# Main_DIY_board_-_STM32.net
KiCad netlist of a schematic drawn in EAGLE
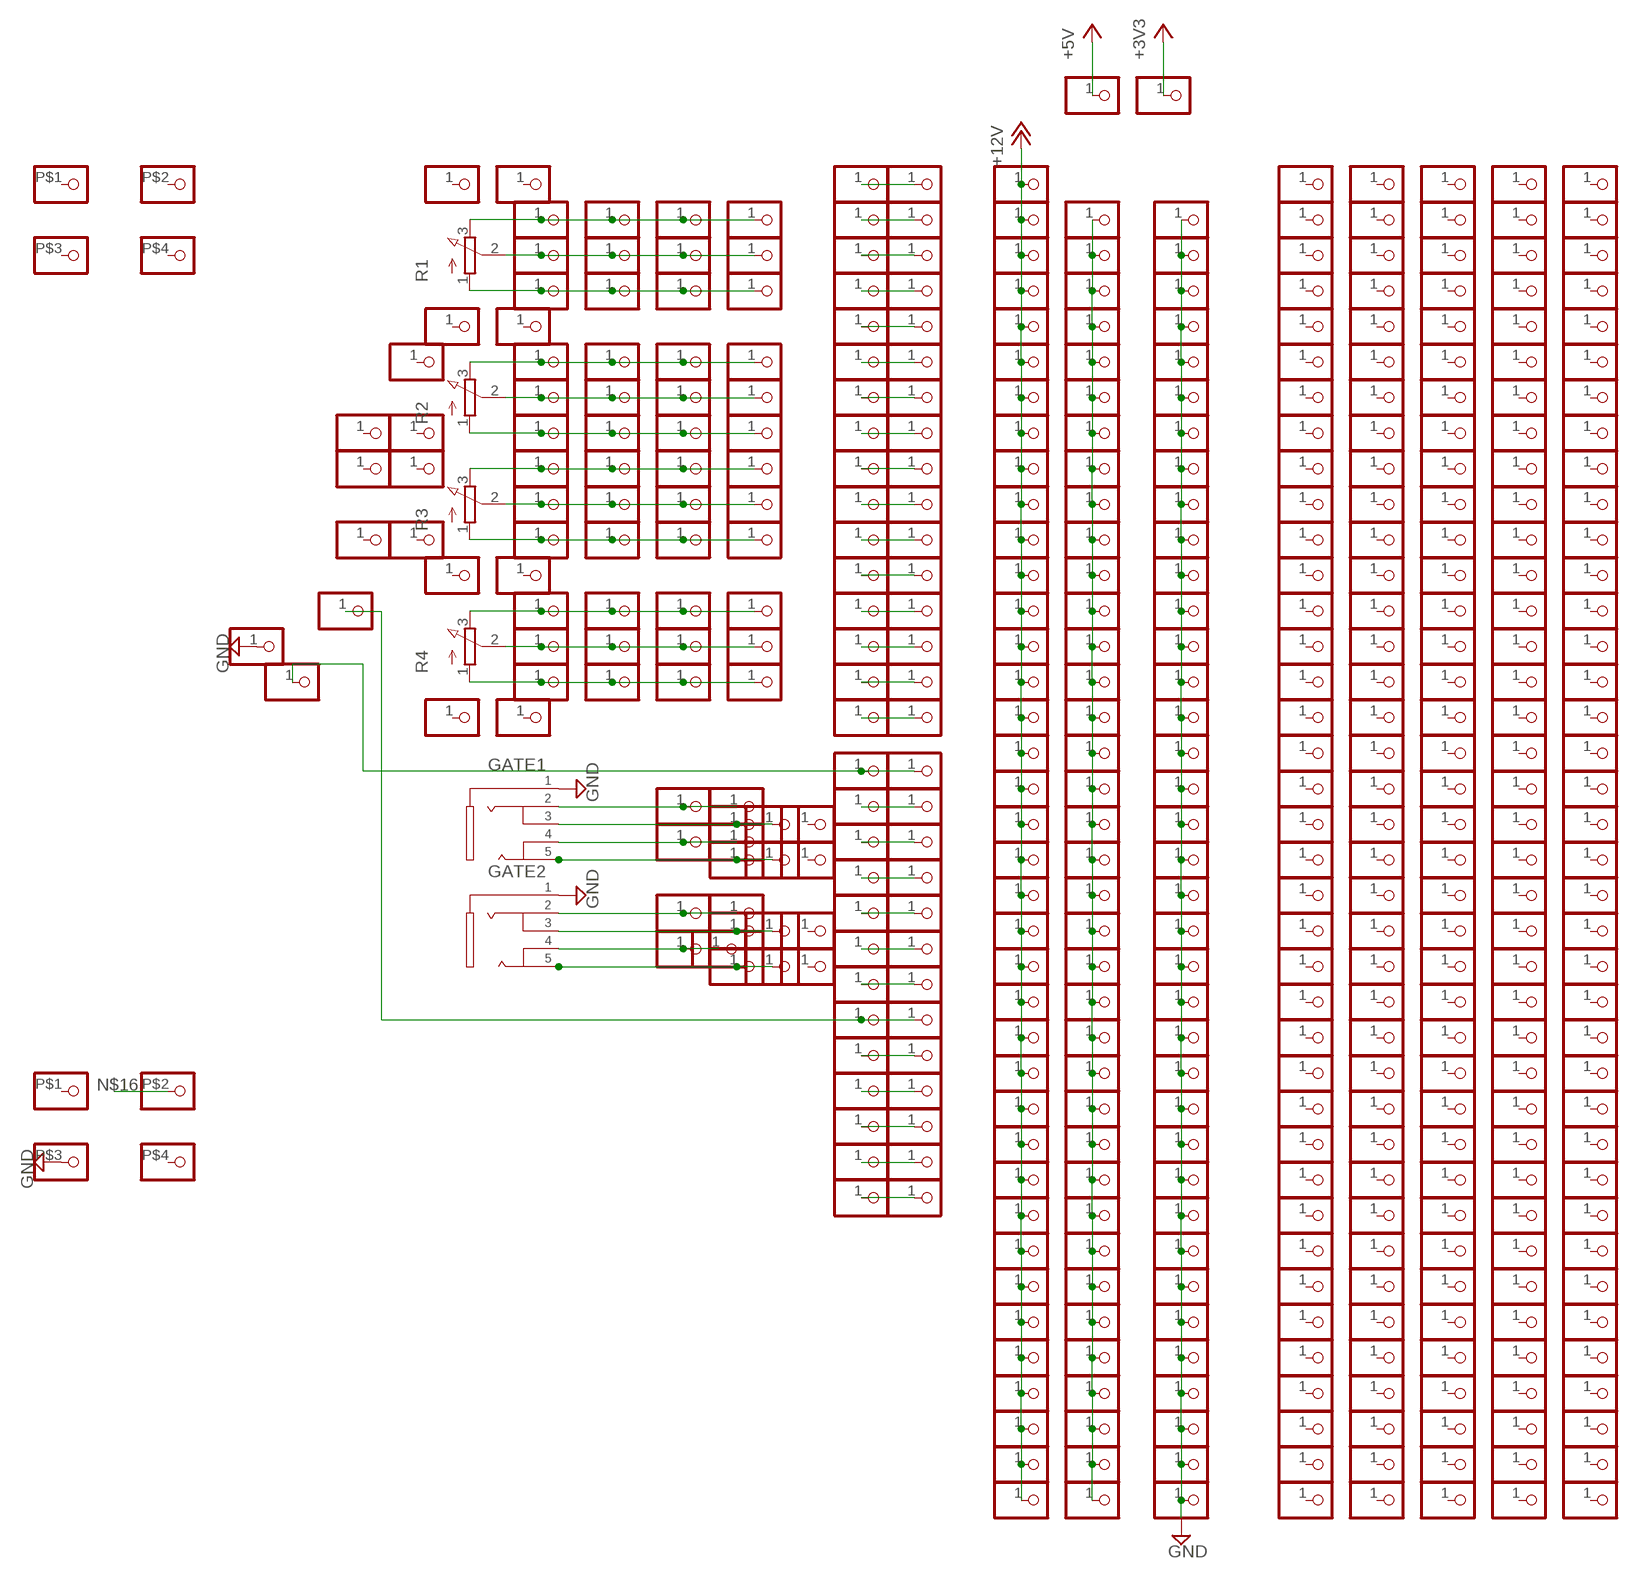
[diagram p0: schematic, sheet 1, part 1 of 2]
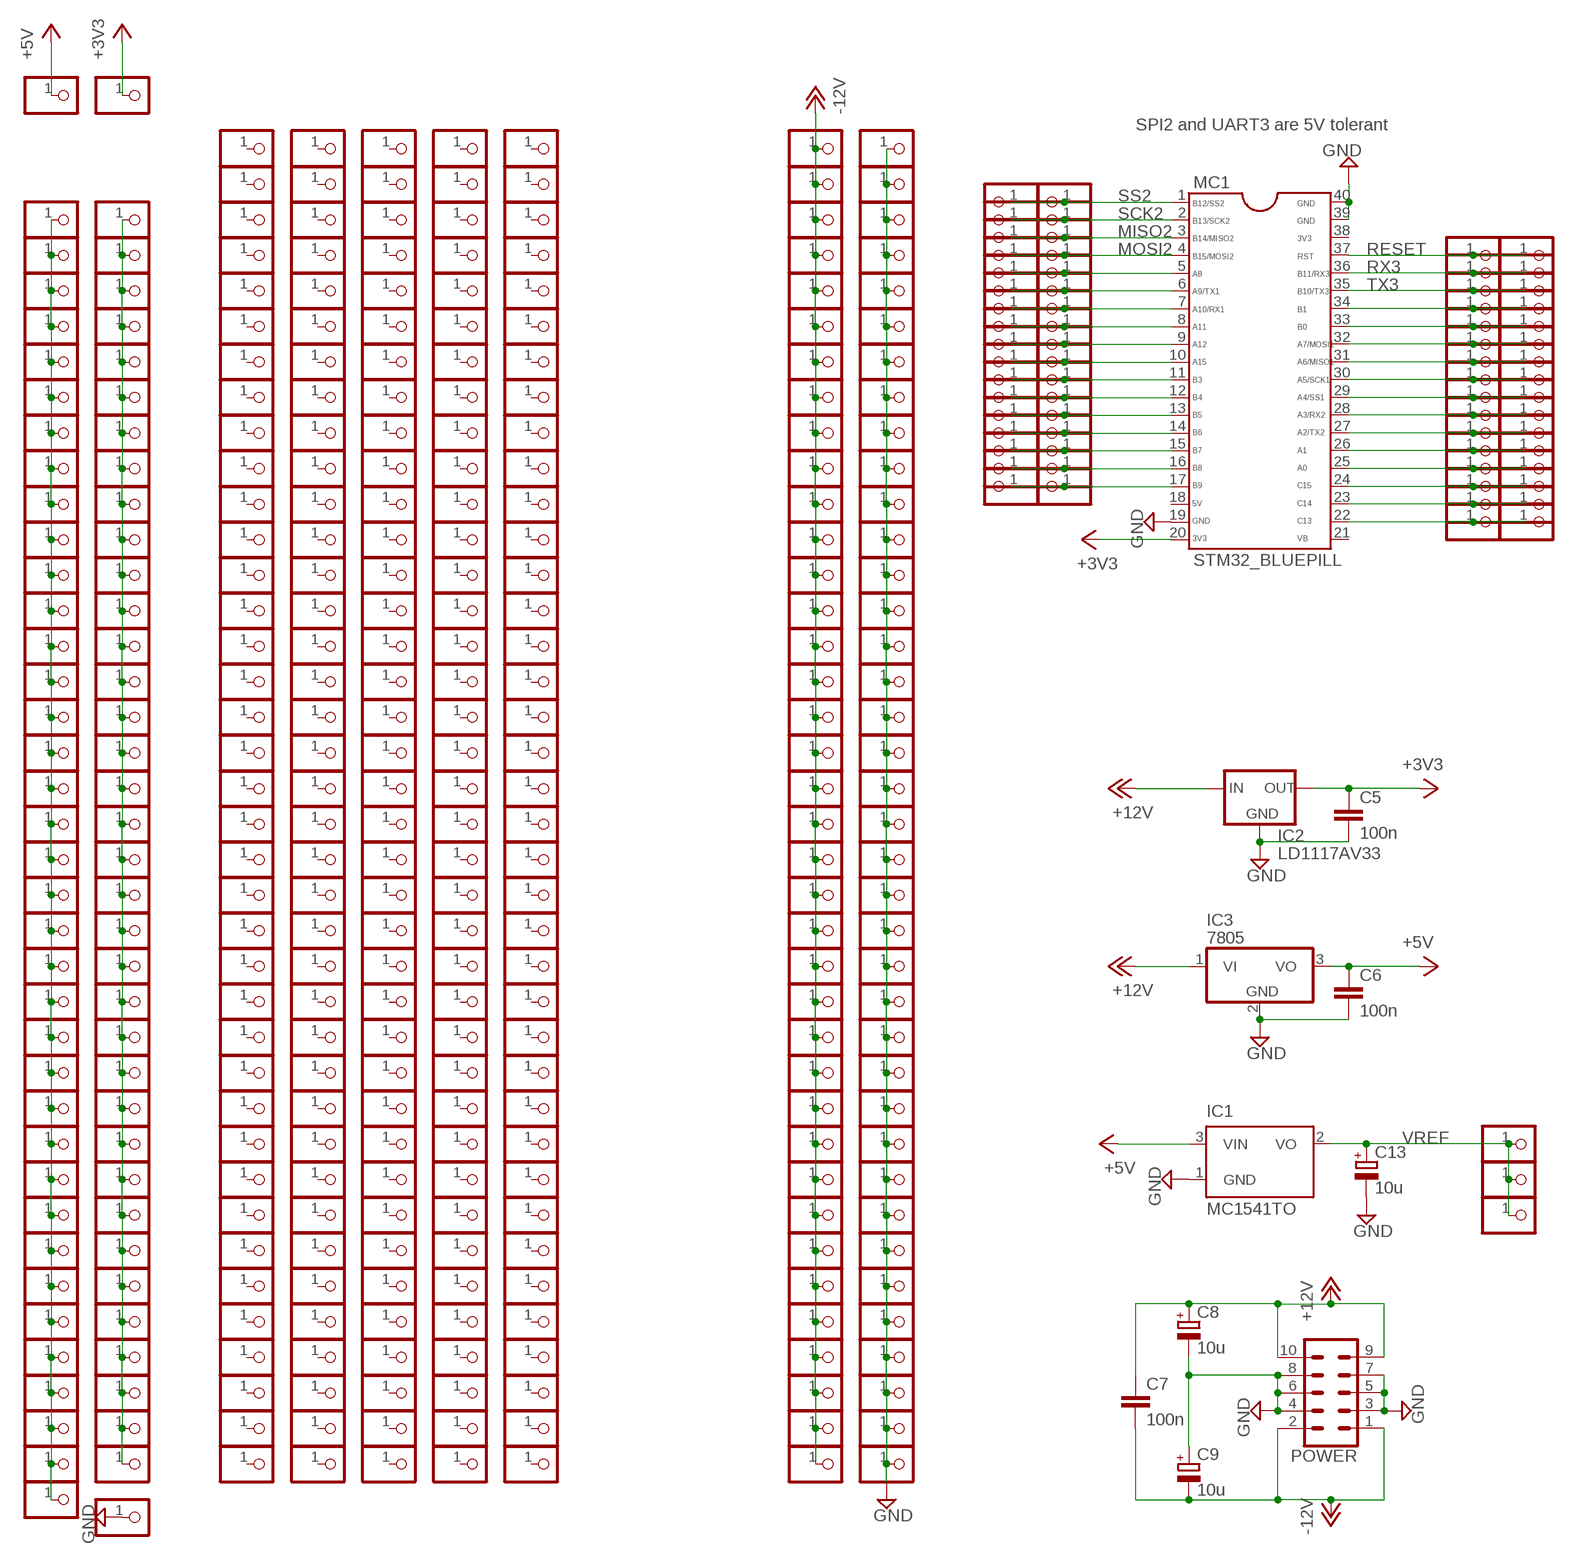
[diagram p1: schematic, sheet 1, part 2 of 2]

(export (version "E")
  (design (tool "Eeschema 10.0.6"))
  (components
    (comp (ref "C5")
      (value "100n")
      (footprint "eagle-import:C050-025X075")
      (libsource (lib "eagle-import") (part "C-EU050-025X075"))
    )
    (comp (ref "C6")
      (value "100n")
      (footprint "eagle-import:C050-025X075")
      (libsource (lib "eagle-import") (part "C-EU050-025X075"))
    )
    (comp (ref "C7")
      (value "100n")
      (footprint "eagle-import:C050-025X075")
      (libsource (lib "eagle-import") (part "C-EU050-025X075"))
    )
    (comp (ref "C8")
      (value "10u")
      (footprint "eagle-import:E2,5-5")
      (libsource (lib "eagle-import") (part "CPOL"))
    )
    (comp (ref "C9")
      (value "10u")
      (footprint "eagle-import:E2,5-5")
      (libsource (lib "eagle-import") (part "CPOL"))
    )
    (comp (ref "C13")
      (value "10u")
      (footprint "eagle-import:E2,5-5")
      (libsource (lib "eagle-import") (part "CPOL"))
    )
    (comp (ref "GATE1")
      (value "PJ-324MH")
      (footprint "eagle-import:PJ-324MH")
      (libsource (lib "eagle-import") (part "PJ-324MH"))
    )
    (comp (ref "GATE2")
      (value "PJ-324MH")
      (footprint "eagle-import:PJ-324MH")
      (libsource (lib "eagle-import") (part "PJ-324MH"))
    )
    (comp (ref "IC1")
      (value "MC1541TO")
      (footprint "eagle-import:TO92")
      (libsource (lib "eagle-import") (part "MC15TO41"))
    )
    (comp (ref "IC2")
      (value "LD1117AV33")
      (footprint "eagle-import:78XXL")
      (libsource (lib "eagle-import") (part "V_REG_LD1117VXX"))
    )
    (comp (ref "IC3")
      (value "7805")
      (footprint "eagle-import:TO220H")
      (libsource (lib "eagle-import") (part "78T05"))
    )
    (comp (ref "JP1")
      (value "1X01")
      (footprint "eagle-import:1X01")
      (libsource (lib "eagle-import") (part "1X01"))
    )
    (comp (ref "JP2")
      (value "1X01")
      (footprint "eagle-import:1X01")
      (libsource (lib "eagle-import") (part "1X01"))
    )
    (comp (ref "JP3")
      (value "1X01")
      (footprint "eagle-import:1X01")
      (libsource (lib "eagle-import") (part "1X01"))
    )
    (comp (ref "JP4")
      (value "1X01")
      (footprint "eagle-import:1X01")
      (libsource (lib "eagle-import") (part "1X01"))
    )
    (comp (ref "JP5")
      (value "1X01")
      (footprint "eagle-import:1X01")
      (libsource (lib "eagle-import") (part "1X01"))
    )
    (comp (ref "JP6")
      (value "1X01")
      (footprint "eagle-import:1X01")
      (libsource (lib "eagle-import") (part "1X01"))
    )
    (comp (ref "JP7")
      (value "1X01")
      (footprint "eagle-import:1X01")
      (libsource (lib "eagle-import") (part "1X01"))
    )
    (comp (ref "JP8")
      (value "1X01")
      (footprint "eagle-import:1X01")
      (libsource (lib "eagle-import") (part "1X01"))
    )
    (comp (ref "JP9")
      (value "1X01")
      (footprint "eagle-import:1X01")
      (libsource (lib "eagle-import") (part "1X01"))
    )
    (comp (ref "JP10")
      (value "1X01")
      (footprint "eagle-import:1X01")
      (libsource (lib "eagle-import") (part "1X01"))
    )
    (comp (ref "JP11")
      (value "1X01")
      (footprint "eagle-import:1X01")
      (libsource (lib "eagle-import") (part "1X01"))
    )
    (comp (ref "JP12")
      (value "1X01")
      (footprint "eagle-import:1X01")
      (libsource (lib "eagle-import") (part "1X01"))
    )
    (comp (ref "JP13")
      (value "1X01")
      (footprint "eagle-import:1X01")
      (libsource (lib "eagle-import") (part "1X01"))
    )
    (comp (ref "JP14")
      (value "1X01")
      (footprint "eagle-import:1X01")
      (libsource (lib "eagle-import") (part "1X01"))
    )
    (comp (ref "JP15")
      (value "1X01")
      (footprint "eagle-import:1X01")
      (libsource (lib "eagle-import") (part "1X01"))
    )
    (comp (ref "JP16")
      (value "1X01")
      (footprint "eagle-import:1X01")
      (libsource (lib "eagle-import") (part "1X01"))
    )
    (comp (ref "JP17")
      (value "1X01")
      (footprint "eagle-import:1X01")
      (libsource (lib "eagle-import") (part "1X01"))
    )
    (comp (ref "JP18")
      (value "1X01")
      (footprint "eagle-import:1X01")
      (libsource (lib "eagle-import") (part "1X01"))
    )
    (comp (ref "JP19")
      (value "1X01")
      (footprint "eagle-import:1X01")
      (libsource (lib "eagle-import") (part "1X01"))
    )
    (comp (ref "JP20")
      (value "1X01")
      (footprint "eagle-import:1X01")
      (libsource (lib "eagle-import") (part "1X01"))
    )
    (comp (ref "JP21")
      (value "1X01")
      (footprint "eagle-import:1X01")
      (libsource (lib "eagle-import") (part "1X01"))
    )
    (comp (ref "JP22")
      (value "1X01")
      (footprint "eagle-import:1X01")
      (libsource (lib "eagle-import") (part "1X01"))
    )
    (comp (ref "JP23")
      (value "1X01")
      (footprint "eagle-import:1X01")
      (libsource (lib "eagle-import") (part "1X01"))
    )
    (comp (ref "JP24")
      (value "1X01")
      (footprint "eagle-import:1X01")
      (libsource (lib "eagle-import") (part "1X01"))
    )
    (comp (ref "JP25")
      (value "1X01")
      (footprint "eagle-import:1X01")
      (libsource (lib "eagle-import") (part "1X01"))
    )
    (comp (ref "JP26")
      (value "1X01")
      (footprint "eagle-import:1X01")
      (libsource (lib "eagle-import") (part "1X01"))
    )
    (comp (ref "JP27")
      (value "1X01")
      (footprint "eagle-import:1X01")
      (libsource (lib "eagle-import") (part "1X01"))
    )
    (comp (ref "JP28")
      (value "1X01")
      (footprint "eagle-import:1X01")
      (libsource (lib "eagle-import") (part "1X01"))
    )
    (comp (ref "JP29")
      (value "1X01")
      (footprint "eagle-import:1X01")
      (libsource (lib "eagle-import") (part "1X01"))
    )
    (comp (ref "JP30")
      (value "1X01")
      (footprint "eagle-import:1X01")
      (libsource (lib "eagle-import") (part "1X01"))
    )
    (comp (ref "JP31")
      (value "1X01")
      (footprint "eagle-import:1X01")
      (libsource (lib "eagle-import") (part "1X01"))
    )
    (comp (ref "JP32")
      (value "1X01")
      (footprint "eagle-import:1X01")
      (libsource (lib "eagle-import") (part "1X01"))
    )
    (comp (ref "JP33")
      (value "1X01")
      (footprint "eagle-import:1X01")
      (libsource (lib "eagle-import") (part "1X01"))
    )
    (comp (ref "JP34")
      (value "1X01")
      (footprint "eagle-import:1X01")
      (libsource (lib "eagle-import") (part "1X01"))
    )
    (comp (ref "JP35")
      (value "1X01")
      (footprint "eagle-import:1X01")
      (libsource (lib "eagle-import") (part "1X01"))
    )
    (comp (ref "JP36")
      (value "1X01")
      (footprint "eagle-import:1X01")
      (libsource (lib "eagle-import") (part "1X01"))
    )
    (comp (ref "JP37")
      (value "1X01")
      (footprint "eagle-import:1X01")
      (libsource (lib "eagle-import") (part "1X01"))
    )
    (comp (ref "JP38")
      (value "1X01")
      (footprint "eagle-import:1X01")
      (libsource (lib "eagle-import") (part "1X01"))
    )
    (comp (ref "JP39")
      (value "1X01")
      (footprint "eagle-import:1X01")
      (libsource (lib "eagle-import") (part "1X01"))
    )
    (comp (ref "JP40")
      (value "1X01")
      (footprint "eagle-import:1X01")
      (libsource (lib "eagle-import") (part "1X01"))
    )
    (comp (ref "JP41")
      (value "1X01")
      (footprint "eagle-import:1X01")
      (libsource (lib "eagle-import") (part "1X01"))
    )
    (comp (ref "JP42")
      (value "1X01")
      (footprint "eagle-import:1X01")
      (libsource (lib "eagle-import") (part "1X01"))
    )
    (comp (ref "JP43")
      (value "1X01")
      (footprint "eagle-import:1X01")
      (libsource (lib "eagle-import") (part "1X01"))
    )
    (comp (ref "JP44")
      (value "1X01")
      (footprint "eagle-import:1X01")
      (libsource (lib "eagle-import") (part "1X01"))
    )
    (comp (ref "JP45")
      (value "1X01")
      (footprint "eagle-import:1X01")
      (libsource (lib "eagle-import") (part "1X01"))
    )
    (comp (ref "JP46")
      (value "1X01")
      (footprint "eagle-import:1X01")
      (libsource (lib "eagle-import") (part "1X01"))
    )
    (comp (ref "JP47")
      (value "1X01")
      (footprint "eagle-import:1X01")
      (libsource (lib "eagle-import") (part "1X01"))
    )
    (comp (ref "JP48")
      (value "1X01")
      (footprint "eagle-import:1X01")
      (libsource (lib "eagle-import") (part "1X01"))
    )
    (comp (ref "JP49")
      (value "1X01")
      (footprint "eagle-import:1X01")
      (libsource (lib "eagle-import") (part "1X01"))
    )
    (comp (ref "JP50")
      (value "1X01")
      (footprint "eagle-import:1X01")
      (libsource (lib "eagle-import") (part "1X01"))
    )
    (comp (ref "JP51")
      (value "1X01")
      (footprint "eagle-import:1X01")
      (libsource (lib "eagle-import") (part "1X01"))
    )
    (comp (ref "JP52")
      (value "1X01")
      (footprint "eagle-import:1X01")
      (libsource (lib "eagle-import") (part "1X01"))
    )
    (comp (ref "JP53")
      (value "1X01")
      (footprint "eagle-import:1X01")
      (libsource (lib "eagle-import") (part "1X01"))
    )
    (comp (ref "JP54")
      (value "1X01")
      (footprint "eagle-import:1X01")
      (libsource (lib "eagle-import") (part "1X01"))
    )
    (comp (ref "JP55")
      (value "1X01")
      (footprint "eagle-import:1X01")
      (libsource (lib "eagle-import") (part "1X01"))
    )
    (comp (ref "JP56")
      (value "1X01")
      (footprint "eagle-import:1X01")
      (libsource (lib "eagle-import") (part "1X01"))
    )
    (comp (ref "JP57")
      (value "1X01")
      (footprint "eagle-import:1X01")
      (libsource (lib "eagle-import") (part "1X01"))
    )
    (comp (ref "JP58")
      (value "1X01")
      (footprint "eagle-import:1X01")
      (libsource (lib "eagle-import") (part "1X01"))
    )
    (comp (ref "JP59")
      (value "1X01")
      (footprint "eagle-import:1X01")
      (libsource (lib "eagle-import") (part "1X01"))
    )
    (comp (ref "JP60")
      (value "1X01")
      (footprint "eagle-import:1X01")
      (libsource (lib "eagle-import") (part "1X01"))
    )
    (comp (ref "JP61")
      (value "1X01")
      (footprint "eagle-import:1X01")
      (libsource (lib "eagle-import") (part "1X01"))
    )
    (comp (ref "JP62")
      (value "1X01")
      (footprint "eagle-import:1X01")
      (libsource (lib "eagle-import") (part "1X01"))
    )
    (comp (ref "JP63")
      (value "1X01")
      (footprint "eagle-import:1X01")
      (libsource (lib "eagle-import") (part "1X01"))
    )
    (comp (ref "JP64")
      (value "1X01")
      (footprint "eagle-import:1X01")
      (libsource (lib "eagle-import") (part "1X01"))
    )
    (comp (ref "JP65")
      (value "1X01")
      (footprint "eagle-import:1X01")
      (libsource (lib "eagle-import") (part "1X01"))
    )
    (comp (ref "JP66")
      (value "1X01")
      (footprint "eagle-import:1X01")
      (libsource (lib "eagle-import") (part "1X01"))
    )
    (comp (ref "JP67")
      (value "1X01")
      (footprint "eagle-import:1X01")
      (libsource (lib "eagle-import") (part "1X01"))
    )
    (comp (ref "JP68")
      (value "1X01")
      (footprint "eagle-import:1X01")
      (libsource (lib "eagle-import") (part "1X01"))
    )
    (comp (ref "JP69")
      (value "1X01")
      (footprint "eagle-import:1X01")
      (libsource (lib "eagle-import") (part "1X01"))
    )
    (comp (ref "JP70")
      (value "1X01")
      (footprint "eagle-import:1X01")
      (libsource (lib "eagle-import") (part "1X01"))
    )
    (comp (ref "JP71")
      (value "1X01")
      (footprint "eagle-import:1X01")
      (libsource (lib "eagle-import") (part "1X01"))
    )
    (comp (ref "JP72")
      (value "1X01")
      (footprint "eagle-import:1X01")
      (libsource (lib "eagle-import") (part "1X01"))
    )
    (comp (ref "JP73")
      (value "1X01")
      (footprint "eagle-import:1X01")
      (libsource (lib "eagle-import") (part "1X01"))
    )
    (comp (ref "JP74")
      (value "1X01")
      (footprint "eagle-import:1X01")
      (libsource (lib "eagle-import") (part "1X01"))
    )
    (comp (ref "JP75")
      (value "1X01")
      (footprint "eagle-import:1X01")
      (libsource (lib "eagle-import") (part "1X01"))
    )
    (comp (ref "JP76")
      (value "1X01")
      (footprint "eagle-import:1X01")
      (libsource (lib "eagle-import") (part "1X01"))
    )
    (comp (ref "JP77")
      (value "1X01")
      (footprint "eagle-import:1X01")
      (libsource (lib "eagle-import") (part "1X01"))
    )
    (comp (ref "JP78")
      (value "1X01")
      (footprint "eagle-import:1X01")
      (libsource (lib "eagle-import") (part "1X01"))
    )
    (comp (ref "JP79")
      (value "1X01")
      (footprint "eagle-import:1X01")
      (libsource (lib "eagle-import") (part "1X01"))
    )
    (comp (ref "JP80")
      (value "1X01")
      (footprint "eagle-import:1X01")
      (libsource (lib "eagle-import") (part "1X01"))
    )
    (comp (ref "JP81")
      (value "1X01")
      (footprint "eagle-import:1X01")
      (libsource (lib "eagle-import") (part "1X01"))
    )
    (comp (ref "JP82")
      (value "1X01")
      (footprint "eagle-import:1X01")
      (libsource (lib "eagle-import") (part "1X01"))
    )
    (comp (ref "JP83")
      (value "1X01")
      (footprint "eagle-import:1X01")
      (libsource (lib "eagle-import") (part "1X01"))
    )
    (comp (ref "JP84")
      (value "1X01")
      (footprint "eagle-import:1X01")
      (libsource (lib "eagle-import") (part "1X01"))
    )
    (comp (ref "JP85")
      (value "1X01")
      (footprint "eagle-import:1X01")
      (libsource (lib "eagle-import") (part "1X01"))
    )
    (comp (ref "JP86")
      (value "1X01")
      (footprint "eagle-import:1X01")
      (libsource (lib "eagle-import") (part "1X01"))
    )
    (comp (ref "JP87")
      (value "1X01")
      (footprint "eagle-import:1X01")
      (libsource (lib "eagle-import") (part "1X01"))
    )
    (comp (ref "JP88")
      (value "1X01")
      (footprint "eagle-import:1X01")
      (libsource (lib "eagle-import") (part "1X01"))
    )
    (comp (ref "JP89")
      (value "1X01")
      (footprint "eagle-import:1X01")
      (libsource (lib "eagle-import") (part "1X01"))
    )
    (comp (ref "JP90")
      (value "1X01")
      (footprint "eagle-import:1X01")
      (libsource (lib "eagle-import") (part "1X01"))
    )
    (comp (ref "JP91")
      (value "1X01")
      (footprint "eagle-import:1X01")
      (libsource (lib "eagle-import") (part "1X01"))
    )
    (comp (ref "JP92")
      (value "1X01")
      (footprint "eagle-import:1X01")
      (libsource (lib "eagle-import") (part "1X01"))
    )
    (comp (ref "JP93")
      (value "1X01")
      (footprint "eagle-import:1X01")
      (libsource (lib "eagle-import") (part "1X01"))
    )
    (comp (ref "JP94")
      (value "1X01")
      (footprint "eagle-import:1X01")
      (libsource (lib "eagle-import") (part "1X01"))
    )
    (comp (ref "JP95")
      (value "1X01")
      (footprint "eagle-import:1X01")
      (libsource (lib "eagle-import") (part "1X01"))
    )
    (comp (ref "JP96")
      (value "1X01")
      (footprint "eagle-import:1X01")
      (libsource (lib "eagle-import") (part "1X01"))
    )
    (comp (ref "JP97")
      (value "1X01")
      (footprint "eagle-import:1X01")
      (libsource (lib "eagle-import") (part "1X01"))
    )
    (comp (ref "JP98")
      (value "1X01")
      (footprint "eagle-import:1X01")
      (libsource (lib "eagle-import") (part "1X01"))
    )
    (comp (ref "JP99")
      (value "1X01")
      (footprint "eagle-import:1X01")
      (libsource (lib "eagle-import") (part "1X01"))
    )
    (comp (ref "JP100")
      (value "1X01")
      (footprint "eagle-import:1X01")
      (libsource (lib "eagle-import") (part "1X01"))
    )
    (comp (ref "JP101")
      (value "1X01")
      (footprint "eagle-import:1X01")
      (libsource (lib "eagle-import") (part "1X01"))
    )
    (comp (ref "JP102")
      (value "1X01")
      (footprint "eagle-import:1X01")
      (libsource (lib "eagle-import") (part "1X01"))
    )
    (comp (ref "JP103")
      (value "1X01")
      (footprint "eagle-import:1X01")
      (libsource (lib "eagle-import") (part "1X01"))
    )
    (comp (ref "JP104")
      (value "1X01")
      (footprint "eagle-import:1X01")
      (libsource (lib "eagle-import") (part "1X01"))
    )
    (comp (ref "JP105")
      (value "1X01")
      (footprint "eagle-import:1X01")
      (libsource (lib "eagle-import") (part "1X01"))
    )
    (comp (ref "JP106")
      (value "1X01")
      (footprint "eagle-import:1X01")
      (libsource (lib "eagle-import") (part "1X01"))
    )
    (comp (ref "JP107")
      (value "1X01")
      (footprint "eagle-import:1X01")
      (libsource (lib "eagle-import") (part "1X01"))
    )
    (comp (ref "JP108")
      (value "1X01")
      (footprint "eagle-import:1X01")
      (libsource (lib "eagle-import") (part "1X01"))
    )
    (comp (ref "JP109")
      (value "1X01")
      (footprint "eagle-import:1X01")
      (libsource (lib "eagle-import") (part "1X01"))
    )
    (comp (ref "JP110")
      (value "1X01")
      (footprint "eagle-import:1X01")
      (libsource (lib "eagle-import") (part "1X01"))
    )
    (comp (ref "JP111")
      (value "1X01")
      (footprint "eagle-import:1X01")
      (libsource (lib "eagle-import") (part "1X01"))
    )
    (comp (ref "JP112")
      (value "1X01")
      (footprint "eagle-import:1X01")
      (libsource (lib "eagle-import") (part "1X01"))
    )
    (comp (ref "JP113")
      (value "1X01")
      (footprint "eagle-import:1X01")
      (libsource (lib "eagle-import") (part "1X01"))
    )
    (comp (ref "JP114")
      (value "1X01")
      (footprint "eagle-import:1X01")
      (libsource (lib "eagle-import") (part "1X01"))
    )
    (comp (ref "JP115")
      (value "1X01")
      (footprint "eagle-import:1X01")
      (libsource (lib "eagle-import") (part "1X01"))
    )
    (comp (ref "JP116")
      (value "1X01")
      (footprint "eagle-import:1X01")
      (libsource (lib "eagle-import") (part "1X01"))
    )
    (comp (ref "JP117")
      (value "1X01")
      (footprint "eagle-import:1X01")
      (libsource (lib "eagle-import") (part "1X01"))
    )
    (comp (ref "JP118")
      (value "1X01")
      (footprint "eagle-import:1X01")
      (libsource (lib "eagle-import") (part "1X01"))
    )
    (comp (ref "JP119")
      (value "1X01")
      (footprint "eagle-import:1X01")
      (libsource (lib "eagle-import") (part "1X01"))
    )
    (comp (ref "JP120")
      (value "1X01")
      (footprint "eagle-import:1X01")
      (libsource (lib "eagle-import") (part "1X01"))
    )
    (comp (ref "JP121")
      (value "1X01")
      (footprint "eagle-import:1X01")
      (libsource (lib "eagle-import") (part "1X01"))
    )
    (comp (ref "JP122")
      (value "1X01")
      (footprint "eagle-import:1X01")
      (libsource (lib "eagle-import") (part "1X01"))
    )
    (comp (ref "JP123")
      (value "1X01")
      (footprint "eagle-import:1X01")
      (libsource (lib "eagle-import") (part "1X01"))
    )
    (comp (ref "JP124")
      (value "1X01")
      (footprint "eagle-import:1X01")
      (libsource (lib "eagle-import") (part "1X01"))
    )
    (comp (ref "JP125")
      (value "1X01")
      (footprint "eagle-import:1X01")
      (libsource (lib "eagle-import") (part "1X01"))
    )
    (comp (ref "JP126")
      (value "1X01")
      (footprint "eagle-import:1X01")
      (libsource (lib "eagle-import") (part "1X01"))
    )
    (comp (ref "JP127")
      (value "1X01")
      (footprint "eagle-import:1X01")
      (libsource (lib "eagle-import") (part "1X01"))
    )
    (comp (ref "JP128")
      (value "1X01")
      (footprint "eagle-import:1X01")
      (libsource (lib "eagle-import") (part "1X01"))
    )
    (comp (ref "JP129")
      (value "1X01")
      (footprint "eagle-import:1X01")
      (libsource (lib "eagle-import") (part "1X01"))
    )
    (comp (ref "JP130")
      (value "1X01")
      (footprint "eagle-import:1X01")
      (libsource (lib "eagle-import") (part "1X01"))
    )
    (comp (ref "JP131")
      (value "1X01")
      (footprint "eagle-import:1X01")
      (libsource (lib "eagle-import") (part "1X01"))
    )
    (comp (ref "JP132")
      (value "1X01")
      (footprint "eagle-import:1X01")
      (libsource (lib "eagle-import") (part "1X01"))
    )
    (comp (ref "JP133")
      (value "1X01")
      (footprint "eagle-import:1X01")
      (libsource (lib "eagle-import") (part "1X01"))
    )
    (comp (ref "JP134")
      (value "1X01")
      (footprint "eagle-import:1X01")
      (libsource (lib "eagle-import") (part "1X01"))
    )
    (comp (ref "JP135")
      (value "1X01")
      (footprint "eagle-import:1X01")
      (libsource (lib "eagle-import") (part "1X01"))
    )
    (comp (ref "JP136")
      (value "1X01")
      (footprint "eagle-import:1X01")
      (libsource (lib "eagle-import") (part "1X01"))
    )
    (comp (ref "JP137")
      (value "1X01")
      (footprint "eagle-import:1X01")
      (libsource (lib "eagle-import") (part "1X01"))
    )
    (comp (ref "JP138")
      (value "1X01")
      (footprint "eagle-import:1X01")
      (libsource (lib "eagle-import") (part "1X01"))
    )
    (comp (ref "JP139")
      (value "1X01")
      (footprint "eagle-import:1X01")
      (libsource (lib "eagle-import") (part "1X01"))
    )
    (comp (ref "JP140")
      (value "1X01")
      (footprint "eagle-import:1X01")
      (libsource (lib "eagle-import") (part "1X01"))
    )
    (comp (ref "JP141")
      (value "1X01")
      (footprint "eagle-import:1X01")
      (libsource (lib "eagle-import") (part "1X01"))
    )
    (comp (ref "JP142")
      (value "1X01")
      (footprint "eagle-import:1X01")
      (libsource (lib "eagle-import") (part "1X01"))
    )
    (comp (ref "JP143")
      (value "1X01")
      (footprint "eagle-import:1X01")
      (libsource (lib "eagle-import") (part "1X01"))
    )
    (comp (ref "JP144")
      (value "1X01")
      (footprint "eagle-import:1X01")
      (libsource (lib "eagle-import") (part "1X01"))
    )
    (comp (ref "JP145")
      (value "1X01")
      (footprint "eagle-import:1X01")
      (libsource (lib "eagle-import") (part "1X01"))
    )
    (comp (ref "JP146")
      (value "1X01")
      (footprint "eagle-import:1X01")
      (libsource (lib "eagle-import") (part "1X01"))
    )
    (comp (ref "JP147")
      (value "1X01")
      (footprint "eagle-import:1X01")
      (libsource (lib "eagle-import") (part "1X01"))
    )
    (comp (ref "JP148")
      (value "1X01")
      (footprint "eagle-import:1X01")
      (libsource (lib "eagle-import") (part "1X01"))
    )
    (comp (ref "JP149")
      (value "1X01")
      (footprint "eagle-import:1X01")
      (libsource (lib "eagle-import") (part "1X01"))
    )
    (comp (ref "JP150")
      (value "1X01")
      (footprint "eagle-import:1X01")
      (libsource (lib "eagle-import") (part "1X01"))
    )
    (comp (ref "JP151")
      (value "1X01")
      (footprint "eagle-import:1X01")
      (libsource (lib "eagle-import") (part "1X01"))
    )
    (comp (ref "JP152")
      (value "1X01")
      (footprint "eagle-import:1X01")
      (libsource (lib "eagle-import") (part "1X01"))
    )
    (comp (ref "JP153")
      (value "1X01")
      (footprint "eagle-import:1X01")
      (libsource (lib "eagle-import") (part "1X01"))
    )
    (comp (ref "JP154")
      (value "1X01")
      (footprint "eagle-import:1X01")
      (libsource (lib "eagle-import") (part "1X01"))
    )
    (comp (ref "JP155")
      (value "1X01")
      (footprint "eagle-import:1X01")
      (libsource (lib "eagle-import") (part "1X01"))
    )
    (comp (ref "JP156")
      (value "1X01")
      (footprint "eagle-import:1X01")
      (libsource (lib "eagle-import") (part "1X01"))
    )
    (comp (ref "JP157")
      (value "1X01")
      (footprint "eagle-import:1X01")
      (libsource (lib "eagle-import") (part "1X01"))
    )
    (comp (ref "JP158")
      (value "1X01")
      (footprint "eagle-import:1X01")
      (libsource (lib "eagle-import") (part "1X01"))
    )
    (comp (ref "JP159")
      (value "1X01")
      (footprint "eagle-import:1X01")
      (libsource (lib "eagle-import") (part "1X01"))
    )
    (comp (ref "JP160")
      (value "1X01")
      (footprint "eagle-import:1X01")
      (libsource (lib "eagle-import") (part "1X01"))
    )
    (comp (ref "JP161")
      (value "1X01")
      (footprint "eagle-import:1X01")
      (libsource (lib "eagle-import") (part "1X01"))
    )
    (comp (ref "JP162")
      (value "1X01")
      (footprint "eagle-import:1X01")
      (libsource (lib "eagle-import") (part "1X01"))
    )
    (comp (ref "JP163")
      (value "1X01")
      (footprint "eagle-import:1X01")
      (libsource (lib "eagle-import") (part "1X01"))
    )
    (comp (ref "JP164")
      (value "1X01")
      (footprint "eagle-import:1X01")
      (libsource (lib "eagle-import") (part "1X01"))
    )
    (comp (ref "JP165")
      (value "1X01")
      (footprint "eagle-import:1X01")
      (libsource (lib "eagle-import") (part "1X01"))
    )
    (comp (ref "JP166")
      (value "1X01")
      (footprint "eagle-import:1X01")
      (libsource (lib "eagle-import") (part "1X01"))
    )
    (comp (ref "JP167")
      (value "1X01")
      (footprint "eagle-import:1X01")
      (libsource (lib "eagle-import") (part "1X01"))
    )
    (comp (ref "JP168")
      (value "1X01")
      (footprint "eagle-import:1X01")
      (libsource (lib "eagle-import") (part "1X01"))
    )
    (comp (ref "JP169")
      (value "1X01")
      (footprint "eagle-import:1X01")
      (libsource (lib "eagle-import") (part "1X01"))
    )
    (comp (ref "JP170")
      (value "1X01")
      (footprint "eagle-import:1X01")
      (libsource (lib "eagle-import") (part "1X01"))
    )
    (comp (ref "JP171")
      (value "1X01")
      (footprint "eagle-import:1X01")
      (libsource (lib "eagle-import") (part "1X01"))
    )
    (comp (ref "JP172")
      (value "1X01")
      (footprint "eagle-import:1X01")
      (libsource (lib "eagle-import") (part "1X01"))
    )
    (comp (ref "JP173")
      (value "1X01")
      (footprint "eagle-import:1X01")
      (libsource (lib "eagle-import") (part "1X01"))
    )
    (comp (ref "JP174")
      (value "1X01")
      (footprint "eagle-import:1X01")
      (libsource (lib "eagle-import") (part "1X01"))
    )
    (comp (ref "JP175")
      (value "1X01")
      (footprint "eagle-import:1X01")
      (libsource (lib "eagle-import") (part "1X01"))
    )
    (comp (ref "JP176")
      (value "1X01")
      (footprint "eagle-import:1X01")
      (libsource (lib "eagle-import") (part "1X01"))
    )
    (comp (ref "JP177")
      (value "1X01")
      (footprint "eagle-import:1X01")
      (libsource (lib "eagle-import") (part "1X01"))
    )
    (comp (ref "JP178")
      (value "1X01")
      (footprint "eagle-import:1X01")
      (libsource (lib "eagle-import") (part "1X01"))
    )
    (comp (ref "JP179")
      (value "1X01")
      (footprint "eagle-import:1X01")
      (libsource (lib "eagle-import") (part "1X01"))
    )
    (comp (ref "JP180")
      (value "1X01")
      (footprint "eagle-import:1X01")
      (libsource (lib "eagle-import") (part "1X01"))
    )
    (comp (ref "JP181")
      (value "1X01")
      (footprint "eagle-import:1X01")
      (libsource (lib "eagle-import") (part "1X01"))
    )
    (comp (ref "JP182")
      (value "1X01")
      (footprint "eagle-import:1X01")
      (libsource (lib "eagle-import") (part "1X01"))
    )
    (comp (ref "JP183")
      (value "1X01")
      (footprint "eagle-import:1X01")
      (libsource (lib "eagle-import") (part "1X01"))
    )
    (comp (ref "JP184")
      (value "1X01")
      (footprint "eagle-import:1X01")
      (libsource (lib "eagle-import") (part "1X01"))
    )
    (comp (ref "JP185")
      (value "1X01")
      (footprint "eagle-import:1X01")
      (libsource (lib "eagle-import") (part "1X01"))
    )
    (comp (ref "JP186")
      (value "1X01")
      (footprint "eagle-import:1X01")
      (libsource (lib "eagle-import") (part "1X01"))
    )
    (comp (ref "JP187")
      (value "1X01")
      (footprint "eagle-import:1X01")
      (libsource (lib "eagle-import") (part "1X01"))
    )
    (comp (ref "JP188")
      (value "1X01")
      (footprint "eagle-import:1X01")
      (libsource (lib "eagle-import") (part "1X01"))
    )
    (comp (ref "JP189")
      (value "1X01")
      (footprint "eagle-import:1X01")
      (libsource (lib "eagle-import") (part "1X01"))
    )
    (comp (ref "JP190")
      (value "1X01")
      (footprint "eagle-import:1X01")
      (libsource (lib "eagle-import") (part "1X01"))
    )
    (comp (ref "JP191")
      (value "1X01")
      (footprint "eagle-import:1X01")
      (libsource (lib "eagle-import") (part "1X01"))
    )
    (comp (ref "JP192")
      (value "1X01")
      (footprint "eagle-import:1X01")
      (libsource (lib "eagle-import") (part "1X01"))
    )
    (comp (ref "JP193")
      (value "1X01")
      (footprint "eagle-import:1X01")
      (libsource (lib "eagle-import") (part "1X01"))
    )
    (comp (ref "JP194")
      (value "1X01")
      (footprint "eagle-import:1X01")
      (libsource (lib "eagle-import") (part "1X01"))
    )
    (comp (ref "JP195")
      (value "1X01")
      (footprint "eagle-import:1X01")
      (libsource (lib "eagle-import") (part "1X01"))
    )
    (comp (ref "JP196")
      (value "1X01")
      (footprint "eagle-import:1X01")
      (libsource (lib "eagle-import") (part "1X01"))
    )
    (comp (ref "JP197")
      (value "1X01")
      (footprint "eagle-import:1X01")
      (libsource (lib "eagle-import") (part "1X01"))
    )
    (comp (ref "JP198")
      (value "1X01")
      (footprint "eagle-import:1X01")
      (libsource (lib "eagle-import") (part "1X01"))
    )
    (comp (ref "JP199")
      (value "1X01")
      (footprint "eagle-import:1X01")
      (libsource (lib "eagle-import") (part "1X01"))
    )
    (comp (ref "JP200")
      (value "1X01")
      (footprint "eagle-import:1X01")
      (libsource (lib "eagle-import") (part "1X01"))
    )
    (comp (ref "JP201")
      (value "1X01")
      (footprint "eagle-import:1X01")
      (libsource (lib "eagle-import") (part "1X01"))
    )
    (comp (ref "JP202")
      (value "1X01")
      (footprint "eagle-import:1X01")
      (libsource (lib "eagle-import") (part "1X01"))
    )
    (comp (ref "JP203")
      (value "1X01")
      (footprint "eagle-import:1X01")
      (libsource (lib "eagle-import") (part "1X01"))
    )
    (comp (ref "JP204")
      (value "1X01")
      (footprint "eagle-import:1X01")
      (libsource (lib "eagle-import") (part "1X01"))
    )
    (comp (ref "JP205")
      (value "1X01")
      (footprint "eagle-import:1X01")
      (libsource (lib "eagle-import") (part "1X01"))
    )
    (comp (ref "JP206")
      (value "1X01")
      (footprint "eagle-import:1X01")
      (libsource (lib "eagle-import") (part "1X01"))
    )
    (comp (ref "JP207")
      (value "1X01")
      (footprint "eagle-import:1X01")
      (libsource (lib "eagle-import") (part "1X01"))
    )
    (comp (ref "JP208")
      (value "1X01")
      (footprint "eagle-import:1X01")
      (libsource (lib "eagle-import") (part "1X01"))
    )
    (comp (ref "JP209")
      (value "1X01")
      (footprint "eagle-import:1X01")
      (libsource (lib "eagle-import") (part "1X01"))
    )
    (comp (ref "JP210")
      (value "1X01")
      (footprint "eagle-import:1X01")
      (libsource (lib "eagle-import") (part "1X01"))
    )
    (comp (ref "JP211")
      (value "1X01")
      (footprint "eagle-import:1X01")
      (libsource (lib "eagle-import") (part "1X01"))
    )
    (comp (ref "JP212")
      (value "1X01")
      (footprint "eagle-import:1X01")
      (libsource (lib "eagle-import") (part "1X01"))
    )
    (comp (ref "JP213")
      (value "1X01")
      (footprint "eagle-import:1X01")
      (libsource (lib "eagle-import") (part "1X01"))
    )
    (comp (ref "JP214")
      (value "1X01")
      (footprint "eagle-import:1X01")
      (libsource (lib "eagle-import") (part "1X01"))
    )
    (comp (ref "JP215")
      (value "1X01")
      (footprint "eagle-import:1X01")
      (libsource (lib "eagle-import") (part "1X01"))
    )
    (comp (ref "JP216")
      (value "1X01")
      (footprint "eagle-import:1X01")
      (libsource (lib "eagle-import") (part "1X01"))
    )
    (comp (ref "JP217")
      (value "1X01")
      (footprint "eagle-import:1X01")
      (libsource (lib "eagle-import") (part "1X01"))
    )
    (comp (ref "JP218")
      (value "1X01")
      (footprint "eagle-import:1X01")
      (libsource (lib "eagle-import") (part "1X01"))
    )
    (comp (ref "JP219")
      (value "1X01")
      (footprint "eagle-import:1X01")
      (libsource (lib "eagle-import") (part "1X01"))
    )
    (comp (ref "JP220")
      (value "1X01")
      (footprint "eagle-import:1X01")
      (libsource (lib "eagle-import") (part "1X01"))
    )
    (comp (ref "JP221")
      (value "1X01")
      (footprint "eagle-import:1X01")
      (libsource (lib "eagle-import") (part "1X01"))
    )
    (comp (ref "JP222")
      (value "1X01")
      (footprint "eagle-import:1X01")
      (libsource (lib "eagle-import") (part "1X01"))
    )
    (comp (ref "JP223")
      (value "1X01")
      (footprint "eagle-import:1X01")
      (libsource (lib "eagle-import") (part "1X01"))
    )
    (comp (ref "JP224")
      (value "1X01")
      (footprint "eagle-import:1X01")
      (libsource (lib "eagle-import") (part "1X01"))
    )
    (comp (ref "JP225")
      (value "1X01")
      (footprint "eagle-import:1X01")
      (libsource (lib "eagle-import") (part "1X01"))
    )
    (comp (ref "JP226")
      (value "1X01")
      (footprint "eagle-import:1X01")
      (libsource (lib "eagle-import") (part "1X01"))
    )
    (comp (ref "JP227")
      (value "1X01")
      (footprint "eagle-import:1X01")
      (libsource (lib "eagle-import") (part "1X01"))
    )
    (comp (ref "JP228")
      (value "1X01")
      (footprint "eagle-import:1X01")
      (libsource (lib "eagle-import") (part "1X01"))
    )
    (comp (ref "JP229")
      (value "1X01")
      (footprint "eagle-import:1X01")
      (libsource (lib "eagle-import") (part "1X01"))
    )
    (comp (ref "JP230")
      (value "1X01")
      (footprint "eagle-import:1X01")
      (libsource (lib "eagle-import") (part "1X01"))
    )
    (comp (ref "JP231")
      (value "1X01")
      (footprint "eagle-import:1X01")
      (libsource (lib "eagle-import") (part "1X01"))
    )
    (comp (ref "JP232")
      (value "1X01")
      (footprint "eagle-import:1X01")
      (libsource (lib "eagle-import") (part "1X01"))
    )
    (comp (ref "JP233")
      (value "1X01")
      (footprint "eagle-import:1X01")
      (libsource (lib "eagle-import") (part "1X01"))
    )
    (comp (ref "JP234")
      (value "1X01")
      (footprint "eagle-import:1X01")
      (libsource (lib "eagle-import") (part "1X01"))
    )
    (comp (ref "JP235")
      (value "1X01")
      (footprint "eagle-import:1X01")
      (libsource (lib "eagle-import") (part "1X01"))
    )
    (comp (ref "JP236")
      (value "1X01")
      (footprint "eagle-import:1X01")
      (libsource (lib "eagle-import") (part "1X01"))
    )
    (comp (ref "JP237")
      (value "1X01")
      (footprint "eagle-import:1X01")
      (libsource (lib "eagle-import") (part "1X01"))
    )
    (comp (ref "JP238")
      (value "1X01")
      (footprint "eagle-import:1X01")
      (libsource (lib "eagle-import") (part "1X01"))
    )
    (comp (ref "JP239")
      (value "1X01")
      (footprint "eagle-import:1X01")
      (libsource (lib "eagle-import") (part "1X01"))
    )
    (comp (ref "JP240")
      (value "1X01")
      (footprint "eagle-import:1X01")
      (libsource (lib "eagle-import") (part "1X01"))
    )
    (comp (ref "JP241")
      (value "1X01")
      (footprint "eagle-import:1X01")
      (libsource (lib "eagle-import") (part "1X01"))
    )
    (comp (ref "JP242")
      (value "1X01")
      (footprint "eagle-import:1X01")
      (libsource (lib "eagle-import") (part "1X01"))
    )
    (comp (ref "JP243")
      (value "1X01")
      (footprint "eagle-import:1X01")
      (libsource (lib "eagle-import") (part "1X01"))
    )
    (comp (ref "JP244")
      (value "1X01")
      (footprint "eagle-import:1X01")
      (libsource (lib "eagle-import") (part "1X01"))
    )
    (comp (ref "JP245")
      (value "1X01")
      (footprint "eagle-import:1X01")
      (libsource (lib "eagle-import") (part "1X01"))
    )
    (comp (ref "JP246")
      (value "1X01")
      (footprint "eagle-import:1X01")
      (libsource (lib "eagle-import") (part "1X01"))
    )
    (comp (ref "JP247")
      (value "1X01")
      (footprint "eagle-import:1X01")
      (libsource (lib "eagle-import") (part "1X01"))
    )
    (comp (ref "JP248")
      (value "1X01")
      (footprint "eagle-import:1X01")
      (libsource (lib "eagle-import") (part "1X01"))
    )
    (comp (ref "JP249")
      (value "1X01")
      (footprint "eagle-import:1X01")
      (libsource (lib "eagle-import") (part "1X01"))
    )
    (comp (ref "JP250")
      (value "1X01")
      (footprint "eagle-import:1X01")
      (libsource (lib "eagle-import") (part "1X01"))
    )
    (comp (ref "JP251")
      (value "1X01")
      (footprint "eagle-import:1X01")
      (libsource (lib "eagle-import") (part "1X01"))
    )
    (comp (ref "JP252")
      (value "1X01")
      (footprint "eagle-import:1X01")
      (libsource (lib "eagle-import") (part "1X01"))
    )
    (comp (ref "JP253")
      (value "1X01")
      (footprint "eagle-import:1X01")
      (libsource (lib "eagle-import") (part "1X01"))
    )
    (comp (ref "JP254")
      (value "1X01")
      (footprint "eagle-import:1X01")
      (libsource (lib "eagle-import") (part "1X01"))
    )
    (comp (ref "JP255")
      (value "1X01")
      (footprint "eagle-import:1X01")
      (libsource (lib "eagle-import") (part "1X01"))
    )
    (comp (ref "JP256")
      (value "1X01")
      (footprint "eagle-import:1X01")
      (libsource (lib "eagle-import") (part "1X01"))
    )
    (comp (ref "JP257")
      (value "1X01")
      (footprint "eagle-import:1X01")
      (libsource (lib "eagle-import") (part "1X01"))
    )
    (comp (ref "JP258")
      (value "1X01")
      (footprint "eagle-import:1X01")
      (libsource (lib "eagle-import") (part "1X01"))
    )
    (comp (ref "JP259")
      (value "1X01")
      (footprint "eagle-import:1X01")
      (libsource (lib "eagle-import") (part "1X01"))
    )
    (comp (ref "JP260")
      (value "1X01")
      (footprint "eagle-import:1X01")
      (libsource (lib "eagle-import") (part "1X01"))
    )
    (comp (ref "JP261")
      (value "1X01")
      (footprint "eagle-import:1X01")
      (libsource (lib "eagle-import") (part "1X01"))
    )
    (comp (ref "JP262")
      (value "1X01")
      (footprint "eagle-import:1X01")
      (libsource (lib "eagle-import") (part "1X01"))
    )
    (comp (ref "JP263")
      (value "1X01")
      (footprint "eagle-import:1X01")
      (libsource (lib "eagle-import") (part "1X01"))
    )
    (comp (ref "JP264")
      (value "1X01")
      (footprint "eagle-import:1X01")
      (libsource (lib "eagle-import") (part "1X01"))
    )
    (comp (ref "JP265")
      (value "1X01")
      (footprint "eagle-import:1X01")
      (libsource (lib "eagle-import") (part "1X01"))
    )
    (comp (ref "JP266")
      (value "1X01")
      (footprint "eagle-import:1X01")
      (libsource (lib "eagle-import") (part "1X01"))
    )
    (comp (ref "JP267")
      (value "1X01")
      (footprint "eagle-import:1X01")
      (libsource (lib "eagle-import") (part "1X01"))
    )
    (comp (ref "JP268")
      (value "1X01")
      (footprint "eagle-import:1X01")
      (libsource (lib "eagle-import") (part "1X01"))
    )
    (comp (ref "JP269")
      (value "1X01")
      (footprint "eagle-import:1X01")
      (libsource (lib "eagle-import") (part "1X01"))
    )
    (comp (ref "JP270")
      (value "1X01")
      (footprint "eagle-import:1X01")
      (libsource (lib "eagle-import") (part "1X01"))
    )
    (comp (ref "JP271")
      (value "1X01")
      (footprint "eagle-import:1X01")
      (libsource (lib "eagle-import") (part "1X01"))
    )
    (comp (ref "JP272")
      (value "1X01")
      (footprint "eagle-import:1X01")
      (libsource (lib "eagle-import") (part "1X01"))
    )
    (comp (ref "JP273")
      (value "1X01")
      (footprint "eagle-import:1X01")
      (libsource (lib "eagle-import") (part "1X01"))
    )
    (comp (ref "JP274")
      (value "1X01")
      (footprint "eagle-import:1X01")
      (libsource (lib "eagle-import") (part "1X01"))
    )
    (comp (ref "JP275")
      (value "1X01")
      (footprint "eagle-import:1X01")
      (libsource (lib "eagle-import") (part "1X01"))
    )
    (comp (ref "JP276")
      (value "1X01")
      (footprint "eagle-import:1X01")
      (libsource (lib "eagle-import") (part "1X01"))
    )
    (comp (ref "JP277")
      (value "1X01")
      (footprint "eagle-import:1X01")
      (libsource (lib "eagle-import") (part "1X01"))
    )
    (comp (ref "JP278")
      (value "1X01")
      (footprint "eagle-import:1X01")
      (libsource (lib "eagle-import") (part "1X01"))
    )
    (comp (ref "JP279")
      (value "1X01")
      (footprint "eagle-import:1X01")
      (libsource (lib "eagle-import") (part "1X01"))
    )
    (comp (ref "JP280")
      (value "1X01")
      (footprint "eagle-import:1X01")
      (libsource (lib "eagle-import") (part "1X01"))
    )
    (comp (ref "JP281")
      (value "1X01")
      (footprint "eagle-import:1X01")
      (libsource (lib "eagle-import") (part "1X01"))
    )
    (comp (ref "JP282")
      (value "1X01")
      (footprint "eagle-import:1X01")
      (libsource (lib "eagle-import") (part "1X01"))
    )
    (comp (ref "JP283")
      (value "1X01")
      (footprint "eagle-import:1X01")
      (libsource (lib "eagle-import") (part "1X01"))
    )
    (comp (ref "JP284")
      (value "1X01")
      (footprint "eagle-import:1X01")
      (libsource (lib "eagle-import") (part "1X01"))
    )
    (comp (ref "JP285")
      (value "1X01")
      (footprint "eagle-import:1X01")
      (libsource (lib "eagle-import") (part "1X01"))
    )
    (comp (ref "JP286")
      (value "1X01")
      (footprint "eagle-import:1X01")
      (libsource (lib "eagle-import") (part "1X01"))
    )
    (comp (ref "JP287")
      (value "1X01")
      (footprint "eagle-import:1X01")
      (libsource (lib "eagle-import") (part "1X01"))
    )
    (comp (ref "JP288")
      (value "1X01")
      (footprint "eagle-import:1X01")
      (libsource (lib "eagle-import") (part "1X01"))
    )
    (comp (ref "JP289")
      (value "1X01")
      (footprint "eagle-import:1X01")
      (libsource (lib "eagle-import") (part "1X01"))
    )
    (comp (ref "JP290")
      (value "1X01")
      (footprint "eagle-import:1X01")
      (libsource (lib "eagle-import") (part "1X01"))
    )
    (comp (ref "JP291")
      (value "1X01")
      (footprint "eagle-import:1X01")
      (libsource (lib "eagle-import") (part "1X01"))
    )
    (comp (ref "JP292")
      (value "1X01")
      (footprint "eagle-import:1X01")
      (libsource (lib "eagle-import") (part "1X01"))
    )
    (comp (ref "JP293")
      (value "1X01")
      (footprint "eagle-import:1X01")
      (libsource (lib "eagle-import") (part "1X01"))
    )
    (comp (ref "JP294")
      (value "1X01")
      (footprint "eagle-import:1X01")
      (libsource (lib "eagle-import") (part "1X01"))
    )
    (comp (ref "JP295")
      (value "1X01")
      (footprint "eagle-import:1X01")
      (libsource (lib "eagle-import") (part "1X01"))
    )
    (comp (ref "JP296")
      (value "1X01")
      (footprint "eagle-import:1X01")
      (libsource (lib "eagle-import") (part "1X01"))
    )
    (comp (ref "JP297")
      (value "1X01")
      (footprint "eagle-import:1X01")
      (libsource (lib "eagle-import") (part "1X01"))
    )
    (comp (ref "JP298")
      (value "1X01")
      (footprint "eagle-import:1X01")
      (libsource (lib "eagle-import") (part "1X01"))
    )
    (comp (ref "JP299")
      (value "1X01")
      (footprint "eagle-import:1X01")
      (libsource (lib "eagle-import") (part "1X01"))
    )
    (comp (ref "JP300")
      (value "1X01")
      (footprint "eagle-import:1X01")
      (libsource (lib "eagle-import") (part "1X01"))
    )
    (comp (ref "JP301")
      (value "1X01")
      (footprint "eagle-import:1X01")
      (libsource (lib "eagle-import") (part "1X01"))
    )
    (comp (ref "JP302")
      (value "1X01")
      (footprint "eagle-import:1X01")
      (libsource (lib "eagle-import") (part "1X01"))
    )
    (comp (ref "JP303")
      (value "1X01")
      (footprint "eagle-import:1X01")
      (libsource (lib "eagle-import") (part "1X01"))
    )
    (comp (ref "JP304")
      (value "1X01")
      (footprint "eagle-import:1X01")
      (libsource (lib "eagle-import") (part "1X01"))
    )
    (comp (ref "JP305")
      (value "1X01")
      (footprint "eagle-import:1X01")
      (libsource (lib "eagle-import") (part "1X01"))
    )
    (comp (ref "JP306")
      (value "1X01")
      (footprint "eagle-import:1X01")
      (libsource (lib "eagle-import") (part "1X01"))
    )
    (comp (ref "JP307")
      (value "1X01")
      (footprint "eagle-import:1X01")
      (libsource (lib "eagle-import") (part "1X01"))
    )
    (comp (ref "JP308")
      (value "1X01")
      (footprint "eagle-import:1X01")
      (libsource (lib "eagle-import") (part "1X01"))
    )
    (comp (ref "JP309")
      (value "1X01")
      (footprint "eagle-import:1X01")
      (libsource (lib "eagle-import") (part "1X01"))
    )
    (comp (ref "JP310")
      (value "1X01")
      (footprint "eagle-import:1X01")
      (libsource (lib "eagle-import") (part "1X01"))
    )
    (comp (ref "JP311")
      (value "1X01")
      (footprint "eagle-import:1X01")
      (libsource (lib "eagle-import") (part "1X01"))
    )
    (comp (ref "JP312")
      (value "1X01")
      (footprint "eagle-import:1X01")
      (libsource (lib "eagle-import") (part "1X01"))
    )
    (comp (ref "JP313")
      (value "1X01")
      (footprint "eagle-import:1X01")
      (libsource (lib "eagle-import") (part "1X01"))
    )
    (comp (ref "JP314")
      (value "1X01")
      (footprint "eagle-import:1X01")
      (libsource (lib "eagle-import") (part "1X01"))
    )
    (comp (ref "JP315")
      (value "1X01")
      (footprint "eagle-import:1X01")
      (libsource (lib "eagle-import") (part "1X01"))
    )
    (comp (ref "JP316")
      (value "1X01")
      (footprint "eagle-import:1X01")
      (libsource (lib "eagle-import") (part "1X01"))
    )
    (comp (ref "JP317")
      (value "1X01")
      (footprint "eagle-import:1X01")
      (libsource (lib "eagle-import") (part "1X01"))
    )
    (comp (ref "JP318")
      (value "1X01")
      (footprint "eagle-import:1X01")
      (libsource (lib "eagle-import") (part "1X01"))
    )
    (comp (ref "JP319")
      (value "1X01")
      (footprint "eagle-import:1X01")
      (libsource (lib "eagle-import") (part "1X01"))
    )
    (comp (ref "JP320")
      (value "1X01")
      (footprint "eagle-import:1X01")
      (libsource (lib "eagle-import") (part "1X01"))
    )
    (comp (ref "JP321")
      (value "1X01")
      (footprint "eagle-import:1X01")
      (libsource (lib "eagle-import") (part "1X01"))
    )
    (comp (ref "JP322")
      (value "1X01")
      (footprint "eagle-import:1X01")
      (libsource (lib "eagle-import") (part "1X01"))
    )
    (comp (ref "JP323")
      (value "1X01")
      (footprint "eagle-import:1X01")
      (libsource (lib "eagle-import") (part "1X01"))
    )
    (comp (ref "JP324")
      (value "1X01")
      (footprint "eagle-import:1X01")
      (libsource (lib "eagle-import") (part "1X01"))
    )
    (comp (ref "JP325")
      (value "1X01")
      (footprint "eagle-import:1X01")
      (libsource (lib "eagle-import") (part "1X01"))
    )
    (comp (ref "JP326")
      (value "1X01")
      (footprint "eagle-import:1X01")
      (libsource (lib "eagle-import") (part "1X01"))
    )
    (comp (ref "JP327")
      (value "1X01")
      (footprint "eagle-import:1X01")
      (libsource (lib "eagle-import") (part "1X01"))
    )
    (comp (ref "JP328")
      (value "1X01")
      (footprint "eagle-import:1X01")
      (libsource (lib "eagle-import") (part "1X01"))
    )
    (comp (ref "JP329")
      (value "1X01")
      (footprint "eagle-import:1X01")
      (libsource (lib "eagle-import") (part "1X01"))
    )
    (comp (ref "JP330")
      (value "1X01")
      (footprint "eagle-import:1X01")
      (libsource (lib "eagle-import") (part "1X01"))
    )
    (comp (ref "JP331")
      (value "1X01")
      (footprint "eagle-import:1X01")
      (libsource (lib "eagle-import") (part "1X01"))
    )
    (comp (ref "JP332")
      (value "1X01")
      (footprint "eagle-import:1X01")
      (libsource (lib "eagle-import") (part "1X01"))
    )
    (comp (ref "JP333")
      (value "1X01")
      (footprint "eagle-import:1X01")
      (libsource (lib "eagle-import") (part "1X01"))
    )
    (comp (ref "JP334")
      (value "1X01")
      (footprint "eagle-import:1X01")
      (libsource (lib "eagle-import") (part "1X01"))
    )
    (comp (ref "JP335")
      (value "1X01")
      (footprint "eagle-import:1X01")
      (libsource (lib "eagle-import") (part "1X01"))
    )
    (comp (ref "JP336")
      (value "1X01")
      (footprint "eagle-import:1X01")
      (libsource (lib "eagle-import") (part "1X01"))
    )
    (comp (ref "JP337")
      (value "1X01")
      (footprint "eagle-import:1X01")
      (libsource (lib "eagle-import") (part "1X01"))
    )
    (comp (ref "JP338")
      (value "1X01")
      (footprint "eagle-import:1X01")
      (libsource (lib "eagle-import") (part "1X01"))
    )
    (comp (ref "JP339")
      (value "1X01")
      (footprint "eagle-import:1X01")
      (libsource (lib "eagle-import") (part "1X01"))
    )
    (comp (ref "JP340")
      (value "1X01")
      (footprint "eagle-import:1X01")
      (libsource (lib "eagle-import") (part "1X01"))
    )
    (comp (ref "JP341")
      (value "1X01")
      (footprint "eagle-import:1X01")
      (libsource (lib "eagle-import") (part "1X01"))
    )
    (comp (ref "JP342")
      (value "1X01")
      (footprint "eagle-import:1X01")
      (libsource (lib "eagle-import") (part "1X01"))
    )
    (comp (ref "JP343")
      (value "1X01")
      (footprint "eagle-import:1X01")
      (libsource (lib "eagle-import") (part "1X01"))
    )
    (comp (ref "JP344")
      (value "1X01")
      (footprint "eagle-import:1X01")
      (libsource (lib "eagle-import") (part "1X01"))
    )
    (comp (ref "JP345")
      (value "1X01")
      (footprint "eagle-import:1X01")
      (libsource (lib "eagle-import") (part "1X01"))
    )
    (comp (ref "JP346")
      (value "1X01")
      (footprint "eagle-import:1X01")
      (libsource (lib "eagle-import") (part "1X01"))
    )
    (comp (ref "JP347")
      (value "1X01")
      (footprint "eagle-import:1X01")
      (libsource (lib "eagle-import") (part "1X01"))
    )
    (comp (ref "JP348")
      (value "1X01")
      (footprint "eagle-import:1X01")
      (libsource (lib "eagle-import") (part "1X01"))
    )
    (comp (ref "JP349")
      (value "1X01")
      (footprint "eagle-import:1X01")
      (libsource (lib "eagle-import") (part "1X01"))
    )
    (comp (ref "JP350")
      (value "1X01")
      (footprint "eagle-import:1X01")
      (libsource (lib "eagle-import") (part "1X01"))
    )
    (comp (ref "JP351")
      (value "1X01")
      (footprint "eagle-import:1X01")
      (libsource (lib "eagle-import") (part "1X01"))
    )
    (comp (ref "JP352")
      (value "1X01")
      (footprint "eagle-import:1X01")
      (libsource (lib "eagle-import") (part "1X01"))
    )
    (comp (ref "JP353")
      (value "1X01")
      (footprint "eagle-import:1X01")
      (libsource (lib "eagle-import") (part "1X01"))
    )
    (comp (ref "JP354")
      (value "1X01")
      (footprint "eagle-import:1X01")
      (libsource (lib "eagle-import") (part "1X01"))
    )
    (comp (ref "JP355")
      (value "1X01")
      (footprint "eagle-import:1X01")
      (libsource (lib "eagle-import") (part "1X01"))
    )
    (comp (ref "JP356")
      (value "1X01")
      (footprint "eagle-import:1X01")
      (libsource (lib "eagle-import") (part "1X01"))
    )
    (comp (ref "JP357")
      (value "1X01")
      (footprint "eagle-import:1X01")
      (libsource (lib "eagle-import") (part "1X01"))
    )
    (comp (ref "JP358")
      (value "1X01")
      (footprint "eagle-import:1X01")
      (libsource (lib "eagle-import") (part "1X01"))
    )
    (comp (ref "JP359")
      (value "1X01")
      (footprint "eagle-import:1X01")
      (libsource (lib "eagle-import") (part "1X01"))
    )
    (comp (ref "JP360")
      (value "1X01")
      (footprint "eagle-import:1X01")
      (libsource (lib "eagle-import") (part "1X01"))
    )
    (comp (ref "JP361")
      (value "1X01")
      (footprint "eagle-import:1X01")
      (libsource (lib "eagle-import") (part "1X01"))
    )
    (comp (ref "JP362")
      (value "1X01")
      (footprint "eagle-import:1X01")
      (libsource (lib "eagle-import") (part "1X01"))
    )
    (comp (ref "JP363")
      (value "1X01")
      (footprint "eagle-import:1X01")
      (libsource (lib "eagle-import") (part "1X01"))
    )
    (comp (ref "JP364")
      (value "1X01")
      (footprint "eagle-import:1X01")
      (libsource (lib "eagle-import") (part "1X01"))
    )
    (comp (ref "JP365")
      (value "1X01")
      (footprint "eagle-import:1X01")
      (libsource (lib "eagle-import") (part "1X01"))
    )
    (comp (ref "JP366")
      (value "1X01")
      (footprint "eagle-import:1X01")
      (libsource (lib "eagle-import") (part "1X01"))
    )
    (comp (ref "JP367")
      (value "1X01")
      (footprint "eagle-import:1X01")
      (libsource (lib "eagle-import") (part "1X01"))
    )
    (comp (ref "JP368")
      (value "1X01")
      (footprint "eagle-import:1X01")
      (libsource (lib "eagle-import") (part "1X01"))
    )
    (comp (ref "JP369")
      (value "1X01")
      (footprint "eagle-import:1X01")
      (libsource (lib "eagle-import") (part "1X01"))
    )
    (comp (ref "JP370")
      (value "1X01")
      (footprint "eagle-import:1X01")
      (libsource (lib "eagle-import") (part "1X01"))
    )
    (comp (ref "JP371")
      (value "1X01")
      (footprint "eagle-import:1X01")
      (libsource (lib "eagle-import") (part "1X01"))
    )
    (comp (ref "JP372")
      (value "1X01")
      (footprint "eagle-import:1X01")
      (libsource (lib "eagle-import") (part "1X01"))
    )
    (comp (ref "JP373")
      (value "1X01")
      (footprint "eagle-import:1X01")
      (libsource (lib "eagle-import") (part "1X01"))
    )
    (comp (ref "JP374")
      (value "1X01")
      (footprint "eagle-import:1X01")
      (libsource (lib "eagle-import") (part "1X01"))
    )
    (comp (ref "JP375")
      (value "1X01")
      (footprint "eagle-import:1X01")
      (libsource (lib "eagle-import") (part "1X01"))
    )
    (comp (ref "JP376")
      (value "1X01")
      (footprint "eagle-import:1X01")
      (libsource (lib "eagle-import") (part "1X01"))
    )
    (comp (ref "JP377")
      (value "1X01")
      (footprint "eagle-import:1X01")
      (libsource (lib "eagle-import") (part "1X01"))
    )
    (comp (ref "JP378")
      (value "1X01")
      (footprint "eagle-import:1X01")
      (libsource (lib "eagle-import") (part "1X01"))
    )
    (comp (ref "JP379")
      (value "1X01")
      (footprint "eagle-import:1X01")
      (libsource (lib "eagle-import") (part "1X01"))
    )
    (comp (ref "JP380")
      (value "1X01")
      (footprint "eagle-import:1X01")
      (libsource (lib "eagle-import") (part "1X01"))
    )
    (comp (ref "JP381")
      (value "1X01")
      (footprint "eagle-import:1X01")
      (libsource (lib "eagle-import") (part "1X01"))
    )
    (comp (ref "JP382")
      (value "1X01")
      (footprint "eagle-import:1X01")
      (libsource (lib "eagle-import") (part "1X01"))
    )
    (comp (ref "JP383")
      (value "1X01")
      (footprint "eagle-import:1X01")
      (libsource (lib "eagle-import") (part "1X01"))
    )
    (comp (ref "JP384")
      (value "1X01")
      (footprint "eagle-import:1X01")
      (libsource (lib "eagle-import") (part "1X01"))
    )
    (comp (ref "JP385")
      (value "1X01")
      (footprint "eagle-import:1X01")
      (libsource (lib "eagle-import") (part "1X01"))
    )
    (comp (ref "JP386")
      (value "1X01")
      (footprint "eagle-import:1X01")
      (libsource (lib "eagle-import") (part "1X01"))
    )
    (comp (ref "JP387")
      (value "1X01")
      (footprint "eagle-import:1X01")
      (libsource (lib "eagle-import") (part "1X01"))
    )
    (comp (ref "JP388")
      (value "1X01")
      (footprint "eagle-import:1X01")
      (libsource (lib "eagle-import") (part "1X01"))
    )
    (comp (ref "JP389")
      (value "1X01")
      (footprint "eagle-import:1X01")
      (libsource (lib "eagle-import") (part "1X01"))
    )
    (comp (ref "JP390")
      (value "1X01")
      (footprint "eagle-import:1X01")
      (libsource (lib "eagle-import") (part "1X01"))
    )
    (comp (ref "JP391")
      (value "1X01")
      (footprint "eagle-import:1X01")
      (libsource (lib "eagle-import") (part "1X01"))
    )
    (comp (ref "JP392")
      (value "1X01")
      (footprint "eagle-import:1X01")
      (libsource (lib "eagle-import") (part "1X01"))
    )
    (comp (ref "JP393")
      (value "1X01")
      (footprint "eagle-import:1X01")
      (libsource (lib "eagle-import") (part "1X01"))
    )
    (comp (ref "JP394")
      (value "1X01")
      (footprint "eagle-import:1X01")
      (libsource (lib "eagle-import") (part "1X01"))
    )
    (comp (ref "JP395")
      (value "1X01")
      (footprint "eagle-import:1X01")
      (libsource (lib "eagle-import") (part "1X01"))
    )
    (comp (ref "JP396")
      (value "1X01")
      (footprint "eagle-import:1X01")
      (libsource (lib "eagle-import") (part "1X01"))
    )
    (comp (ref "JP397")
      (value "1X01")
      (footprint "eagle-import:1X01")
      (libsource (lib "eagle-import") (part "1X01"))
    )
    (comp (ref "JP398")
      (value "1X01")
      (footprint "eagle-import:1X01")
      (libsource (lib "eagle-import") (part "1X01"))
    )
    (comp (ref "JP399")
      (value "1X01")
      (footprint "eagle-import:1X01")
      (libsource (lib "eagle-import") (part "1X01"))
    )
    (comp (ref "JP400")
      (value "1X01")
      (footprint "eagle-import:1X01")
      (libsource (lib "eagle-import") (part "1X01"))
    )
    (comp (ref "JP401")
      (value "1X01")
      (footprint "eagle-import:1X01")
      (libsource (lib "eagle-import") (part "1X01"))
    )
    (comp (ref "JP402")
      (value "1X01")
      (footprint "eagle-import:1X01")
      (libsource (lib "eagle-import") (part "1X01"))
    )
    (comp (ref "JP403")
      (value "1X01")
      (footprint "eagle-import:1X01")
      (libsource (lib "eagle-import") (part "1X01"))
    )
    (comp (ref "JP404")
      (value "1X01")
      (footprint "eagle-import:1X01")
      (libsource (lib "eagle-import") (part "1X01"))
    )
    (comp (ref "JP405")
      (value "1X01")
      (footprint "eagle-import:1X01")
      (libsource (lib "eagle-import") (part "1X01"))
    )
    (comp (ref "JP406")
      (value "1X01")
      (footprint "eagle-import:1X01")
      (libsource (lib "eagle-import") (part "1X01"))
    )
    (comp (ref "JP407")
      (value "1X01")
      (footprint "eagle-import:1X01")
      (libsource (lib "eagle-import") (part "1X01"))
    )
    (comp (ref "JP408")
      (value "1X01")
      (footprint "eagle-import:1X01")
      (libsource (lib "eagle-import") (part "1X01"))
    )
    (comp (ref "JP409")
      (value "1X01")
      (footprint "eagle-import:1X01")
      (libsource (lib "eagle-import") (part "1X01"))
    )
    (comp (ref "JP410")
      (value "1X01")
      (footprint "eagle-import:1X01")
      (libsource (lib "eagle-import") (part "1X01"))
    )
    (comp (ref "JP411")
      (value "1X01")
      (footprint "eagle-import:1X01")
      (libsource (lib "eagle-import") (part "1X01"))
    )
    (comp (ref "JP412")
      (value "1X01")
      (footprint "eagle-import:1X01")
      (libsource (lib "eagle-import") (part "1X01"))
    )
    (comp (ref "JP413")
      (value "1X01")
      (footprint "eagle-import:1X01")
      (libsource (lib "eagle-import") (part "1X01"))
    )
    (comp (ref "JP414")
      (value "1X01")
      (footprint "eagle-import:1X01")
      (libsource (lib "eagle-import") (part "1X01"))
    )
    (comp (ref "JP415")
      (value "1X01")
      (footprint "eagle-import:1X01")
      (libsource (lib "eagle-import") (part "1X01"))
    )
    (comp (ref "JP416")
      (value "1X01")
      (footprint "eagle-import:1X01")
      (libsource (lib "eagle-import") (part "1X01"))
    )
    (comp (ref "JP417")
      (value "1X01")
      (footprint "eagle-import:1X01")
      (libsource (lib "eagle-import") (part "1X01"))
    )
    (comp (ref "JP418")
      (value "1X01")
      (footprint "eagle-import:1X01")
      (libsource (lib "eagle-import") (part "1X01"))
    )
    (comp (ref "JP419")
      (value "1X01")
      (footprint "eagle-import:1X01")
      (libsource (lib "eagle-import") (part "1X01"))
    )
    (comp (ref "JP420")
      (value "1X01")
      (footprint "eagle-import:1X01")
      (libsource (lib "eagle-import") (part "1X01"))
    )
    (comp (ref "JP421")
      (value "1X01")
      (footprint "eagle-import:1X01")
      (libsource (lib "eagle-import") (part "1X01"))
    )
    (comp (ref "JP422")
      (value "1X01")
      (footprint "eagle-import:1X01")
      (libsource (lib "eagle-import") (part "1X01"))
    )
    (comp (ref "JP423")
      (value "1X01")
      (footprint "eagle-import:1X01")
      (libsource (lib "eagle-import") (part "1X01"))
    )
    (comp (ref "JP424")
      (value "1X01")
      (footprint "eagle-import:1X01")
      (libsource (lib "eagle-import") (part "1X01"))
    )
    (comp (ref "JP425")
      (value "1X01")
      (footprint "eagle-import:1X01")
      (libsource (lib "eagle-import") (part "1X01"))
    )
    (comp (ref "JP426")
      (value "1X01")
      (footprint "eagle-import:1X01")
      (libsource (lib "eagle-import") (part "1X01"))
    )
    (comp (ref "JP427")
      (value "1X01")
      (footprint "eagle-import:1X01")
      (libsource (lib "eagle-import") (part "1X01"))
    )
    (comp (ref "JP428")
      (value "1X01")
      (footprint "eagle-import:1X01")
      (libsource (lib "eagle-import") (part "1X01"))
    )
    (comp (ref "JP429")
      (value "1X01")
      (footprint "eagle-import:1X01")
      (libsource (lib "eagle-import") (part "1X01"))
    )
    (comp (ref "JP430")
      (value "1X01")
      (footprint "eagle-import:1X01")
      (libsource (lib "eagle-import") (part "1X01"))
    )
    (comp (ref "JP431")
      (value "1X01")
      (footprint "eagle-import:1X01")
      (libsource (lib "eagle-import") (part "1X01"))
    )
    (comp (ref "JP432")
      (value "1X01")
      (footprint "eagle-import:1X01")
      (libsource (lib "eagle-import") (part "1X01"))
    )
    (comp (ref "JP433")
      (value "1X01")
      (footprint "eagle-import:1X01")
      (libsource (lib "eagle-import") (part "1X01"))
    )
    (comp (ref "JP434")
      (value "1X01")
      (footprint "eagle-import:1X01")
      (libsource (lib "eagle-import") (part "1X01"))
    )
    (comp (ref "JP435")
      (value "1X01")
      (footprint "eagle-import:1X01")
      (libsource (lib "eagle-import") (part "1X01"))
    )
    (comp (ref "JP436")
      (value "1X01")
      (footprint "eagle-import:1X01")
      (libsource (lib "eagle-import") (part "1X01"))
    )
    (comp (ref "JP437")
      (value "1X01")
      (footprint "eagle-import:1X01")
      (libsource (lib "eagle-import") (part "1X01"))
    )
    (comp (ref "JP438")
      (value "1X01")
      (footprint "eagle-import:1X01")
      (libsource (lib "eagle-import") (part "1X01"))
    )
    (comp (ref "JP439")
      (value "1X01")
      (footprint "eagle-import:1X01")
      (libsource (lib "eagle-import") (part "1X01"))
    )
    (comp (ref "JP440")
      (value "1X01")
      (footprint "eagle-import:1X01")
      (libsource (lib "eagle-import") (part "1X01"))
    )
    (comp (ref "JP441")
      (value "1X01")
      (footprint "eagle-import:1X01")
      (libsource (lib "eagle-import") (part "1X01"))
    )
    (comp (ref "JP442")
      (value "1X01")
      (footprint "eagle-import:1X01")
      (libsource (lib "eagle-import") (part "1X01"))
    )
    (comp (ref "JP443")
      (value "1X01")
      (footprint "eagle-import:1X01")
      (libsource (lib "eagle-import") (part "1X01"))
    )
    (comp (ref "JP444")
      (value "1X01")
      (footprint "eagle-import:1X01")
      (libsource (lib "eagle-import") (part "1X01"))
    )
    (comp (ref "JP445")
      (value "1X01")
      (footprint "eagle-import:1X01")
      (libsource (lib "eagle-import") (part "1X01"))
    )
    (comp (ref "JP446")
      (value "1X01")
      (footprint "eagle-import:1X01")
      (libsource (lib "eagle-import") (part "1X01"))
    )
    (comp (ref "JP447")
      (value "1X01")
      (footprint "eagle-import:1X01")
      (libsource (lib "eagle-import") (part "1X01"))
    )
    (comp (ref "JP448")
      (value "1X01")
      (footprint "eagle-import:1X01")
      (libsource (lib "eagle-import") (part "1X01"))
    )
    (comp (ref "JP449")
      (value "1X01")
      (footprint "eagle-import:1X01")
      (libsource (lib "eagle-import") (part "1X01"))
    )
    (comp (ref "JP450")
      (value "1X01")
      (footprint "eagle-import:1X01")
      (libsource (lib "eagle-import") (part "1X01"))
    )
    (comp (ref "JP451")
      (value "1X01")
      (footprint "eagle-import:1X01")
      (libsource (lib "eagle-import") (part "1X01"))
    )
    (comp (ref "JP452")
      (value "1X01")
      (footprint "eagle-import:1X01")
      (libsource (lib "eagle-import") (part "1X01"))
    )
    (comp (ref "JP453")
      (value "1X01")
      (footprint "eagle-import:1X01")
      (libsource (lib "eagle-import") (part "1X01"))
    )
    (comp (ref "JP454")
      (value "1X01")
      (footprint "eagle-import:1X01")
      (libsource (lib "eagle-import") (part "1X01"))
    )
    (comp (ref "JP455")
      (value "1X01")
      (footprint "eagle-import:1X01")
      (libsource (lib "eagle-import") (part "1X01"))
    )
    (comp (ref "JP456")
      (value "1X01")
      (footprint "eagle-import:1X01")
      (libsource (lib "eagle-import") (part "1X01"))
    )
    (comp (ref "JP457")
      (value "1X01")
      (footprint "eagle-import:1X01")
      (libsource (lib "eagle-import") (part "1X01"))
    )
    (comp (ref "JP458")
      (value "1X01")
      (footprint "eagle-import:1X01")
      (libsource (lib "eagle-import") (part "1X01"))
    )
    (comp (ref "JP459")
      (value "1X01")
      (footprint "eagle-import:1X01")
      (libsource (lib "eagle-import") (part "1X01"))
    )
    (comp (ref "JP460")
      (value "1X01")
      (footprint "eagle-import:1X01")
      (libsource (lib "eagle-import") (part "1X01"))
    )
    (comp (ref "JP461")
      (value "1X01")
      (footprint "eagle-import:1X01")
      (libsource (lib "eagle-import") (part "1X01"))
    )
    (comp (ref "JP462")
      (value "1X01")
      (footprint "eagle-import:1X01")
      (libsource (lib "eagle-import") (part "1X01"))
    )
    (comp (ref "JP463")
      (value "1X01")
      (footprint "eagle-import:1X01")
      (libsource (lib "eagle-import") (part "1X01"))
    )
    (comp (ref "JP464")
      (value "1X01")
      (footprint "eagle-import:1X01")
      (libsource (lib "eagle-import") (part "1X01"))
    )
    (comp (ref "JP465")
      (value "1X01")
      (footprint "eagle-import:1X01")
      (libsource (lib "eagle-import") (part "1X01"))
    )
    (comp (ref "JP466")
      (value "1X01")
      (footprint "eagle-import:1X01")
      (libsource (lib "eagle-import") (part "1X01"))
    )
    (comp (ref "JP467")
      (value "1X01")
      (footprint "eagle-import:1X01")
      (libsource (lib "eagle-import") (part "1X01"))
    )
    (comp (ref "JP468")
      (value "1X01")
      (footprint "eagle-import:1X01")
      (libsource (lib "eagle-import") (part "1X01"))
    )
    (comp (ref "JP469")
      (value "1X01")
      (footprint "eagle-import:1X01")
      (libsource (lib "eagle-import") (part "1X01"))
    )
    (comp (ref "JP470")
      (value "1X01")
      (footprint "eagle-import:1X01")
      (libsource (lib "eagle-import") (part "1X01"))
    )
    (comp (ref "JP471")
      (value "1X01")
      (footprint "eagle-import:1X01")
      (libsource (lib "eagle-import") (part "1X01"))
    )
    (comp (ref "JP472")
      (value "1X01")
      (footprint "eagle-import:1X01")
      (libsource (lib "eagle-import") (part "1X01"))
    )
    (comp (ref "JP473")
      (value "1X01")
      (footprint "eagle-import:1X01")
      (libsource (lib "eagle-import") (part "1X01"))
    )
    (comp (ref "JP474")
      (value "1X01")
      (footprint "eagle-import:1X01")
      (libsource (lib "eagle-import") (part "1X01"))
    )
    (comp (ref "JP475")
      (value "1X01")
      (footprint "eagle-import:1X01")
      (libsource (lib "eagle-import") (part "1X01"))
    )
    (comp (ref "JP476")
      (value "1X01")
      (footprint "eagle-import:1X01")
      (libsource (lib "eagle-import") (part "1X01"))
    )
    (comp (ref "JP477")
      (value "1X01")
      (footprint "eagle-import:1X01")
      (libsource (lib "eagle-import") (part "1X01"))
    )
    (comp (ref "JP478")
      (value "1X01")
      (footprint "eagle-import:1X01")
      (libsource (lib "eagle-import") (part "1X01"))
    )
    (comp (ref "JP479")
      (value "1X01")
      (footprint "eagle-import:1X01")
      (libsource (lib "eagle-import") (part "1X01"))
    )
    (comp (ref "JP480")
      (value "1X01")
      (footprint "eagle-import:1X01")
      (libsource (lib "eagle-import") (part "1X01"))
    )
    (comp (ref "JP481")
      (value "1X01")
      (footprint "eagle-import:1X01")
      (libsource (lib "eagle-import") (part "1X01"))
    )
    (comp (ref "JP482")
      (value "1X01")
      (footprint "eagle-import:1X01")
      (libsource (lib "eagle-import") (part "1X01"))
    )
    (comp (ref "JP483")
      (value "1X01")
      (footprint "eagle-import:1X01")
      (libsource (lib "eagle-import") (part "1X01"))
    )
    (comp (ref "JP484")
      (value "1X01")
      (footprint "eagle-import:1X01")
      (libsource (lib "eagle-import") (part "1X01"))
    )
    (comp (ref "JP485")
      (value "1X01")
      (footprint "eagle-import:1X01")
      (libsource (lib "eagle-import") (part "1X01"))
    )
    (comp (ref "JP486")
      (value "1X01")
      (footprint "eagle-import:1X01")
      (libsource (lib "eagle-import") (part "1X01"))
    )
    (comp (ref "JP487")
      (value "1X01")
      (footprint "eagle-import:1X01")
      (libsource (lib "eagle-import") (part "1X01"))
    )
    (comp (ref "JP488")
      (value "1X01")
      (footprint "eagle-import:1X01")
      (libsource (lib "eagle-import") (part "1X01"))
    )
    (comp (ref "JP489")
      (value "1X01")
      (footprint "eagle-import:1X01")
      (libsource (lib "eagle-import") (part "1X01"))
    )
    (comp (ref "JP490")
      (value "1X01")
      (footprint "eagle-import:1X01")
      (libsource (lib "eagle-import") (part "1X01"))
    )
    (comp (ref "JP491")
      (value "1X01")
      (footprint "eagle-import:1X01")
      (libsource (lib "eagle-import") (part "1X01"))
    )
    (comp (ref "JP492")
      (value "1X01")
      (footprint "eagle-import:1X01")
      (libsource (lib "eagle-import") (part "1X01"))
    )
    (comp (ref "JP493")
      (value "1X01")
      (footprint "eagle-import:1X01")
      (libsource (lib "eagle-import") (part "1X01"))
    )
    (comp (ref "JP494")
      (value "1X01")
      (footprint "eagle-import:1X01")
      (libsource (lib "eagle-import") (part "1X01"))
    )
    (comp (ref "JP495")
      (value "1X01")
      (footprint "eagle-import:1X01")
      (libsource (lib "eagle-import") (part "1X01"))
    )
    (comp (ref "JP496")
      (value "1X01")
      (footprint "eagle-import:1X01")
      (libsource (lib "eagle-import") (part "1X01"))
    )
    (comp (ref "JP497")
      (value "1X01")
      (footprint "eagle-import:1X01")
      (libsource (lib "eagle-import") (part "1X01"))
    )
    (comp (ref "JP498")
      (value "1X01")
      (footprint "eagle-import:1X01")
      (libsource (lib "eagle-import") (part "1X01"))
    )
    (comp (ref "JP499")
      (value "1X01")
      (footprint "eagle-import:1X01")
      (libsource (lib "eagle-import") (part "1X01"))
    )
    (comp (ref "JP500")
      (value "1X01")
      (footprint "eagle-import:1X01")
      (libsource (lib "eagle-import") (part "1X01"))
    )
    (comp (ref "JP501")
      (value "1X01")
      (footprint "eagle-import:1X01")
      (libsource (lib "eagle-import") (part "1X01"))
    )
    (comp (ref "JP502")
      (value "1X01")
      (footprint "eagle-import:1X01")
      (libsource (lib "eagle-import") (part "1X01"))
    )
    (comp (ref "JP503")
      (value "1X01")
      (footprint "eagle-import:1X01")
      (libsource (lib "eagle-import") (part "1X01"))
    )
    (comp (ref "JP504")
      (value "1X01")
      (footprint "eagle-import:1X01")
      (libsource (lib "eagle-import") (part "1X01"))
    )
    (comp (ref "JP505")
      (value "1X01")
      (footprint "eagle-import:1X01")
      (libsource (lib "eagle-import") (part "1X01"))
    )
    (comp (ref "JP506")
      (value "1X01")
      (footprint "eagle-import:1X01")
      (libsource (lib "eagle-import") (part "1X01"))
    )
    (comp (ref "JP507")
      (value "1X01")
      (footprint "eagle-import:1X01")
      (libsource (lib "eagle-import") (part "1X01"))
    )
    (comp (ref "JP508")
      (value "1X01")
      (footprint "eagle-import:1X01")
      (libsource (lib "eagle-import") (part "1X01"))
    )
    (comp (ref "JP509")
      (value "1X01")
      (footprint "eagle-import:1X01")
      (libsource (lib "eagle-import") (part "1X01"))
    )
    (comp (ref "JP510")
      (value "1X01")
      (footprint "eagle-import:1X01")
      (libsource (lib "eagle-import") (part "1X01"))
    )
    (comp (ref "JP511")
      (value "1X01")
      (footprint "eagle-import:1X01")
      (libsource (lib "eagle-import") (part "1X01"))
    )
    (comp (ref "JP512")
      (value "1X01")
      (footprint "eagle-import:1X01")
      (libsource (lib "eagle-import") (part "1X01"))
    )
    (comp (ref "JP513")
      (value "1X01")
      (footprint "eagle-import:1X01")
      (libsource (lib "eagle-import") (part "1X01"))
    )
    (comp (ref "JP514")
      (value "1X01")
      (footprint "eagle-import:1X01")
      (libsource (lib "eagle-import") (part "1X01"))
    )
    (comp (ref "JP515")
      (value "1X01")
      (footprint "eagle-import:1X01")
      (libsource (lib "eagle-import") (part "1X01"))
    )
    (comp (ref "JP516")
      (value "1X01")
      (footprint "eagle-import:1X01")
      (libsource (lib "eagle-import") (part "1X01"))
    )
    (comp (ref "JP517")
      (value "1X01")
      (footprint "eagle-import:1X01")
      (libsource (lib "eagle-import") (part "1X01"))
    )
    (comp (ref "JP518")
      (value "1X01")
      (footprint "eagle-import:1X01")
      (libsource (lib "eagle-import") (part "1X01"))
    )
    (comp (ref "JP519")
      (value "1X01")
      (footprint "eagle-import:1X01")
      (libsource (lib "eagle-import") (part "1X01"))
    )
    (comp (ref "JP520")
      (value "1X01")
      (footprint "eagle-import:1X01")
      (libsource (lib "eagle-import") (part "1X01"))
    )
    (comp (ref "JP521")
      (value "1X01")
      (footprint "eagle-import:1X01")
      (libsource (lib "eagle-import") (part "1X01"))
    )
    (comp (ref "JP522")
      (value "1X01")
      (footprint "eagle-import:1X01")
      (libsource (lib "eagle-import") (part "1X01"))
    )
    (comp (ref "JP523")
      (value "1X01")
      (footprint "eagle-import:1X01")
      (libsource (lib "eagle-import") (part "1X01"))
    )
    (comp (ref "JP524")
      (value "1X01")
      (footprint "eagle-import:1X01")
      (libsource (lib "eagle-import") (part "1X01"))
    )
    (comp (ref "JP525")
      (value "1X01")
      (footprint "eagle-import:1X01")
      (libsource (lib "eagle-import") (part "1X01"))
    )
    (comp (ref "JP526")
      (value "1X01")
      (footprint "eagle-import:1X01")
      (libsource (lib "eagle-import") (part "1X01"))
    )
    (comp (ref "JP527")
      (value "1X01")
      (footprint "eagle-import:1X01")
      (libsource (lib "eagle-import") (part "1X01"))
    )
    (comp (ref "JP528")
      (value "1X01")
      (footprint "eagle-import:1X01")
      (libsource (lib "eagle-import") (part "1X01"))
    )
    (comp (ref "JP529")
      (value "1X01")
      (footprint "eagle-import:1X01")
      (libsource (lib "eagle-import") (part "1X01"))
    )
    (comp (ref "JP530")
      (value "1X01")
      (footprint "eagle-import:1X01")
      (libsource (lib "eagle-import") (part "1X01"))
    )
    (comp (ref "JP531")
      (value "1X01")
      (footprint "eagle-import:1X01")
      (libsource (lib "eagle-import") (part "1X01"))
    )
    (comp (ref "JP532")
      (value "1X01")
      (footprint "eagle-import:1X01")
      (libsource (lib "eagle-import") (part "1X01"))
    )
    (comp (ref "JP533")
      (value "1X01")
      (footprint "eagle-import:1X01")
      (libsource (lib "eagle-import") (part "1X01"))
    )
    (comp (ref "JP534")
      (value "1X01")
      (footprint "eagle-import:1X01")
      (libsource (lib "eagle-import") (part "1X01"))
    )
    (comp (ref "JP535")
      (value "1X01")
      (footprint "eagle-import:1X01")
      (libsource (lib "eagle-import") (part "1X01"))
    )
    (comp (ref "JP536")
      (value "1X01")
      (footprint "eagle-import:1X01")
      (libsource (lib "eagle-import") (part "1X01"))
    )
    (comp (ref "JP537")
      (value "1X01")
      (footprint "eagle-import:1X01")
      (libsource (lib "eagle-import") (part "1X01"))
    )
    (comp (ref "JP538")
      (value "1X01")
      (footprint "eagle-import:1X01")
      (libsource (lib "eagle-import") (part "1X01"))
    )
    (comp (ref "JP539")
      (value "1X01")
      (footprint "eagle-import:1X01")
      (libsource (lib "eagle-import") (part "1X01"))
    )
    (comp (ref "JP540")
      (value "1X01")
      (footprint "eagle-import:1X01")
      (libsource (lib "eagle-import") (part "1X01"))
    )
    (comp (ref "JP541")
      (value "1X01")
      (footprint "eagle-import:1X01")
      (libsource (lib "eagle-import") (part "1X01"))
    )
    (comp (ref "JP542")
      (value "1X01")
      (footprint "eagle-import:1X01")
      (libsource (lib "eagle-import") (part "1X01"))
    )
    (comp (ref "JP543")
      (value "1X01")
      (footprint "eagle-import:1X01")
      (libsource (lib "eagle-import") (part "1X01"))
    )
    (comp (ref "JP544")
      (value "1X01")
      (footprint "eagle-import:1X01")
      (libsource (lib "eagle-import") (part "1X01"))
    )
    (comp (ref "JP545")
      (value "1X01")
      (footprint "eagle-import:1X01")
      (libsource (lib "eagle-import") (part "1X01"))
    )
    (comp (ref "JP546")
      (value "1X01")
      (footprint "eagle-import:1X01")
      (libsource (lib "eagle-import") (part "1X01"))
    )
    (comp (ref "JP547")
      (value "1X01")
      (footprint "eagle-import:1X01")
      (libsource (lib "eagle-import") (part "1X01"))
    )
    (comp (ref "JP548")
      (value "1X01")
      (footprint "eagle-import:1X01")
      (libsource (lib "eagle-import") (part "1X01"))
    )
    (comp (ref "JP549")
      (value "1X01")
      (footprint "eagle-import:1X01")
      (libsource (lib "eagle-import") (part "1X01"))
    )
    (comp (ref "JP550")
      (value "1X01")
      (footprint "eagle-import:1X01")
      (libsource (lib "eagle-import") (part "1X01"))
    )
    (comp (ref "JP551")
      (value "1X01")
      (footprint "eagle-import:1X01")
      (libsource (lib "eagle-import") (part "1X01"))
    )
    (comp (ref "JP552")
      (value "1X01")
      (footprint "eagle-import:1X01")
      (libsource (lib "eagle-import") (part "1X01"))
    )
    (comp (ref "JP553")
      (value "1X01")
      (footprint "eagle-import:1X01")
      (libsource (lib "eagle-import") (part "1X01"))
    )
    (comp (ref "JP554")
      (value "1X01")
      (footprint "eagle-import:1X01")
      (libsource (lib "eagle-import") (part "1X01"))
    )
    (comp (ref "JP555")
      (value "1X01")
      (footprint "eagle-import:1X01")
      (libsource (lib "eagle-import") (part "1X01"))
    )
    (comp (ref "JP556")
      (value "1X01")
      (footprint "eagle-import:1X01")
      (libsource (lib "eagle-import") (part "1X01"))
    )
    (comp (ref "JP557")
      (value "1X01")
      (footprint "eagle-import:1X01")
      (libsource (lib "eagle-import") (part "1X01"))
    )
    (comp (ref "JP558")
      (value "1X01")
      (footprint "eagle-import:1X01")
      (libsource (lib "eagle-import") (part "1X01"))
    )
    (comp (ref "JP559")
      (value "1X01")
      (footprint "eagle-import:1X01")
      (libsource (lib "eagle-import") (part "1X01"))
    )
    (comp (ref "JP560")
      (value "1X01")
      (footprint "eagle-import:1X01")
      (libsource (lib "eagle-import") (part "1X01"))
    )
    (comp (ref "JP561")
      (value "1X01")
      (footprint "eagle-import:1X01")
      (libsource (lib "eagle-import") (part "1X01"))
    )
    (comp (ref "JP562")
      (value "1X01")
      (footprint "eagle-import:1X01")
      (libsource (lib "eagle-import") (part "1X01"))
    )
    (comp (ref "JP563")
      (value "1X01")
      (footprint "eagle-import:1X01")
      (libsource (lib "eagle-import") (part "1X01"))
    )
    (comp (ref "JP564")
      (value "1X01")
      (footprint "eagle-import:1X01")
      (libsource (lib "eagle-import") (part "1X01"))
    )
    (comp (ref "JP565")
      (value "1X01")
      (footprint "eagle-import:1X01")
      (libsource (lib "eagle-import") (part "1X01"))
    )
    (comp (ref "JP566")
      (value "1X01")
      (footprint "eagle-import:1X01")
      (libsource (lib "eagle-import") (part "1X01"))
    )
    (comp (ref "JP567")
      (value "1X01")
      (footprint "eagle-import:1X01")
      (libsource (lib "eagle-import") (part "1X01"))
    )
    (comp (ref "JP568")
      (value "1X01")
      (footprint "eagle-import:1X01")
      (libsource (lib "eagle-import") (part "1X01"))
    )
    (comp (ref "JP569")
      (value "1X01")
      (footprint "eagle-import:1X01")
      (libsource (lib "eagle-import") (part "1X01"))
    )
    (comp (ref "JP570")
      (value "1X01")
      (footprint "eagle-import:1X01")
      (libsource (lib "eagle-import") (part "1X01"))
    )
    (comp (ref "JP571")
      (value "1X01")
      (footprint "eagle-import:1X01")
      (libsource (lib "eagle-import") (part "1X01"))
    )
    (comp (ref "JP572")
      (value "1X01")
      (footprint "eagle-import:1X01")
      (libsource (lib "eagle-import") (part "1X01"))
    )
    (comp (ref "JP573")
      (value "1X01")
      (footprint "eagle-import:1X01")
      (libsource (lib "eagle-import") (part "1X01"))
    )
    (comp (ref "JP574")
      (value "1X01")
      (footprint "eagle-import:1X01")
      (libsource (lib "eagle-import") (part "1X01"))
    )
    (comp (ref "JP575")
      (value "1X01")
      (footprint "eagle-import:1X01")
      (libsource (lib "eagle-import") (part "1X01"))
    )
    (comp (ref "JP576")
      (value "1X01")
      (footprint "eagle-import:1X01")
      (libsource (lib "eagle-import") (part "1X01"))
    )
    (comp (ref "JP577")
      (value "1X01")
      (footprint "eagle-import:1X01")
      (libsource (lib "eagle-import") (part "1X01"))
    )
    (comp (ref "JP578")
      (value "1X01")
      (footprint "eagle-import:1X01")
      (libsource (lib "eagle-import") (part "1X01"))
    )
    (comp (ref "JP579")
      (value "1X01")
      (footprint "eagle-import:1X01")
      (libsource (lib "eagle-import") (part "1X01"))
    )
    (comp (ref "JP580")
      (value "1X01")
      (footprint "eagle-import:1X01")
      (libsource (lib "eagle-import") (part "1X01"))
    )
    (comp (ref "JP581")
      (value "1X01")
      (footprint "eagle-import:1X01")
      (libsource (lib "eagle-import") (part "1X01"))
    )
    (comp (ref "JP582")
      (value "1X01")
      (footprint "eagle-import:1X01")
      (libsource (lib "eagle-import") (part "1X01"))
    )
    (comp (ref "JP583")
      (value "1X01")
      (footprint "eagle-import:1X01")
      (libsource (lib "eagle-import") (part "1X01"))
    )
    (comp (ref "JP584")
      (value "1X01")
      (footprint "eagle-import:1X01")
      (libsource (lib "eagle-import") (part "1X01"))
    )
    (comp (ref "JP585")
      (value "1X01")
      (footprint "eagle-import:1X01")
      (libsource (lib "eagle-import") (part "1X01"))
    )
    (comp (ref "JP586")
      (value "1X01")
      (footprint "eagle-import:1X01")
      (libsource (lib "eagle-import") (part "1X01"))
    )
    (comp (ref "JP587")
      (value "1X01")
      (footprint "eagle-import:1X01")
      (libsource (lib "eagle-import") (part "1X01"))
    )
    (comp (ref "JP588")
      (value "1X01")
      (footprint "eagle-import:1X01")
      (libsource (lib "eagle-import") (part "1X01"))
    )
    (comp (ref "JP589")
      (value "1X01")
      (footprint "eagle-import:1X01")
      (libsource (lib "eagle-import") (part "1X01"))
    )
    (comp (ref "JP590")
      (value "1X01")
      (footprint "eagle-import:1X01")
      (libsource (lib "eagle-import") (part "1X01"))
    )
    (comp (ref "JP591")
      (value "1X01")
      (footprint "eagle-import:1X01")
      (libsource (lib "eagle-import") (part "1X01"))
    )
    (comp (ref "JP592")
      (value "1X01")
      (footprint "eagle-import:1X01")
      (libsource (lib "eagle-import") (part "1X01"))
    )
    (comp (ref "JP593")
      (value "1X01")
      (footprint "eagle-import:1X01")
      (libsource (lib "eagle-import") (part "1X01"))
    )
    (comp (ref "JP594")
      (value "1X01")
      (footprint "eagle-import:1X01")
      (libsource (lib "eagle-import") (part "1X01"))
    )
    (comp (ref "JP595")
      (value "1X01")
      (footprint "eagle-import:1X01")
      (libsource (lib "eagle-import") (part "1X01"))
    )
    (comp (ref "JP596")
      (value "1X01")
      (footprint "eagle-import:1X01")
      (libsource (lib "eagle-import") (part "1X01"))
    )
    (comp (ref "JP597")
      (value "1X01")
      (footprint "eagle-import:1X01")
      (libsource (lib "eagle-import") (part "1X01"))
    )
    (comp (ref "JP598")
      (value "1X01")
      (footprint "eagle-import:1X01")
      (libsource (lib "eagle-import") (part "1X01"))
    )
    (comp (ref "JP599")
      (value "1X01")
      (footprint "eagle-import:1X01")
      (libsource (lib "eagle-import") (part "1X01"))
    )
    (comp (ref "JP600")
      (value "1X01")
      (footprint "eagle-import:1X01")
      (libsource (lib "eagle-import") (part "1X01"))
    )
    (comp (ref "JP601")
      (value "1X01")
      (footprint "eagle-import:1X01")
      (libsource (lib "eagle-import") (part "1X01"))
    )
    (comp (ref "JP602")
      (value "1X01")
      (footprint "eagle-import:1X01")
      (libsource (lib "eagle-import") (part "1X01"))
    )
    (comp (ref "JP603")
      (value "1X01")
      (footprint "eagle-import:1X01")
      (libsource (lib "eagle-import") (part "1X01"))
    )
    (comp (ref "JP604")
      (value "1X01")
      (footprint "eagle-import:1X01")
      (libsource (lib "eagle-import") (part "1X01"))
    )
    (comp (ref "JP605")
      (value "1X01")
      (footprint "eagle-import:1X01")
      (libsource (lib "eagle-import") (part "1X01"))
    )
    (comp (ref "JP606")
      (value "1X01")
      (footprint "eagle-import:1X01")
      (libsource (lib "eagle-import") (part "1X01"))
    )
    (comp (ref "JP607")
      (value "1X01")
      (footprint "eagle-import:1X01")
      (libsource (lib "eagle-import") (part "1X01"))
    )
    (comp (ref "JP608")
      (value "1X01")
      (footprint "eagle-import:1X01")
      (libsource (lib "eagle-import") (part "1X01"))
    )
    (comp (ref "JP609")
      (value "1X01")
      (footprint "eagle-import:1X01")
      (libsource (lib "eagle-import") (part "1X01"))
    )
    (comp (ref "JP610")
      (value "1X01")
      (footprint "eagle-import:1X01")
      (libsource (lib "eagle-import") (part "1X01"))
    )
    (comp (ref "JP611")
      (value "1X01")
      (footprint "eagle-import:1X01")
      (libsource (lib "eagle-import") (part "1X01"))
    )
    (comp (ref "JP612")
      (value "1X01")
      (footprint "eagle-import:1X01")
      (libsource (lib "eagle-import") (part "1X01"))
    )
    (comp (ref "JP613")
      (value "1X01")
      (footprint "eagle-import:1X01")
      (libsource (lib "eagle-import") (part "1X01"))
    )
    (comp (ref "JP614")
      (value "1X01")
      (footprint "eagle-import:1X01")
      (libsource (lib "eagle-import") (part "1X01"))
    )
    (comp (ref "JP615")
      (value "1X01")
      (footprint "eagle-import:1X01")
      (libsource (lib "eagle-import") (part "1X01"))
    )
    (comp (ref "JP616")
      (value "1X01")
      (footprint "eagle-import:1X01")
      (libsource (lib "eagle-import") (part "1X01"))
    )
    (comp (ref "JP617")
      (value "1X01")
      (footprint "eagle-import:1X01")
      (libsource (lib "eagle-import") (part "1X01"))
    )
    (comp (ref "JP618")
      (value "1X01")
      (footprint "eagle-import:1X01")
      (libsource (lib "eagle-import") (part "1X01"))
    )
    (comp (ref "JP619")
      (value "1X01")
      (footprint "eagle-import:1X01")
      (libsource (lib "eagle-import") (part "1X01"))
    )
    (comp (ref "JP620")
      (value "1X01")
      (footprint "eagle-import:1X01")
      (libsource (lib "eagle-import") (part "1X01"))
    )
    (comp (ref "JP621")
      (value "1X01")
      (footprint "eagle-import:1X01")
      (libsource (lib "eagle-import") (part "1X01"))
    )
    (comp (ref "JP622")
      (value "1X01")
      (footprint "eagle-import:1X01")
      (libsource (lib "eagle-import") (part "1X01"))
    )
    (comp (ref "JP623")
      (value "1X01")
      (footprint "eagle-import:1X01")
      (libsource (lib "eagle-import") (part "1X01"))
    )
    (comp (ref "JP624")
      (value "1X01")
      (footprint "eagle-import:1X01")
      (libsource (lib "eagle-import") (part "1X01"))
    )
    (comp (ref "JP625")
      (value "1X01")
      (footprint "eagle-import:1X01")
      (libsource (lib "eagle-import") (part "1X01"))
    )
    (comp (ref "JP626")
      (value "1X01")
      (footprint "eagle-import:1X01")
      (libsource (lib "eagle-import") (part "1X01"))
    )
    (comp (ref "JP627")
      (value "1X01")
      (footprint "eagle-import:1X01")
      (libsource (lib "eagle-import") (part "1X01"))
    )
    (comp (ref "JP628")
      (value "1X01")
      (footprint "eagle-import:1X01")
      (libsource (lib "eagle-import") (part "1X01"))
    )
    (comp (ref "JP629")
      (value "1X01")
      (footprint "eagle-import:1X01")
      (libsource (lib "eagle-import") (part "1X01"))
    )
    (comp (ref "JP630")
      (value "1X01")
      (footprint "eagle-import:1X01")
      (libsource (lib "eagle-import") (part "1X01"))
    )
    (comp (ref "JP631")
      (value "1X01")
      (footprint "eagle-import:1X01")
      (libsource (lib "eagle-import") (part "1X01"))
    )
    (comp (ref "JP632")
      (value "1X01")
      (footprint "eagle-import:1X01")
      (libsource (lib "eagle-import") (part "1X01"))
    )
    (comp (ref "JP633")
      (value "1X01")
      (footprint "eagle-import:1X01")
      (libsource (lib "eagle-import") (part "1X01"))
    )
    (comp (ref "JP634")
      (value "1X01")
      (footprint "eagle-import:1X01")
      (libsource (lib "eagle-import") (part "1X01"))
    )
    (comp (ref "JP635")
      (value "1X01")
      (footprint "eagle-import:1X01")
      (libsource (lib "eagle-import") (part "1X01"))
    )
    (comp (ref "JP636")
      (value "1X01")
      (footprint "eagle-import:1X01")
      (libsource (lib "eagle-import") (part "1X01"))
    )
    (comp (ref "JP637")
      (value "1X01")
      (footprint "eagle-import:1X01")
      (libsource (lib "eagle-import") (part "1X01"))
    )
    (comp (ref "JP638")
      (value "1X01")
      (footprint "eagle-import:1X01")
      (libsource (lib "eagle-import") (part "1X01"))
    )
    (comp (ref "JP639")
      (value "1X01")
      (footprint "eagle-import:1X01")
      (libsource (lib "eagle-import") (part "1X01"))
    )
    (comp (ref "JP640")
      (value "1X01")
      (footprint "eagle-import:1X01")
      (libsource (lib "eagle-import") (part "1X01"))
    )
    (comp (ref "JP641")
      (value "1X01")
      (footprint "eagle-import:1X01")
      (libsource (lib "eagle-import") (part "1X01"))
    )
    (comp (ref "JP642")
      (value "1X01")
      (footprint "eagle-import:1X01")
      (libsource (lib "eagle-import") (part "1X01"))
    )
    (comp (ref "JP643")
      (value "1X01")
      (footprint "eagle-import:1X01")
      (libsource (lib "eagle-import") (part "1X01"))
    )
    (comp (ref "JP644")
      (value "1X01")
      (footprint "eagle-import:1X01")
      (libsource (lib "eagle-import") (part "1X01"))
    )
    (comp (ref "JP645")
      (value "1X01")
      (footprint "eagle-import:1X01")
      (libsource (lib "eagle-import") (part "1X01"))
    )
    (comp (ref "JP646")
      (value "1X01")
      (footprint "eagle-import:1X01")
      (libsource (lib "eagle-import") (part "1X01"))
    )
    (comp (ref "JP647")
      (value "1X01")
      (footprint "eagle-import:1X01")
      (libsource (lib "eagle-import") (part "1X01"))
    )
    (comp (ref "JP648")
      (value "1X01")
      (footprint "eagle-import:1X01")
      (libsource (lib "eagle-import") (part "1X01"))
    )
    (comp (ref "JP649")
      (value "1X01")
      (footprint "eagle-import:1X01")
      (libsource (lib "eagle-import") (part "1X01"))
    )
    (comp (ref "JP650")
      (value "1X01")
      (footprint "eagle-import:1X01")
      (libsource (lib "eagle-import") (part "1X01"))
    )
    (comp (ref "JP651")
      (value "1X01")
      (footprint "eagle-import:1X01")
      (libsource (lib "eagle-import") (part "1X01"))
    )
    (comp (ref "JP652")
      (value "1X01")
      (footprint "eagle-import:1X01")
      (libsource (lib "eagle-import") (part "1X01"))
    )
    (comp (ref "JP653")
      (value "1X01")
      (footprint "eagle-import:1X01")
      (libsource (lib "eagle-import") (part "1X01"))
    )
    (comp (ref "JP654")
      (value "1X01")
      (footprint "eagle-import:1X01")
      (libsource (lib "eagle-import") (part "1X01"))
    )
    (comp (ref "JP655")
      (value "1X01")
      (footprint "eagle-import:1X01")
      (libsource (lib "eagle-import") (part "1X01"))
    )
    (comp (ref "JP656")
      (value "1X01")
      (footprint "eagle-import:1X01")
      (libsource (lib "eagle-import") (part "1X01"))
    )
    (comp (ref "JP657")
      (value "1X01")
      (footprint "eagle-import:1X01")
      (libsource (lib "eagle-import") (part "1X01"))
    )
    (comp (ref "JP658")
      (value "1X01")
      (footprint "eagle-import:1X01")
      (libsource (lib "eagle-import") (part "1X01"))
    )
    (comp (ref "JP659")
      (value "1X01")
      (footprint "eagle-import:1X01")
      (libsource (lib "eagle-import") (part "1X01"))
    )
    (comp (ref "JP660")
      (value "1X01")
      (footprint "eagle-import:1X01")
      (libsource (lib "eagle-import") (part "1X01"))
    )
    (comp (ref "JP661")
      (value "1X01")
      (footprint "eagle-import:1X01")
      (libsource (lib "eagle-import") (part "1X01"))
    )
    (comp (ref "JP662")
      (value "1X01")
      (footprint "eagle-import:1X01")
      (libsource (lib "eagle-import") (part "1X01"))
    )
    (comp (ref "JP663")
      (value "1X01")
      (footprint "eagle-import:1X01")
      (libsource (lib "eagle-import") (part "1X01"))
    )
    (comp (ref "JP664")
      (value "1X01")
      (footprint "eagle-import:1X01")
      (libsource (lib "eagle-import") (part "1X01"))
    )
    (comp (ref "JP665")
      (value "1X01")
      (footprint "eagle-import:1X01")
      (libsource (lib "eagle-import") (part "1X01"))
    )
    (comp (ref "JP666")
      (value "1X01")
      (footprint "eagle-import:1X01")
      (libsource (lib "eagle-import") (part "1X01"))
    )
    (comp (ref "JP667")
      (value "1X01")
      (footprint "eagle-import:1X01")
      (libsource (lib "eagle-import") (part "1X01"))
    )
    (comp (ref "JP668")
      (value "1X01")
      (footprint "eagle-import:1X01")
      (libsource (lib "eagle-import") (part "1X01"))
    )
    (comp (ref "JP669")
      (value "1X01")
      (footprint "eagle-import:1X01")
      (libsource (lib "eagle-import") (part "1X01"))
    )
    (comp (ref "JP670")
      (value "1X01")
      (footprint "eagle-import:1X01")
      (libsource (lib "eagle-import") (part "1X01"))
    )
    (comp (ref "JP671")
      (value "1X01")
      (footprint "eagle-import:1X01")
      (libsource (lib "eagle-import") (part "1X01"))
    )
    (comp (ref "JP672")
      (value "1X01")
      (footprint "eagle-import:1X01")
      (libsource (lib "eagle-import") (part "1X01"))
    )
    (comp (ref "JP673")
      (value "1X01")
      (footprint "eagle-import:1X01")
      (libsource (lib "eagle-import") (part "1X01"))
    )
    (comp (ref "JP674")
      (value "1X01")
      (footprint "eagle-import:1X01")
      (libsource (lib "eagle-import") (part "1X01"))
    )
    (comp (ref "JP675")
      (value "1X01")
      (footprint "eagle-import:1X01")
      (libsource (lib "eagle-import") (part "1X01"))
    )
    (comp (ref "JP676")
      (value "1X01")
      (footprint "eagle-import:1X01")
      (libsource (lib "eagle-import") (part "1X01"))
    )
    (comp (ref "JP677")
      (value "1X01")
      (footprint "eagle-import:1X01")
      (libsource (lib "eagle-import") (part "1X01"))
    )
    (comp (ref "JP678")
      (value "1X01")
      (footprint "eagle-import:1X01")
      (libsource (lib "eagle-import") (part "1X01"))
    )
    (comp (ref "JP679")
      (value "1X01")
      (footprint "eagle-import:1X01")
      (libsource (lib "eagle-import") (part "1X01"))
    )
    (comp (ref "JP680")
      (value "1X01")
      (footprint "eagle-import:1X01")
      (libsource (lib "eagle-import") (part "1X01"))
    )
    (comp (ref "JP681")
      (value "1X01")
      (footprint "eagle-import:1X01")
      (libsource (lib "eagle-import") (part "1X01"))
    )
    (comp (ref "JP682")
      (value "1X01")
      (footprint "eagle-import:1X01")
      (libsource (lib "eagle-import") (part "1X01"))
    )
    (comp (ref "JP683")
      (value "1X01")
      (footprint "eagle-import:1X01")
      (libsource (lib "eagle-import") (part "1X01"))
    )
    (comp (ref "JP684")
      (value "1X01")
      (footprint "eagle-import:1X01")
      (libsource (lib "eagle-import") (part "1X01"))
    )
    (comp (ref "JP685")
      (value "1X01")
      (footprint "eagle-import:1X01")
      (libsource (lib "eagle-import") (part "1X01"))
    )
    (comp (ref "JP686")
      (value "1X01")
      (footprint "eagle-import:1X01")
      (libsource (lib "eagle-import") (part "1X01"))
    )
    (comp (ref "JP687")
      (value "1X01")
      (footprint "eagle-import:1X01")
      (libsource (lib "eagle-import") (part "1X01"))
    )
    (comp (ref "JP688")
      (value "1X01")
      (footprint "eagle-import:1X01")
      (libsource (lib "eagle-import") (part "1X01"))
    )
    (comp (ref "JP689")
      (value "1X01")
      (footprint "eagle-import:1X01")
      (libsource (lib "eagle-import") (part "1X01"))
    )
    (comp (ref "JP690")
      (value "1X01")
      (footprint "eagle-import:1X01")
      (libsource (lib "eagle-import") (part "1X01"))
    )
    (comp (ref "JP691")
      (value "1X01")
      (footprint "eagle-import:1X01")
      (libsource (lib "eagle-import") (part "1X01"))
    )
    (comp (ref "JP692")
      (value "1X01")
      (footprint "eagle-import:1X01")
      (libsource (lib "eagle-import") (part "1X01"))
    )
    (comp (ref "JP693")
      (value "1X01")
      (footprint "eagle-import:1X01")
      (libsource (lib "eagle-import") (part "1X01"))
    )
    (comp (ref "JP694")
      (value "1X01")
      (footprint "eagle-import:1X01")
      (libsource (lib "eagle-import") (part "1X01"))
    )
    (comp (ref "JP695")
      (value "1X01")
      (footprint "eagle-import:1X01")
      (libsource (lib "eagle-import") (part "1X01"))
    )
    (comp (ref "JP696")
      (value "1X01")
      (footprint "eagle-import:1X01")
      (libsource (lib "eagle-import") (part "1X01"))
    )
    (comp (ref "JP697")
      (value "1X01")
      (footprint "eagle-import:1X01")
      (libsource (lib "eagle-import") (part "1X01"))
    )
    (comp (ref "JP698")
      (value "1X01")
      (footprint "eagle-import:1X01")
      (libsource (lib "eagle-import") (part "1X01"))
    )
    (comp (ref "JP699")
      (value "1X01")
      (footprint "eagle-import:1X01")
      (libsource (lib "eagle-import") (part "1X01"))
    )
    (comp (ref "JP700")
      (value "1X01")
      (footprint "eagle-import:1X01")
      (libsource (lib "eagle-import") (part "1X01"))
    )
    (comp (ref "JP701")
      (value "1X01")
      (footprint "eagle-import:1X01")
      (libsource (lib "eagle-import") (part "1X01"))
    )
    (comp (ref "JP702")
      (value "1X01")
      (footprint "eagle-import:1X01")
      (libsource (lib "eagle-import") (part "1X01"))
    )
    (comp (ref "JP703")
      (value "1X01")
      (footprint "eagle-import:1X01")
      (libsource (lib "eagle-import") (part "1X01"))
    )
    (comp (ref "JP704")
      (value "1X01")
      (footprint "eagle-import:1X01")
      (libsource (lib "eagle-import") (part "1X01"))
    )
    (comp (ref "JP705")
      (value "1X01")
      (footprint "eagle-import:1X01")
      (libsource (lib "eagle-import") (part "1X01"))
    )
    (comp (ref "JP706")
      (value "1X01")
      (footprint "eagle-import:1X01")
      (libsource (lib "eagle-import") (part "1X01"))
    )
    (comp (ref "JP707")
      (value "1X01")
      (footprint "eagle-import:1X01")
      (libsource (lib "eagle-import") (part "1X01"))
    )
    (comp (ref "JP708")
      (value "1X01")
      (footprint "eagle-import:1X01")
      (libsource (lib "eagle-import") (part "1X01"))
    )
    (comp (ref "JP709")
      (value "1X01")
      (footprint "eagle-import:1X01")
      (libsource (lib "eagle-import") (part "1X01"))
    )
    (comp (ref "JP710")
      (value "1X01")
      (footprint "eagle-import:1X01")
      (libsource (lib "eagle-import") (part "1X01"))
    )
    (comp (ref "JP711")
      (value "1X01")
      (footprint "eagle-import:1X01")
      (libsource (lib "eagle-import") (part "1X01"))
    )
    (comp (ref "JP712")
      (value "1X01")
      (footprint "eagle-import:1X01")
      (libsource (lib "eagle-import") (part "1X01"))
    )
    (comp (ref "JP713")
      (value "1X01")
      (footprint "eagle-import:1X01")
      (libsource (lib "eagle-import") (part "1X01"))
    )
    (comp (ref "JP714")
      (value "1X01")
      (footprint "eagle-import:1X01")
      (libsource (lib "eagle-import") (part "1X01"))
    )
    (comp (ref "JP715")
      (value "1X01")
      (footprint "eagle-import:1X01")
      (libsource (lib "eagle-import") (part "1X01"))
    )
    (comp (ref "JP716")
      (value "1X01")
      (footprint "eagle-import:1X01")
      (libsource (lib "eagle-import") (part "1X01"))
    )
    (comp (ref "JP717")
      (value "1X01")
      (footprint "eagle-import:1X01")
      (libsource (lib "eagle-import") (part "1X01"))
    )
    (comp (ref "JP718")
      (value "1X01")
      (footprint "eagle-import:1X01")
      (libsource (lib "eagle-import") (part "1X01"))
    )
    (comp (ref "JP719")
      (value "1X01")
      (footprint "eagle-import:1X01")
      (libsource (lib "eagle-import") (part "1X01"))
    )
    (comp (ref "JP720")
      (value "1X01")
      (footprint "eagle-import:1X01")
      (libsource (lib "eagle-import") (part "1X01"))
    )
    (comp (ref "JP721")
      (value "1X01")
      (footprint "eagle-import:1X01")
      (libsource (lib "eagle-import") (part "1X01"))
    )
    (comp (ref "JP722")
      (value "1X01")
      (footprint "eagle-import:1X01")
      (libsource (lib "eagle-import") (part "1X01"))
    )
    (comp (ref "JP723")
      (value "1X01")
      (footprint "eagle-import:1X01")
      (libsource (lib "eagle-import") (part "1X01"))
    )
    (comp (ref "JP724")
      (value "1X01")
      (footprint "eagle-import:1X01")
      (libsource (lib "eagle-import") (part "1X01"))
    )
    (comp (ref "JP725")
      (value "1X01")
      (footprint "eagle-import:1X01")
      (libsource (lib "eagle-import") (part "1X01"))
    )
    (comp (ref "JP726")
      (value "1X01")
      (footprint "eagle-import:1X01")
      (libsource (lib "eagle-import") (part "1X01"))
    )
    (comp (ref "JP727")
      (value "1X01")
      (footprint "eagle-import:1X01")
      (libsource (lib "eagle-import") (part "1X01"))
    )
    (comp (ref "JP728")
      (value "1X01")
      (footprint "eagle-import:1X01")
      (libsource (lib "eagle-import") (part "1X01"))
    )
    (comp (ref "JP729")
      (value "1X01")
      (footprint "eagle-import:1X01")
      (libsource (lib "eagle-import") (part "1X01"))
    )
    (comp (ref "JP730")
      (value "1X01")
      (footprint "eagle-import:1X01")
      (libsource (lib "eagle-import") (part "1X01"))
    )
    (comp (ref "JP731")
      (value "1X01")
      (footprint "eagle-import:1X01")
      (libsource (lib "eagle-import") (part "1X01"))
    )
    (comp (ref "JP732")
      (value "1X01")
      (footprint "eagle-import:1X01")
      (libsource (lib "eagle-import") (part "1X01"))
    )
    (comp (ref "JP733")
      (value "1X01")
      (footprint "eagle-import:1X01")
      (libsource (lib "eagle-import") (part "1X01"))
    )
    (comp (ref "JP734")
      (value "1X01")
      (footprint "eagle-import:1X01")
      (libsource (lib "eagle-import") (part "1X01"))
    )
    (comp (ref "JP735")
      (value "1X01")
      (footprint "eagle-import:1X01")
      (libsource (lib "eagle-import") (part "1X01"))
    )
    (comp (ref "JP736")
      (value "1X01")
      (footprint "eagle-import:1X01")
      (libsource (lib "eagle-import") (part "1X01"))
    )
    (comp (ref "JP737")
      (value "1X01")
      (footprint "eagle-import:1X01")
      (libsource (lib "eagle-import") (part "1X01"))
    )
    (comp (ref "JP738")
      (value "1X01")
      (footprint "eagle-import:1X01")
      (libsource (lib "eagle-import") (part "1X01"))
    )
    (comp (ref "JP739")
      (value "1X01")
      (footprint "eagle-import:1X01")
      (libsource (lib "eagle-import") (part "1X01"))
    )
    (comp (ref "JP740")
      (value "1X01")
      (footprint "eagle-import:1X01")
      (libsource (lib "eagle-import") (part "1X01"))
    )
    (comp (ref "JP741")
      (value "1X01")
      (footprint "eagle-import:1X01")
      (libsource (lib "eagle-import") (part "1X01"))
    )
    (comp (ref "JP742")
      (value "1X01")
      (footprint "eagle-import:1X01")
      (libsource (lib "eagle-import") (part "1X01"))
    )
    (comp (ref "JP743")
      (value "1X01")
      (footprint "eagle-import:1X01")
      (libsource (lib "eagle-import") (part "1X01"))
    )
    (comp (ref "JP744")
      (value "1X01")
      (footprint "eagle-import:1X01")
      (libsource (lib "eagle-import") (part "1X01"))
    )
    (comp (ref "JP745")
      (value "1X01")
      (footprint "eagle-import:1X01")
      (libsource (lib "eagle-import") (part "1X01"))
    )
    (comp (ref "JP746")
      (value "1X01")
      (footprint "eagle-import:1X01")
      (libsource (lib "eagle-import") (part "1X01"))
    )
    (comp (ref "JP747")
      (value "1X01")
      (footprint "eagle-import:1X01")
      (libsource (lib "eagle-import") (part "1X01"))
    )
    (comp (ref "JP748")
      (value "1X01")
      (footprint "eagle-import:1X01")
      (libsource (lib "eagle-import") (part "1X01"))
    )
    (comp (ref "JP749")
      (value "1X01")
      (footprint "eagle-import:1X01")
      (libsource (lib "eagle-import") (part "1X01"))
    )
    (comp (ref "JP750")
      (value "1X01")
      (footprint "eagle-import:1X01")
      (libsource (lib "eagle-import") (part "1X01"))
    )
    (comp (ref "JP751")
      (value "1X01")
      (footprint "eagle-import:1X01")
      (libsource (lib "eagle-import") (part "1X01"))
    )
    (comp (ref "JP752")
      (value "1X01")
      (footprint "eagle-import:1X01")
      (libsource (lib "eagle-import") (part "1X01"))
    )
    (comp (ref "JP753")
      (value "1X01")
      (footprint "eagle-import:1X01")
      (libsource (lib "eagle-import") (part "1X01"))
    )
    (comp (ref "JP754")
      (value "1X01")
      (footprint "eagle-import:1X01")
      (libsource (lib "eagle-import") (part "1X01"))
    )
    (comp (ref "JP755")
      (value "1X01")
      (footprint "eagle-import:1X01")
      (libsource (lib "eagle-import") (part "1X01"))
    )
    (comp (ref "JP756")
      (value "1X01")
      (footprint "eagle-import:1X01")
      (libsource (lib "eagle-import") (part "1X01"))
    )
    (comp (ref "JP757")
      (value "1X01")
      (footprint "eagle-import:1X01")
      (libsource (lib "eagle-import") (part "1X01"))
    )
    (comp (ref "JP758")
      (value "1X01")
      (footprint "eagle-import:1X01")
      (libsource (lib "eagle-import") (part "1X01"))
    )
    (comp (ref "JP759")
      (value "1X01")
      (footprint "eagle-import:1X01")
      (libsource (lib "eagle-import") (part "1X01"))
    )
    (comp (ref "JP760")
      (value "1X01")
      (footprint "eagle-import:1X01")
      (libsource (lib "eagle-import") (part "1X01"))
    )
    (comp (ref "JP761")
      (value "1X01")
      (footprint "eagle-import:1X01")
      (libsource (lib "eagle-import") (part "1X01"))
    )
    (comp (ref "JP762")
      (value "1X01")
      (footprint "eagle-import:1X01")
      (libsource (lib "eagle-import") (part "1X01"))
    )
    (comp (ref "JP763")
      (value "1X01")
      (footprint "eagle-import:1X01")
      (libsource (lib "eagle-import") (part "1X01"))
    )
    (comp (ref "JP764")
      (value "1X01")
      (footprint "eagle-import:1X01")
      (libsource (lib "eagle-import") (part "1X01"))
    )
    (comp (ref "JP765")
      (value "1X01")
      (footprint "eagle-import:1X01")
      (libsource (lib "eagle-import") (part "1X01"))
    )
    (comp (ref "JP766")
      (value "1X01")
      (footprint "eagle-import:1X01")
      (libsource (lib "eagle-import") (part "1X01"))
    )
    (comp (ref "JP767")
      (value "1X01")
      (footprint "eagle-import:1X01")
      (libsource (lib "eagle-import") (part "1X01"))
    )
    (comp (ref "JP768")
      (value "1X01")
      (footprint "eagle-import:1X01")
      (libsource (lib "eagle-import") (part "1X01"))
    )
    (comp (ref "JP769")
      (value "1X01")
      (footprint "eagle-import:1X01")
      (libsource (lib "eagle-import") (part "1X01"))
    )
    (comp (ref "JP770")
      (value "1X01")
      (footprint "eagle-import:1X01")
      (libsource (lib "eagle-import") (part "1X01"))
    )
    (comp (ref "JP771")
      (value "1X01")
      (footprint "eagle-import:1X01")
      (libsource (lib "eagle-import") (part "1X01"))
    )
    (comp (ref "JP772")
      (value "1X01")
      (footprint "eagle-import:1X01")
      (libsource (lib "eagle-import") (part "1X01"))
    )
    (comp (ref "JP773")
      (value "1X01")
      (footprint "eagle-import:1X01")
      (libsource (lib "eagle-import") (part "1X01"))
    )
    (comp (ref "JP774")
      (value "1X01")
      (footprint "eagle-import:1X01")
      (libsource (lib "eagle-import") (part "1X01"))
    )
    (comp (ref "JP775")
      (value "1X01")
      (footprint "eagle-import:1X01")
      (libsource (lib "eagle-import") (part "1X01"))
    )
    (comp (ref "JP776")
      (value "1X01")
      (footprint "eagle-import:1X01")
      (libsource (lib "eagle-import") (part "1X01"))
    )
    (comp (ref "JP777")
      (value "1X01")
      (footprint "eagle-import:1X01")
      (libsource (lib "eagle-import") (part "1X01"))
    )
    (comp (ref "JP778")
      (value "1X01")
      (footprint "eagle-import:1X01")
      (libsource (lib "eagle-import") (part "1X01"))
    )
    (comp (ref "JP779")
      (value "1X01")
      (footprint "eagle-import:1X01")
      (libsource (lib "eagle-import") (part "1X01"))
    )
    (comp (ref "JP780")
      (value "1X01")
      (footprint "eagle-import:1X01")
      (libsource (lib "eagle-import") (part "1X01"))
    )
    (comp (ref "JP781")
      (value "1X01")
      (footprint "eagle-import:1X01")
      (libsource (lib "eagle-import") (part "1X01"))
    )
    (comp (ref "JP782")
      (value "1X01")
      (footprint "eagle-import:1X01")
      (libsource (lib "eagle-import") (part "1X01"))
    )
    (comp (ref "JP783")
      (value "1X01")
      (footprint "eagle-import:1X01")
      (libsource (lib "eagle-import") (part "1X01"))
    )
    (comp (ref "JP784")
      (value "1X01")
      (footprint "eagle-import:1X01")
      (libsource (lib "eagle-import") (part "1X01"))
    )
    (comp (ref "JP785")
      (value "1X01")
      (footprint "eagle-import:1X01")
      (libsource (lib "eagle-import") (part "1X01"))
    )
    (comp (ref "JP786")
      (value "1X01")
      (footprint "eagle-import:1X01")
      (libsource (lib "eagle-import") (part "1X01"))
    )
    (comp (ref "JP787")
      (value "1X01")
      (footprint "eagle-import:1X01")
      (libsource (lib "eagle-import") (part "1X01"))
    )
    (comp (ref "JP788")
      (value "1X01-WIDE")
      (footprint "eagle-import:1X01-WIDE")
      (libsource (lib "eagle-import") (part "1X01-WIDE"))
    )
    (comp (ref "JP789")
      (value "1X01-WIDE")
      (footprint "eagle-import:1X01-WIDE")
      (libsource (lib "eagle-import") (part "1X01-WIDE"))
    )
    (comp (ref "JP790")
      (value "1X01-WIDE")
      (footprint "eagle-import:1X01-WIDE")
      (libsource (lib "eagle-import") (part "1X01-WIDE"))
    )
    (comp (ref "JP791")
      (value "1X01")
      (footprint "eagle-import:1X01")
      (libsource (lib "eagle-import") (part "1X01"))
    )
    (comp (ref "JP792")
      (value "1X01")
      (footprint "eagle-import:1X01")
      (libsource (lib "eagle-import") (part "1X01"))
    )
    (comp (ref "JP793")
      (value "1X01")
      (footprint "eagle-import:1X01")
      (libsource (lib "eagle-import") (part "1X01"))
    )
    (comp (ref "JP794")
      (value "1X01")
      (footprint "eagle-import:1X01")
      (libsource (lib "eagle-import") (part "1X01"))
    )
    (comp (ref "JP795")
      (value "1X01")
      (footprint "eagle-import:1X01")
      (libsource (lib "eagle-import") (part "1X01"))
    )
    (comp (ref "JP796")
      (value "1X01")
      (footprint "eagle-import:1X01")
      (libsource (lib "eagle-import") (part "1X01"))
    )
    (comp (ref "JP797")
      (value "1X01")
      (footprint "eagle-import:1X01")
      (libsource (lib "eagle-import") (part "1X01"))
    )
    (comp (ref "JP798")
      (value "1X01")
      (footprint "eagle-import:1X01")
      (libsource (lib "eagle-import") (part "1X01"))
    )
    (comp (ref "JP799")
      (value "1X01")
      (footprint "eagle-import:1X01")
      (libsource (lib "eagle-import") (part "1X01"))
    )
    (comp (ref "JP800")
      (value "1X01")
      (footprint "eagle-import:1X01")
      (libsource (lib "eagle-import") (part "1X01"))
    )
    (comp (ref "JP801")
      (value "1X01")
      (footprint "eagle-import:1X01")
      (libsource (lib "eagle-import") (part "1X01"))
    )
    (comp (ref "JP802")
      (value "1X01")
      (footprint "eagle-import:1X01")
      (libsource (lib "eagle-import") (part "1X01"))
    )
    (comp (ref "JP803")
      (value "1X01")
      (footprint "eagle-import:1X01")
      (libsource (lib "eagle-import") (part "1X01"))
    )
    (comp (ref "JP804")
      (value "1X01")
      (footprint "eagle-import:1X01")
      (libsource (lib "eagle-import") (part "1X01"))
    )
    (comp (ref "JP805")
      (value "1X01")
      (footprint "eagle-import:1X01")
      (libsource (lib "eagle-import") (part "1X01"))
    )
    (comp (ref "JP806")
      (value "1X01")
      (footprint "eagle-import:1X01")
      (libsource (lib "eagle-import") (part "1X01"))
    )
    (comp (ref "JP807")
      (value "1X01")
      (footprint "eagle-import:1X01")
      (libsource (lib "eagle-import") (part "1X01"))
    )
    (comp (ref "JP808")
      (value "1X01")
      (footprint "eagle-import:1X01")
      (libsource (lib "eagle-import") (part "1X01"))
    )
    (comp (ref "JP809")
      (value "1X01")
      (footprint "eagle-import:1X01")
      (libsource (lib "eagle-import") (part "1X01"))
    )
    (comp (ref "JP810")
      (value "1X01")
      (footprint "eagle-import:1X01")
      (libsource (lib "eagle-import") (part "1X01"))
    )
    (comp (ref "JP811")
      (value "1X01")
      (footprint "eagle-import:1X01")
      (libsource (lib "eagle-import") (part "1X01"))
    )
    (comp (ref "JP812")
      (value "1X01")
      (footprint "eagle-import:1X01")
      (libsource (lib "eagle-import") (part "1X01"))
    )
    (comp (ref "JP813")
      (value "1X01")
      (footprint "eagle-import:1X01")
      (libsource (lib "eagle-import") (part "1X01"))
    )
    (comp (ref "JP814")
      (value "1X01")
      (footprint "eagle-import:1X01")
      (libsource (lib "eagle-import") (part "1X01"))
    )
    (comp (ref "JP815")
      (value "1X01")
      (footprint "eagle-import:1X01")
      (libsource (lib "eagle-import") (part "1X01"))
    )
    (comp (ref "JP816")
      (value "1X01")
      (footprint "eagle-import:1X01")
      (libsource (lib "eagle-import") (part "1X01"))
    )
    (comp (ref "JP817")
      (value "1X01")
      (footprint "eagle-import:1X01")
      (libsource (lib "eagle-import") (part "1X01"))
    )
    (comp (ref "JP818")
      (value "1X01")
      (footprint "eagle-import:1X01")
      (libsource (lib "eagle-import") (part "1X01"))
    )
    (comp (ref "JP819")
      (value "1X01")
      (footprint "eagle-import:1X01")
      (libsource (lib "eagle-import") (part "1X01"))
    )
    (comp (ref "JP820")
      (value "1X01")
      (footprint "eagle-import:1X01")
      (libsource (lib "eagle-import") (part "1X01"))
    )
    (comp (ref "JP821")
      (value "1X01")
      (footprint "eagle-import:1X01")
      (libsource (lib "eagle-import") (part "1X01"))
    )
    (comp (ref "JP822")
      (value "1X01")
      (footprint "eagle-import:1X01")
      (libsource (lib "eagle-import") (part "1X01"))
    )
    (comp (ref "JP823")
      (value "1X01")
      (footprint "eagle-import:1X01")
      (libsource (lib "eagle-import") (part "1X01"))
    )
    (comp (ref "JP824")
      (value "1X01")
      (footprint "eagle-import:1X01")
      (libsource (lib "eagle-import") (part "1X01"))
    )
    (comp (ref "JP825")
      (value "1X01")
      (footprint "eagle-import:1X01")
      (libsource (lib "eagle-import") (part "1X01"))
    )
    (comp (ref "JP826")
      (value "1X01")
      (footprint "eagle-import:1X01")
      (libsource (lib "eagle-import") (part "1X01"))
    )
    (comp (ref "JP827")
      (value "1X01")
      (footprint "eagle-import:1X01")
      (libsource (lib "eagle-import") (part "1X01"))
    )
    (comp (ref "JP828")
      (value "1X01")
      (footprint "eagle-import:1X01")
      (libsource (lib "eagle-import") (part "1X01"))
    )
    (comp (ref "JP829")
      (value "1X01")
      (footprint "eagle-import:1X01")
      (libsource (lib "eagle-import") (part "1X01"))
    )
    (comp (ref "JP830")
      (value "1X01")
      (footprint "eagle-import:1X01")
      (libsource (lib "eagle-import") (part "1X01"))
    )
    (comp (ref "JP831")
      (value "1X01")
      (footprint "eagle-import:1X01")
      (libsource (lib "eagle-import") (part "1X01"))
    )
    (comp (ref "JP832")
      (value "1X01")
      (footprint "eagle-import:1X01")
      (libsource (lib "eagle-import") (part "1X01"))
    )
    (comp (ref "JP833")
      (value "1X01")
      (footprint "eagle-import:1X01")
      (libsource (lib "eagle-import") (part "1X01"))
    )
    (comp (ref "JP834")
      (value "1X01")
      (footprint "eagle-import:1X01")
      (libsource (lib "eagle-import") (part "1X01"))
    )
    (comp (ref "JP835")
      (value "1X01")
      (footprint "eagle-import:1X01")
      (libsource (lib "eagle-import") (part "1X01"))
    )
    (comp (ref "JP836")
      (value "1X01")
      (footprint "eagle-import:1X01")
      (libsource (lib "eagle-import") (part "1X01"))
    )
    (comp (ref "JP837")
      (value "1X01")
      (footprint "eagle-import:1X01")
      (libsource (lib "eagle-import") (part "1X01"))
    )
    (comp (ref "JP838")
      (value "1X01")
      (footprint "eagle-import:1X01")
      (libsource (lib "eagle-import") (part "1X01"))
    )
    (comp (ref "JP839")
      (value "1X01")
      (footprint "eagle-import:1X01")
      (libsource (lib "eagle-import") (part "1X01"))
    )
    (comp (ref "JP840")
      (value "1X01")
      (footprint "eagle-import:1X01")
      (libsource (lib "eagle-import") (part "1X01"))
    )
    (comp (ref "JP841")
      (value "1X01")
      (footprint "eagle-import:1X01")
      (libsource (lib "eagle-import") (part "1X01"))
    )
    (comp (ref "JP842")
      (value "1X01")
      (footprint "eagle-import:1X01")
      (libsource (lib "eagle-import") (part "1X01"))
    )
    (comp (ref "JP843")
      (value "1X01")
      (footprint "eagle-import:1X01")
      (libsource (lib "eagle-import") (part "1X01"))
    )
    (comp (ref "JP844")
      (value "1X01")
      (footprint "eagle-import:1X01")
      (libsource (lib "eagle-import") (part "1X01"))
    )
    (comp (ref "JP845")
      (value "1X01")
      (footprint "eagle-import:1X01")
      (libsource (lib "eagle-import") (part "1X01"))
    )
    (comp (ref "JP846")
      (value "1X01")
      (footprint "eagle-import:1X01")
      (libsource (lib "eagle-import") (part "1X01"))
    )
    (comp (ref "JP847")
      (value "1X01")
      (footprint "eagle-import:1X01")
      (libsource (lib "eagle-import") (part "1X01"))
    )
    (comp (ref "JP848")
      (value "1X01")
      (footprint "eagle-import:1X01")
      (libsource (lib "eagle-import") (part "1X01"))
    )
    (comp (ref "JP849")
      (value "1X01")
      (footprint "eagle-import:1X01")
      (libsource (lib "eagle-import") (part "1X01"))
    )
    (comp (ref "JP850")
      (value "1X01")
      (footprint "eagle-import:1X01")
      (libsource (lib "eagle-import") (part "1X01"))
    )
    (comp (ref "JP851")
      (value "1X01")
      (footprint "eagle-import:1X01")
      (libsource (lib "eagle-import") (part "1X01"))
    )
    (comp (ref "JP852")
      (value "1X01")
      (footprint "eagle-import:1X01")
      (libsource (lib "eagle-import") (part "1X01"))
    )
    (comp (ref "JP853")
      (value "1X01")
      (footprint "eagle-import:1X01")
      (libsource (lib "eagle-import") (part "1X01"))
    )
    (comp (ref "JP854")
      (value "1X01")
      (footprint "eagle-import:1X01")
      (libsource (lib "eagle-import") (part "1X01"))
    )
    (comp (ref "JP855")
      (value "1X01")
      (footprint "eagle-import:1X01")
      (libsource (lib "eagle-import") (part "1X01"))
    )
    (comp (ref "JP856")
      (value "1X01")
      (footprint "eagle-import:1X01")
      (libsource (lib "eagle-import") (part "1X01"))
    )
    (comp (ref "JP857")
      (value "1X01")
      (footprint "eagle-import:1X01")
      (libsource (lib "eagle-import") (part "1X01"))
    )
    (comp (ref "JP858")
      (value "1X01")
      (footprint "eagle-import:1X01")
      (libsource (lib "eagle-import") (part "1X01"))
    )
    (comp (ref "JP859")
      (value "1X01")
      (footprint "eagle-import:1X01")
      (libsource (lib "eagle-import") (part "1X01"))
    )
    (comp (ref "MC1")
      (value "STM32_BLUEPILL")
      (footprint "eagle-import:STM32_BLUEPILL")
      (libsource (lib "eagle-import") (part "STM32_BLUEPILL"))
    )
    (comp (ref "POWER")
      (value "CONN_05X2SHD")
      (footprint "eagle-import:2X5-SHROUDED")
      (libsource (lib "eagle-import") (part "CONN_05X2SHD"))
    )
    (comp (ref "R1")
      (value "3RP/1610N")
      (footprint "eagle-import:3RP_1610N")
      (libsource (lib "eagle-import") (part "3RP/1610N"))
    )
    (comp (ref "R2")
      (value "3RP/1610N")
      (footprint "eagle-import:3RP_1610N")
      (libsource (lib "eagle-import") (part "3RP/1610N"))
    )
    (comp (ref "R3")
      (value "3RP/1610N")
      (footprint "eagle-import:3RP_1610N")
      (libsource (lib "eagle-import") (part "3RP/1610N"))
    )
    (comp (ref "R4")
      (value "3RP/1610N")
      (footprint "eagle-import:3RP_1610N")
      (libsource (lib "eagle-import") (part "3RP/1610N"))
    )
    (comp (ref "U$1")
      (value "RIGHTANGLE")
      (footprint "eagle-import:RIGHTANGLE")
      (libsource (lib "eagle-import") (part "RIGHTANGLE"))
    )
    (comp (ref "U$2")
      (value "RIGHTANGLE")
      (footprint "eagle-import:RIGHTANGLE")
      (libsource (lib "eagle-import") (part "RIGHTANGLE"))
    )
  )
  (nets
    (net (code "1") (name "+3V3") (class "Default")
      (node (ref "C5") (pin "1") (pinfunction "1_1") (pintype "passive"))
      (node (ref "IC2") (pin "GND") (pinfunction "OUT_GND") (pintype "passive"))
      (node (ref "JP345") (pin "1") (pinfunction "1_1") (pintype "passive"))
      (node (ref "JP779") (pin "1") (pinfunction "1_1") (pintype "passive"))
      (node (ref "MC1") (pin "20") (pinfunction "20_20") (pintype "passive"))
    )
    (net (code "2") (name "+5V") (class "Default")
      (node (ref "C6") (pin "1") (pinfunction "1_1") (pintype "passive"))
      (node (ref "IC1") (pin "3") (pinfunction "VIN_3") (pintype "input"))
      (node (ref "IC3") (pin "3") (pinfunction "VO_3") (pintype "passive"))
      (node (ref "JP344") (pin "1") (pinfunction "1_1") (pintype "passive"))
      (node (ref "JP778") (pin "1") (pinfunction "1_1") (pintype "passive"))
    )
    (net (code "3") (name "+12V") (class "Default")
      (node (ref "C7") (pin "1") (pinfunction "1_1") (pintype "passive"))
      (node (ref "C8") (pin "+") (pinfunction "+_+") (pintype "passive"))
      (node (ref "IC2") (pin "OUT") (pinfunction "IN_OUT") (pintype "input"))
      (node (ref "IC3") (pin "1") (pinfunction "VI_1") (pintype "input"))
      (node (ref "JP114") (pin "1") (pinfunction "1_1") (pintype "passive"))
      (node (ref "JP115") (pin "1") (pinfunction "1_1") (pintype "passive"))
      (node (ref "JP117") (pin "1") (pinfunction "1_1") (pintype "passive"))
      (node (ref "JP118") (pin "1") (pinfunction "1_1") (pintype "passive"))
      (node (ref "JP119") (pin "1") (pinfunction "1_1") (pintype "passive"))
      (node (ref "JP120") (pin "1") (pinfunction "1_1") (pintype "passive"))
      (node (ref "JP121") (pin "1") (pinfunction "1_1") (pintype "passive"))
      (node (ref "JP122") (pin "1") (pinfunction "1_1") (pintype "passive"))
      (node (ref "JP123") (pin "1") (pinfunction "1_1") (pintype "passive"))
      (node (ref "JP124") (pin "1") (pinfunction "1_1") (pintype "passive"))
      (node (ref "JP125") (pin "1") (pinfunction "1_1") (pintype "passive"))
      (node (ref "JP126") (pin "1") (pinfunction "1_1") (pintype "passive"))
      (node (ref "JP127") (pin "1") (pinfunction "1_1") (pintype "passive"))
      (node (ref "JP128") (pin "1") (pinfunction "1_1") (pintype "passive"))
      (node (ref "JP129") (pin "1") (pinfunction "1_1") (pintype "passive"))
      (node (ref "JP130") (pin "1") (pinfunction "1_1") (pintype "passive"))
      (node (ref "JP131") (pin "1") (pinfunction "1_1") (pintype "passive"))
      (node (ref "JP132") (pin "1") (pinfunction "1_1") (pintype "passive"))
      (node (ref "JP133") (pin "1") (pinfunction "1_1") (pintype "passive"))
      (node (ref "JP134") (pin "1") (pinfunction "1_1") (pintype "passive"))
      (node (ref "JP135") (pin "1") (pinfunction "1_1") (pintype "passive"))
      (node (ref "JP136") (pin "1") (pinfunction "1_1") (pintype "passive"))
      (node (ref "JP137") (pin "1") (pinfunction "1_1") (pintype "passive"))
      (node (ref "JP138") (pin "1") (pinfunction "1_1") (pintype "passive"))
      (node (ref "JP139") (pin "1") (pinfunction "1_1") (pintype "passive"))
      (node (ref "JP140") (pin "1") (pinfunction "1_1") (pintype "passive"))
      (node (ref "JP141") (pin "1") (pinfunction "1_1") (pintype "passive"))
      (node (ref "JP142") (pin "1") (pinfunction "1_1") (pintype "passive"))
      (node (ref "JP143") (pin "1") (pinfunction "1_1") (pintype "passive"))
      (node (ref "JP144") (pin "1") (pinfunction "1_1") (pintype "passive"))
      (node (ref "JP145") (pin "1") (pinfunction "1_1") (pintype "passive"))
      (node (ref "JP146") (pin "1") (pinfunction "1_1") (pintype "passive"))
      (node (ref "JP147") (pin "1") (pinfunction "1_1") (pintype "passive"))
      (node (ref "JP148") (pin "1") (pinfunction "1_1") (pintype "passive"))
      (node (ref "JP149") (pin "1") (pinfunction "1_1") (pintype "passive"))
      (node (ref "JP150") (pin "1") (pinfunction "1_1") (pintype "passive"))
      (node (ref "JP151") (pin "1") (pinfunction "1_1") (pintype "passive"))
      (node (ref "JP152") (pin "1") (pinfunction "1_1") (pintype "passive"))
      (node (ref "POWER") (pin "10") (pinfunction "10_10") (pintype "passive"))
      (node (ref "POWER") (pin "9") (pinfunction "9_9") (pintype "passive"))
    )
    (net (code "4") (name "-12V") (class "Default")
      (node (ref "C7") (pin "2") (pinfunction "2_2") (pintype "passive"))
      (node (ref "C9") (pin "-") (pinfunction "-_-") (pintype "passive"))
      (node (ref "JP267") (pin "1") (pinfunction "1_1") (pintype "passive"))
      (node (ref "JP268") (pin "1") (pinfunction "1_1") (pintype "passive"))
      (node (ref "JP269") (pin "1") (pinfunction "1_1") (pintype "passive"))
      (node (ref "JP270") (pin "1") (pinfunction "1_1") (pintype "passive"))
      (node (ref "JP271") (pin "1") (pinfunction "1_1") (pintype "passive"))
      (node (ref "JP272") (pin "1") (pinfunction "1_1") (pintype "passive"))
      (node (ref "JP273") (pin "1") (pinfunction "1_1") (pintype "passive"))
      (node (ref "JP274") (pin "1") (pinfunction "1_1") (pintype "passive"))
      (node (ref "JP275") (pin "1") (pinfunction "1_1") (pintype "passive"))
      (node (ref "JP276") (pin "1") (pinfunction "1_1") (pintype "passive"))
      (node (ref "JP277") (pin "1") (pinfunction "1_1") (pintype "passive"))
      (node (ref "JP278") (pin "1") (pinfunction "1_1") (pintype "passive"))
      (node (ref "JP279") (pin "1") (pinfunction "1_1") (pintype "passive"))
      (node (ref "JP280") (pin "1") (pinfunction "1_1") (pintype "passive"))
      (node (ref "JP281") (pin "1") (pinfunction "1_1") (pintype "passive"))
      (node (ref "JP282") (pin "1") (pinfunction "1_1") (pintype "passive"))
      (node (ref "JP283") (pin "1") (pinfunction "1_1") (pintype "passive"))
      (node (ref "JP284") (pin "1") (pinfunction "1_1") (pintype "passive"))
      (node (ref "JP285") (pin "1") (pinfunction "1_1") (pintype "passive"))
      (node (ref "JP286") (pin "1") (pinfunction "1_1") (pintype "passive"))
      (node (ref "JP287") (pin "1") (pinfunction "1_1") (pintype "passive"))
      (node (ref "JP288") (pin "1") (pinfunction "1_1") (pintype "passive"))
      (node (ref "JP289") (pin "1") (pinfunction "1_1") (pintype "passive"))
      (node (ref "JP290") (pin "1") (pinfunction "1_1") (pintype "passive"))
      (node (ref "JP291") (pin "1") (pinfunction "1_1") (pintype "passive"))
      (node (ref "JP292") (pin "1") (pinfunction "1_1") (pintype "passive"))
      (node (ref "JP293") (pin "1") (pinfunction "1_1") (pintype "passive"))
      (node (ref "JP294") (pin "1") (pinfunction "1_1") (pintype "passive"))
      (node (ref "JP295") (pin "1") (pinfunction "1_1") (pintype "passive"))
      (node (ref "JP296") (pin "1") (pinfunction "1_1") (pintype "passive"))
      (node (ref "JP297") (pin "1") (pinfunction "1_1") (pintype "passive"))
      (node (ref "JP298") (pin "1") (pinfunction "1_1") (pintype "passive"))
      (node (ref "JP299") (pin "1") (pinfunction "1_1") (pintype "passive"))
      (node (ref "JP300") (pin "1") (pinfunction "1_1") (pintype "passive"))
      (node (ref "JP301") (pin "1") (pinfunction "1_1") (pintype "passive"))
      (node (ref "JP302") (pin "1") (pinfunction "1_1") (pintype "passive"))
      (node (ref "JP303") (pin "1") (pinfunction "1_1") (pintype "passive"))
      (node (ref "JP304") (pin "1") (pinfunction "1_1") (pintype "passive"))
      (node (ref "POWER") (pin "1") (pinfunction "1_1") (pintype "passive"))
      (node (ref "POWER") (pin "2") (pinfunction "2_2") (pintype "passive"))
    )
    (net (code "5") (name "/MISO2") (class "Default")
      (node (ref "JP798") (pin "1") (pinfunction "1_1") (pintype "passive"))
      (node (ref "JP799") (pin "1") (pinfunction "1_1") (pintype "passive"))
      (node (ref "MC1") (pin "3") (pinfunction "3_3") (pintype "passive"))
    )
    (net (code "6") (name "/MOSI2") (class "Default")
      (node (ref "JP800") (pin "1") (pinfunction "1_1") (pintype "passive"))
      (node (ref "JP801") (pin "1") (pinfunction "1_1") (pintype "passive"))
      (node (ref "MC1") (pin "4") (pinfunction "4_4") (pintype "passive"))
    )
    (net (code "7") (name "/N$16") (class "Default")
      (node (ref "GATE1") (pin "2") (pinfunction "2_2") (pintype "passive"))
      (node (ref "JP725") (pin "1") (pinfunction "1_1") (pintype "passive"))
      (node (ref "JP733") (pin "1") (pinfunction "1_1") (pintype "passive"))
      (node (ref "U$2") (pin "P$2") (pinfunction "1_P$2") (pintype "passive"))
    )
    (net (code "8") (name "/RESET") (class "Default")
      (node (ref "JP828") (pin "1") (pinfunction "1_1") (pintype "passive"))
      (node (ref "JP829") (pin "1") (pinfunction "1_1") (pintype "passive"))
      (node (ref "MC1") (pin "37") (pinfunction "37_37") (pintype "passive"))
    )
    (net (code "9") (name "/RX3") (class "Default")
      (node (ref "JP830") (pin "1") (pinfunction "1_1") (pintype "passive"))
      (node (ref "JP831") (pin "1") (pinfunction "1_1") (pintype "passive"))
      (node (ref "MC1") (pin "36") (pinfunction "36_36") (pintype "passive"))
    )
    (net (code "10") (name "/SCK2") (class "Default")
      (node (ref "JP796") (pin "1") (pinfunction "1_1") (pintype "passive"))
      (node (ref "JP797") (pin "1") (pinfunction "1_1") (pintype "passive"))
      (node (ref "MC1") (pin "2") (pinfunction "2_2") (pintype "passive"))
    )
    (net (code "11") (name "/SS2") (class "Default")
      (node (ref "JP784") (pin "1") (pinfunction "1_1") (pintype "passive"))
      (node (ref "JP795") (pin "1") (pinfunction "1_1") (pintype "passive"))
      (node (ref "MC1") (pin "1") (pinfunction "1_1") (pintype "passive"))
    )
    (net (code "12") (name "/TX3") (class "Default")
      (node (ref "JP832") (pin "1") (pinfunction "1_1") (pintype "passive"))
      (node (ref "JP833") (pin "1") (pinfunction "1_1") (pintype "passive"))
      (node (ref "MC1") (pin "35") (pinfunction "35_35") (pintype "passive"))
    )
    (net (code "13") (name "/VREF") (class "Default")
      (node (ref "C13") (pin "+") (pinfunction "+_+") (pintype "passive"))
      (node (ref "IC1") (pin "2") (pinfunction "VO_2") (pintype "output"))
      (node (ref "JP781") (pin "1") (pinfunction "1_1") (pintype "passive"))
      (node (ref "JP782") (pin "1") (pinfunction "1_1") (pintype "passive"))
      (node (ref "JP783") (pin "1") (pinfunction "1_1") (pintype "passive"))
    )
    (net (code "14") (name "GND") (class "Default")
      (node (ref "C13") (pin "-") (pinfunction "-_-") (pintype "passive"))
      (node (ref "C5") (pin "2") (pinfunction "2_2") (pintype "passive"))
      (node (ref "C6") (pin "2") (pinfunction "2_2") (pintype "passive"))
      (node (ref "C8") (pin "-") (pinfunction "-_-") (pintype "passive"))
      (node (ref "C9") (pin "+") (pinfunction "+_+") (pintype "passive"))
      (node (ref "GATE1") (pin "1") (pinfunction "1_1") (pintype "passive"))
      (node (ref "GATE2") (pin "1") (pinfunction "1_1") (pintype "passive"))
      (node (ref "IC1") (pin "1") (pinfunction "GND_1") (pintype "passive"))
      (node (ref "IC2") (pin "IN") (pinfunction "GND_IN") (pintype "input"))
      (node (ref "IC3") (pin "2") (pinfunction "GND_2") (pintype "passive"))
      (node (ref "JP154") (pin "1") (pinfunction "1_1") (pintype "passive"))
      (node (ref "JP155") (pin "1") (pinfunction "1_1") (pintype "passive"))
      (node (ref "JP156") (pin "1") (pinfunction "1_1") (pintype "passive"))
      (node (ref "JP157") (pin "1") (pinfunction "1_1") (pintype "passive"))
      (node (ref "JP158") (pin "1") (pinfunction "1_1") (pintype "passive"))
      (node (ref "JP159") (pin "1") (pinfunction "1_1") (pintype "passive"))
      (node (ref "JP160") (pin "1") (pinfunction "1_1") (pintype "passive"))
      (node (ref "JP161") (pin "1") (pinfunction "1_1") (pintype "passive"))
      (node (ref "JP162") (pin "1") (pinfunction "1_1") (pintype "passive"))
      (node (ref "JP163") (pin "1") (pinfunction "1_1") (pintype "passive"))
      (node (ref "JP164") (pin "1") (pinfunction "1_1") (pintype "passive"))
      (node (ref "JP165") (pin "1") (pinfunction "1_1") (pintype "passive"))
      (node (ref "JP166") (pin "1") (pinfunction "1_1") (pintype "passive"))
      (node (ref "JP167") (pin "1") (pinfunction "1_1") (pintype "passive"))
      (node (ref "JP168") (pin "1") (pinfunction "1_1") (pintype "passive"))
      (node (ref "JP169") (pin "1") (pinfunction "1_1") (pintype "passive"))
      (node (ref "JP170") (pin "1") (pinfunction "1_1") (pintype "passive"))
      (node (ref "JP171") (pin "1") (pinfunction "1_1") (pintype "passive"))
      (node (ref "JP172") (pin "1") (pinfunction "1_1") (pintype "passive"))
      (node (ref "JP173") (pin "1") (pinfunction "1_1") (pintype "passive"))
      (node (ref "JP174") (pin "1") (pinfunction "1_1") (pintype "passive"))
      (node (ref "JP175") (pin "1") (pinfunction "1_1") (pintype "passive"))
      (node (ref "JP176") (pin "1") (pinfunction "1_1") (pintype "passive"))
      (node (ref "JP177") (pin "1") (pinfunction "1_1") (pintype "passive"))
      (node (ref "JP178") (pin "1") (pinfunction "1_1") (pintype "passive"))
      (node (ref "JP179") (pin "1") (pinfunction "1_1") (pintype "passive"))
      (node (ref "JP180") (pin "1") (pinfunction "1_1") (pintype "passive"))
      (node (ref "JP181") (pin "1") (pinfunction "1_1") (pintype "passive"))
      (node (ref "JP182") (pin "1") (pinfunction "1_1") (pintype "passive"))
      (node (ref "JP183") (pin "1") (pinfunction "1_1") (pintype "passive"))
      (node (ref "JP184") (pin "1") (pinfunction "1_1") (pintype "passive"))
      (node (ref "JP185") (pin "1") (pinfunction "1_1") (pintype "passive"))
      (node (ref "JP186") (pin "1") (pinfunction "1_1") (pintype "passive"))
      (node (ref "JP187") (pin "1") (pinfunction "1_1") (pintype "passive"))
      (node (ref "JP188") (pin "1") (pinfunction "1_1") (pintype "passive"))
      (node (ref "JP189") (pin "1") (pinfunction "1_1") (pintype "passive"))
      (node (ref "JP190") (pin "1") (pinfunction "1_1") (pintype "passive"))
      (node (ref "JP305") (pin "1") (pinfunction "1_1") (pintype "passive"))
      (node (ref "JP306") (pin "1") (pinfunction "1_1") (pintype "passive"))
      (node (ref "JP307") (pin "1") (pinfunction "1_1") (pintype "passive"))
      (node (ref "JP308") (pin "1") (pinfunction "1_1") (pintype "passive"))
      (node (ref "JP309") (pin "1") (pinfunction "1_1") (pintype "passive"))
      (node (ref "JP310") (pin "1") (pinfunction "1_1") (pintype "passive"))
      (node (ref "JP311") (pin "1") (pinfunction "1_1") (pintype "passive"))
      (node (ref "JP312") (pin "1") (pinfunction "1_1") (pintype "passive"))
      (node (ref "JP313") (pin "1") (pinfunction "1_1") (pintype "passive"))
      (node (ref "JP314") (pin "1") (pinfunction "1_1") (pintype "passive"))
      (node (ref "JP315") (pin "1") (pinfunction "1_1") (pintype "passive"))
      (node (ref "JP316") (pin "1") (pinfunction "1_1") (pintype "passive"))
      (node (ref "JP317") (pin "1") (pinfunction "1_1") (pintype "passive"))
      (node (ref "JP318") (pin "1") (pinfunction "1_1") (pintype "passive"))
      (node (ref "JP319") (pin "1") (pinfunction "1_1") (pintype "passive"))
      (node (ref "JP320") (pin "1") (pinfunction "1_1") (pintype "passive"))
      (node (ref "JP321") (pin "1") (pinfunction "1_1") (pintype "passive"))
      (node (ref "JP322") (pin "1") (pinfunction "1_1") (pintype "passive"))
      (node (ref "JP323") (pin "1") (pinfunction "1_1") (pintype "passive"))
      (node (ref "JP324") (pin "1") (pinfunction "1_1") (pintype "passive"))
      (node (ref "JP325") (pin "1") (pinfunction "1_1") (pintype "passive"))
      (node (ref "JP326") (pin "1") (pinfunction "1_1") (pintype "passive"))
      (node (ref "JP327") (pin "1") (pinfunction "1_1") (pintype "passive"))
      (node (ref "JP328") (pin "1") (pinfunction "1_1") (pintype "passive"))
      (node (ref "JP329") (pin "1") (pinfunction "1_1") (pintype "passive"))
      (node (ref "JP330") (pin "1") (pinfunction "1_1") (pintype "passive"))
      (node (ref "JP331") (pin "1") (pinfunction "1_1") (pintype "passive"))
      (node (ref "JP332") (pin "1") (pinfunction "1_1") (pintype "passive"))
      (node (ref "JP333") (pin "1") (pinfunction "1_1") (pintype "passive"))
      (node (ref "JP334") (pin "1") (pinfunction "1_1") (pintype "passive"))
      (node (ref "JP335") (pin "1") (pinfunction "1_1") (pintype "passive"))
      (node (ref "JP336") (pin "1") (pinfunction "1_1") (pintype "passive"))
      (node (ref "JP337") (pin "1") (pinfunction "1_1") (pintype "passive"))
      (node (ref "JP338") (pin "1") (pinfunction "1_1") (pintype "passive"))
      (node (ref "JP339") (pin "1") (pinfunction "1_1") (pintype "passive"))
      (node (ref "JP340") (pin "1") (pinfunction "1_1") (pintype "passive"))
      (node (ref "JP341") (pin "1") (pinfunction "1_1") (pintype "passive"))
      (node (ref "JP342") (pin "1") (pinfunction "1_1") (pintype "passive"))
      (node (ref "JP343") (pin "1") (pinfunction "1_1") (pintype "passive"))
      (node (ref "JP788") (pin "1") (pinfunction "1_1") (pintype "passive"))
      (node (ref "MC1") (pin "19") (pinfunction "19_19") (pintype "passive"))
      (node (ref "MC1") (pin "39") (pinfunction "39_39") (pintype "passive"))
      (node (ref "MC1") (pin "40") (pinfunction "40_40") (pintype "passive"))
      (node (ref "POWER") (pin "3") (pinfunction "3_3") (pintype "passive"))
      (node (ref "POWER") (pin "4") (pinfunction "4_4") (pintype "passive"))
      (node (ref "POWER") (pin "5") (pinfunction "5_5") (pintype "passive"))
      (node (ref "POWER") (pin "6") (pinfunction "6_6") (pintype "passive"))
      (node (ref "POWER") (pin "7") (pinfunction "7_7") (pintype "passive"))
      (node (ref "POWER") (pin "8") (pinfunction "8_8") (pintype "passive"))
      (node (ref "U$2") (pin "P$3") (pinfunction "1_P$3") (pintype "passive"))
    )
    (net (code "15") (name "Net-(GATE1-Pad3)") (class "Default")
      (node (ref "GATE1") (pin "3") (pinfunction "3_3") (pintype "passive"))
      (node (ref "JP726") (pin "1") (pinfunction "1_1") (pintype "passive"))
      (node (ref "JP734") (pin "1") (pinfunction "1_1") (pintype "passive"))
    )
    (net (code "16") (name "Net-(GATE1-Pad4)") (class "Default")
      (node (ref "GATE1") (pin "4") (pinfunction "4_4") (pintype "passive"))
      (node (ref "JP727") (pin "1") (pinfunction "1_1") (pintype "passive"))
      (node (ref "JP736") (pin "1") (pinfunction "1_1") (pintype "passive"))
    )
    (net (code "17") (name "Net-(GATE1-Pad5)") (class "Default")
      (node (ref "GATE1") (pin "5") (pinfunction "5_5") (pintype "passive"))
      (node (ref "JP728") (pin "1") (pinfunction "1_1") (pintype "passive"))
      (node (ref "JP735") (pin "1") (pinfunction "1_1") (pintype "passive"))
    )
    (net (code "18") (name "Net-(GATE2-Pad2)") (class "Default")
      (node (ref "GATE2") (pin "2") (pinfunction "2_2") (pintype "passive"))
      (node (ref "JP729") (pin "1") (pinfunction "1_1") (pintype "passive"))
      (node (ref "JP737") (pin "1") (pinfunction "1_1") (pintype "passive"))
    )
    (net (code "19") (name "Net-(GATE2-Pad3)") (class "Default")
      (node (ref "GATE2") (pin "3") (pinfunction "3_3") (pintype "passive"))
      (node (ref "JP730") (pin "1") (pinfunction "1_1") (pintype "passive"))
      (node (ref "JP738") (pin "1") (pinfunction "1_1") (pintype "passive"))
    )
    (net (code "20") (name "Net-(GATE2-Pad4)") (class "Default")
      (node (ref "GATE2") (pin "4") (pinfunction "4_4") (pintype "passive"))
      (node (ref "JP731") (pin "1") (pinfunction "1_1") (pintype "passive"))
      (node (ref "JP739") (pin "1") (pinfunction "1_1") (pintype "passive"))
    )
    (net (code "21") (name "Net-(GATE2-Pad5)") (class "Default")
      (node (ref "GATE2") (pin "5") (pinfunction "5_5") (pintype "passive"))
      (node (ref "JP732") (pin "1") (pinfunction "1_1") (pintype "passive"))
      (node (ref "JP740") (pin "1") (pinfunction "1_1") (pintype "passive"))
    )
    (net (code "22") (name "Net-(JP46-Pad1)") (class "Default")
      (node (ref "JP46") (pin "1") (pinfunction "1_1") (pintype "passive"))
      (node (ref "JP48") (pin "1") (pinfunction "1_1") (pintype "passive"))
    )
    (net (code "23") (name "Net-(JP50-Pad1)") (class "Default")
      (node (ref "JP50") (pin "1") (pinfunction "1_1") (pintype "passive"))
      (node (ref "JP52") (pin "1") (pinfunction "1_1") (pintype "passive"))
    )
    (net (code "24") (name "Net-(JP54-Pad1)") (class "Default")
      (node (ref "JP54") (pin "1") (pinfunction "1_1") (pintype "passive"))
      (node (ref "JP56") (pin "1") (pinfunction "1_1") (pintype "passive"))
    )
    (net (code "25") (name "Net-(JP58-Pad1)") (class "Default")
      (node (ref "JP58") (pin "1") (pinfunction "1_1") (pintype "passive"))
      (node (ref "JP60") (pin "1") (pinfunction "1_1") (pintype "passive"))
    )
    (net (code "26") (name "Net-(JP62-Pad1)") (class "Default")
      (node (ref "JP62") (pin "1") (pinfunction "1_1") (pintype "passive"))
      (node (ref "JP64") (pin "1") (pinfunction "1_1") (pintype "passive"))
    )
    (net (code "27") (name "Net-(JP66-Pad1)") (class "Default")
      (node (ref "JP66") (pin "1") (pinfunction "1_1") (pintype "passive"))
      (node (ref "JP68") (pin "1") (pinfunction "1_1") (pintype "passive"))
    )
    (net (code "28") (name "Net-(JP69-Pad1)") (class "Default")
      (node (ref "JP69") (pin "1") (pinfunction "1_1") (pintype "passive"))
      (node (ref "JP70") (pin "1") (pinfunction "1_1") (pintype "passive"))
    )
    (net (code "29") (name "Net-(JP71-Pad1)") (class "Default")
      (node (ref "JP71") (pin "1") (pinfunction "1_1") (pintype "passive"))
      (node (ref "JP72") (pin "1") (pinfunction "1_1") (pintype "passive"))
    )
    (net (code "30") (name "Net-(JP73-Pad1)") (class "Default")
      (node (ref "JP73") (pin "1") (pinfunction "1_1") (pintype "passive"))
      (node (ref "JP74") (pin "1") (pinfunction "1_1") (pintype "passive"))
    )
    (net (code "31") (name "Net-(JP75-Pad1)") (class "Default")
      (node (ref "JP75") (pin "1") (pinfunction "1_1") (pintype "passive"))
      (node (ref "JP76") (pin "1") (pinfunction "1_1") (pintype "passive"))
    )
    (net (code "32") (name "Net-(JP77-Pad1)") (class "Default")
      (node (ref "JP77") (pin "1") (pinfunction "1_1") (pintype "passive"))
      (node (ref "JP78") (pin "1") (pinfunction "1_1") (pintype "passive"))
    )
    (net (code "33") (name "Net-(JP79-Pad1)") (class "Default")
      (node (ref "JP79") (pin "1") (pinfunction "1_1") (pintype "passive"))
      (node (ref "JP80") (pin "1") (pinfunction "1_1") (pintype "passive"))
    )
    (net (code "34") (name "Net-(JP81-Pad1)") (class "Default")
      (node (ref "JP81") (pin "1") (pinfunction "1_1") (pintype "passive"))
      (node (ref "JP82") (pin "1") (pinfunction "1_1") (pintype "passive"))
    )
    (net (code "35") (name "Net-(JP83-Pad1)") (class "Default")
      (node (ref "JP83") (pin "1") (pinfunction "1_1") (pintype "passive"))
      (node (ref "JP84") (pin "1") (pinfunction "1_1") (pintype "passive"))
    )
    (net (code "36") (name "Net-(JP85-Pad1)") (class "Default")
      (node (ref "JP85") (pin "1") (pinfunction "1_1") (pintype "passive"))
      (node (ref "JP86") (pin "1") (pinfunction "1_1") (pintype "passive"))
    )
    (net (code "37") (name "Net-(JP88-Pad1)") (class "Default")
      (node (ref "JP88") (pin "1") (pinfunction "1_1") (pintype "passive"))
      (node (ref "JP89") (pin "1") (pinfunction "1_1") (pintype "passive"))
    )
    (net (code "38") (name "Net-(JP90-Pad1)") (class "Default")
      (node (ref "JP90") (pin "1") (pinfunction "1_1") (pintype "passive"))
      (node (ref "JP93") (pin "1") (pinfunction "1_1") (pintype "passive"))
    )
    (net (code "39") (name "Net-(JP91-Pad1)") (class "Default")
      (node (ref "JP91") (pin "1") (pinfunction "1_1") (pintype "passive"))
      (node (ref "JP92") (pin "1") (pinfunction "1_1") (pintype "passive"))
    )
    (net (code "40") (name "Net-(JP94-Pad1)") (class "Default")
      (node (ref "JP94") (pin "1") (pinfunction "1_1") (pintype "passive"))
      (node (ref "JP95") (pin "1") (pinfunction "1_1") (pintype "passive"))
    )
    (net (code "41") (name "Net-(JP96-Pad1)") (class "Default")
      (node (ref "JP96") (pin "1") (pinfunction "1_1") (pintype "passive"))
      (node (ref "JP97") (pin "1") (pinfunction "1_1") (pintype "passive"))
    )
    (net (code "42") (name "Net-(JP98-Pad1)") (class "Default")
      (node (ref "JP98") (pin "1") (pinfunction "1_1") (pintype "passive"))
      (node (ref "JP99") (pin "1") (pinfunction "1_1") (pintype "passive"))
    )
    (net (code "43") (name "Net-(JP100-Pad1)") (class "Default")
      (node (ref "JP100") (pin "1") (pinfunction "1_1") (pintype "passive"))
      (node (ref "JP101") (pin "1") (pinfunction "1_1") (pintype "passive"))
    )
    (net (code "44") (name "Net-(JP102-Pad1)") (class "Default")
      (node (ref "JP102") (pin "1") (pinfunction "1_1") (pintype "passive"))
      (node (ref "JP103") (pin "1") (pinfunction "1_1") (pintype "passive"))
      (node (ref "JP790") (pin "1") (pinfunction "1_1") (pintype "passive"))
    )
    (net (code "45") (name "Net-(JP104-Pad1)") (class "Default")
      (node (ref "JP104") (pin "1") (pinfunction "1_1") (pintype "passive"))
      (node (ref "JP105") (pin "1") (pinfunction "1_1") (pintype "passive"))
    )
    (net (code "46") (name "Net-(JP106-Pad1)") (class "Default")
      (node (ref "JP106") (pin "1") (pinfunction "1_1") (pintype "passive"))
      (node (ref "JP107") (pin "1") (pinfunction "1_1") (pintype "passive"))
    )
    (net (code "47") (name "Net-(JP108-Pad1)") (class "Default")
      (node (ref "JP108") (pin "1") (pinfunction "1_1") (pintype "passive"))
      (node (ref "JP109") (pin "1") (pinfunction "1_1") (pintype "passive"))
    )
    (net (code "48") (name "Net-(JP110-Pad1)") (class "Default")
      (node (ref "JP110") (pin "1") (pinfunction "1_1") (pintype "passive"))
      (node (ref "JP111") (pin "1") (pinfunction "1_1") (pintype "passive"))
    )
    (net (code "49") (name "Net-(JP112-Pad1)") (class "Default")
      (node (ref "JP112") (pin "1") (pinfunction "1_1") (pintype "passive"))
      (node (ref "JP113") (pin "1") (pinfunction "1_1") (pintype "passive"))
    )
    (net (code "50") (name "Net-(JP116-Pad1)") (class "Default")
      (node (ref "JP116") (pin "1") (pinfunction "1_1") (pintype "passive"))
      (node (ref "JP789") (pin "1") (pinfunction "1_1") (pintype "passive"))
      (node (ref "JP87") (pin "1") (pinfunction "1_1") (pintype "passive"))
    )
    (net (code "51") (name "Net-(JP193-Pad1)") (class "Default")
      (node (ref "JP193") (pin "1") (pinfunction "1_1") (pintype "passive"))
      (node (ref "JP194") (pin "1") (pinfunction "1_1") (pintype "passive"))
      (node (ref "JP195") (pin "1") (pinfunction "1_1") (pintype "passive"))
      (node (ref "JP196") (pin "1") (pinfunction "1_1") (pintype "passive"))
      (node (ref "JP197") (pin "1") (pinfunction "1_1") (pintype "passive"))
      (node (ref "JP198") (pin "1") (pinfunction "1_1") (pintype "passive"))
      (node (ref "JP199") (pin "1") (pinfunction "1_1") (pintype "passive"))
      (node (ref "JP200") (pin "1") (pinfunction "1_1") (pintype "passive"))
      (node (ref "JP201") (pin "1") (pinfunction "1_1") (pintype "passive"))
      (node (ref "JP202") (pin "1") (pinfunction "1_1") (pintype "passive"))
      (node (ref "JP203") (pin "1") (pinfunction "1_1") (pintype "passive"))
      (node (ref "JP204") (pin "1") (pinfunction "1_1") (pintype "passive"))
      (node (ref "JP205") (pin "1") (pinfunction "1_1") (pintype "passive"))
      (node (ref "JP206") (pin "1") (pinfunction "1_1") (pintype "passive"))
      (node (ref "JP207") (pin "1") (pinfunction "1_1") (pintype "passive"))
      (node (ref "JP208") (pin "1") (pinfunction "1_1") (pintype "passive"))
      (node (ref "JP209") (pin "1") (pinfunction "1_1") (pintype "passive"))
      (node (ref "JP210") (pin "1") (pinfunction "1_1") (pintype "passive"))
      (node (ref "JP211") (pin "1") (pinfunction "1_1") (pintype "passive"))
      (node (ref "JP212") (pin "1") (pinfunction "1_1") (pintype "passive"))
      (node (ref "JP213") (pin "1") (pinfunction "1_1") (pintype "passive"))
      (node (ref "JP214") (pin "1") (pinfunction "1_1") (pintype "passive"))
      (node (ref "JP215") (pin "1") (pinfunction "1_1") (pintype "passive"))
      (node (ref "JP216") (pin "1") (pinfunction "1_1") (pintype "passive"))
      (node (ref "JP217") (pin "1") (pinfunction "1_1") (pintype "passive"))
      (node (ref "JP218") (pin "1") (pinfunction "1_1") (pintype "passive"))
      (node (ref "JP219") (pin "1") (pinfunction "1_1") (pintype "passive"))
      (node (ref "JP220") (pin "1") (pinfunction "1_1") (pintype "passive"))
      (node (ref "JP221") (pin "1") (pinfunction "1_1") (pintype "passive"))
      (node (ref "JP222") (pin "1") (pinfunction "1_1") (pintype "passive"))
      (node (ref "JP223") (pin "1") (pinfunction "1_1") (pintype "passive"))
      (node (ref "JP224") (pin "1") (pinfunction "1_1") (pintype "passive"))
      (node (ref "JP225") (pin "1") (pinfunction "1_1") (pintype "passive"))
      (node (ref "JP226") (pin "1") (pinfunction "1_1") (pintype "passive"))
      (node (ref "JP227") (pin "1") (pinfunction "1_1") (pintype "passive"))
      (node (ref "JP228") (pin "1") (pinfunction "1_1") (pintype "passive"))
      (node (ref "JP724") (pin "1") (pinfunction "1_1") (pintype "passive"))
    )
    (net (code "52") (name "Net-(JP230-Pad1)") (class "Default")
      (node (ref "JP230") (pin "1") (pinfunction "1_1") (pintype "passive"))
      (node (ref "JP232") (pin "1") (pinfunction "1_1") (pintype "passive"))
      (node (ref "JP233") (pin "1") (pinfunction "1_1") (pintype "passive"))
      (node (ref "JP234") (pin "1") (pinfunction "1_1") (pintype "passive"))
      (node (ref "JP235") (pin "1") (pinfunction "1_1") (pintype "passive"))
      (node (ref "JP236") (pin "1") (pinfunction "1_1") (pintype "passive"))
      (node (ref "JP237") (pin "1") (pinfunction "1_1") (pintype "passive"))
      (node (ref "JP238") (pin "1") (pinfunction "1_1") (pintype "passive"))
      (node (ref "JP239") (pin "1") (pinfunction "1_1") (pintype "passive"))
      (node (ref "JP240") (pin "1") (pinfunction "1_1") (pintype "passive"))
      (node (ref "JP241") (pin "1") (pinfunction "1_1") (pintype "passive"))
      (node (ref "JP242") (pin "1") (pinfunction "1_1") (pintype "passive"))
      (node (ref "JP243") (pin "1") (pinfunction "1_1") (pintype "passive"))
      (node (ref "JP244") (pin "1") (pinfunction "1_1") (pintype "passive"))
      (node (ref "JP245") (pin "1") (pinfunction "1_1") (pintype "passive"))
      (node (ref "JP246") (pin "1") (pinfunction "1_1") (pintype "passive"))
      (node (ref "JP247") (pin "1") (pinfunction "1_1") (pintype "passive"))
      (node (ref "JP248") (pin "1") (pinfunction "1_1") (pintype "passive"))
      (node (ref "JP249") (pin "1") (pinfunction "1_1") (pintype "passive"))
      (node (ref "JP250") (pin "1") (pinfunction "1_1") (pintype "passive"))
      (node (ref "JP251") (pin "1") (pinfunction "1_1") (pintype "passive"))
      (node (ref "JP252") (pin "1") (pinfunction "1_1") (pintype "passive"))
      (node (ref "JP253") (pin "1") (pinfunction "1_1") (pintype "passive"))
      (node (ref "JP254") (pin "1") (pinfunction "1_1") (pintype "passive"))
      (node (ref "JP255") (pin "1") (pinfunction "1_1") (pintype "passive"))
      (node (ref "JP256") (pin "1") (pinfunction "1_1") (pintype "passive"))
      (node (ref "JP257") (pin "1") (pinfunction "1_1") (pintype "passive"))
      (node (ref "JP258") (pin "1") (pinfunction "1_1") (pintype "passive"))
      (node (ref "JP259") (pin "1") (pinfunction "1_1") (pintype "passive"))
      (node (ref "JP260") (pin "1") (pinfunction "1_1") (pintype "passive"))
      (node (ref "JP261") (pin "1") (pinfunction "1_1") (pintype "passive"))
      (node (ref "JP262") (pin "1") (pinfunction "1_1") (pintype "passive"))
      (node (ref "JP263") (pin "1") (pinfunction "1_1") (pintype "passive"))
      (node (ref "JP264") (pin "1") (pinfunction "1_1") (pintype "passive"))
      (node (ref "JP265") (pin "1") (pinfunction "1_1") (pintype "passive"))
      (node (ref "JP723") (pin "1") (pinfunction "1_1") (pintype "passive"))
    )
    (net (code "53") (name "Net-(JP742-Pad1)") (class "Default")
      (node (ref "JP742") (pin "1") (pinfunction "1_1") (pintype "passive"))
      (node (ref "JP743") (pin "1") (pinfunction "1_1") (pintype "passive"))
      (node (ref "JP744") (pin "1") (pinfunction "1_1") (pintype "passive"))
      (node (ref "JP745") (pin "1") (pinfunction "1_1") (pintype "passive"))
      (node (ref "JP746") (pin "1") (pinfunction "1_1") (pintype "passive"))
      (node (ref "JP747") (pin "1") (pinfunction "1_1") (pintype "passive"))
      (node (ref "JP748") (pin "1") (pinfunction "1_1") (pintype "passive"))
      (node (ref "JP749") (pin "1") (pinfunction "1_1") (pintype "passive"))
      (node (ref "JP750") (pin "1") (pinfunction "1_1") (pintype "passive"))
      (node (ref "JP751") (pin "1") (pinfunction "1_1") (pintype "passive"))
      (node (ref "JP752") (pin "1") (pinfunction "1_1") (pintype "passive"))
      (node (ref "JP753") (pin "1") (pinfunction "1_1") (pintype "passive"))
      (node (ref "JP754") (pin "1") (pinfunction "1_1") (pintype "passive"))
      (node (ref "JP755") (pin "1") (pinfunction "1_1") (pintype "passive"))
      (node (ref "JP756") (pin "1") (pinfunction "1_1") (pintype "passive"))
      (node (ref "JP757") (pin "1") (pinfunction "1_1") (pintype "passive"))
      (node (ref "JP758") (pin "1") (pinfunction "1_1") (pintype "passive"))
      (node (ref "JP759") (pin "1") (pinfunction "1_1") (pintype "passive"))
      (node (ref "JP760") (pin "1") (pinfunction "1_1") (pintype "passive"))
      (node (ref "JP761") (pin "1") (pinfunction "1_1") (pintype "passive"))
      (node (ref "JP762") (pin "1") (pinfunction "1_1") (pintype "passive"))
      (node (ref "JP763") (pin "1") (pinfunction "1_1") (pintype "passive"))
      (node (ref "JP764") (pin "1") (pinfunction "1_1") (pintype "passive"))
      (node (ref "JP765") (pin "1") (pinfunction "1_1") (pintype "passive"))
      (node (ref "JP766") (pin "1") (pinfunction "1_1") (pintype "passive"))
      (node (ref "JP767") (pin "1") (pinfunction "1_1") (pintype "passive"))
      (node (ref "JP768") (pin "1") (pinfunction "1_1") (pintype "passive"))
      (node (ref "JP769") (pin "1") (pinfunction "1_1") (pintype "passive"))
      (node (ref "JP770") (pin "1") (pinfunction "1_1") (pintype "passive"))
      (node (ref "JP771") (pin "1") (pinfunction "1_1") (pintype "passive"))
      (node (ref "JP772") (pin "1") (pinfunction "1_1") (pintype "passive"))
      (node (ref "JP773") (pin "1") (pinfunction "1_1") (pintype "passive"))
      (node (ref "JP774") (pin "1") (pinfunction "1_1") (pintype "passive"))
      (node (ref "JP775") (pin "1") (pinfunction "1_1") (pintype "passive"))
      (node (ref "JP776") (pin "1") (pinfunction "1_1") (pintype "passive"))
      (node (ref "JP777") (pin "1") (pinfunction "1_1") (pintype "passive"))
      (node (ref "JP780") (pin "1") (pinfunction "1_1") (pintype "passive"))
    )
    (net (code "54") (name "Net-(JP802-Pad1)") (class "Default")
      (node (ref "JP802") (pin "1") (pinfunction "1_1") (pintype "passive"))
      (node (ref "JP803") (pin "1") (pinfunction "1_1") (pintype "passive"))
      (node (ref "MC1") (pin "5") (pinfunction "5_5") (pintype "passive"))
    )
    (net (code "55") (name "Net-(JP804-Pad1)") (class "Default")
      (node (ref "JP804") (pin "1") (pinfunction "1_1") (pintype "passive"))
      (node (ref "JP805") (pin "1") (pinfunction "1_1") (pintype "passive"))
      (node (ref "MC1") (pin "6") (pinfunction "6_6") (pintype "passive"))
    )
    (net (code "56") (name "Net-(JP806-Pad1)") (class "Default")
      (node (ref "JP806") (pin "1") (pinfunction "1_1") (pintype "passive"))
      (node (ref "JP807") (pin "1") (pinfunction "1_1") (pintype "passive"))
      (node (ref "MC1") (pin "7") (pinfunction "7_7") (pintype "passive"))
    )
    (net (code "57") (name "Net-(JP808-Pad1)") (class "Default")
      (node (ref "JP808") (pin "1") (pinfunction "1_1") (pintype "passive"))
      (node (ref "JP809") (pin "1") (pinfunction "1_1") (pintype "passive"))
      (node (ref "MC1") (pin "8") (pinfunction "8_8") (pintype "passive"))
    )
    (net (code "58") (name "Net-(JP810-Pad1)") (class "Default")
      (node (ref "JP810") (pin "1") (pinfunction "1_1") (pintype "passive"))
      (node (ref "JP811") (pin "1") (pinfunction "1_1") (pintype "passive"))
      (node (ref "MC1") (pin "9") (pinfunction "9_9") (pintype "passive"))
    )
    (net (code "59") (name "Net-(JP812-Pad1)") (class "Default")
      (node (ref "JP812") (pin "1") (pinfunction "1_1") (pintype "passive"))
      (node (ref "JP813") (pin "1") (pinfunction "1_1") (pintype "passive"))
      (node (ref "MC1") (pin "10") (pinfunction "10_10") (pintype "passive"))
    )
    (net (code "60") (name "Net-(JP814-Pad1)") (class "Default")
      (node (ref "JP814") (pin "1") (pinfunction "1_1") (pintype "passive"))
      (node (ref "JP815") (pin "1") (pinfunction "1_1") (pintype "passive"))
      (node (ref "MC1") (pin "11") (pinfunction "11_11") (pintype "passive"))
    )
    (net (code "61") (name "Net-(JP816-Pad1)") (class "Default")
      (node (ref "JP816") (pin "1") (pinfunction "1_1") (pintype "passive"))
      (node (ref "JP817") (pin "1") (pinfunction "1_1") (pintype "passive"))
      (node (ref "MC1") (pin "12") (pinfunction "12_12") (pintype "passive"))
    )
    (net (code "62") (name "Net-(JP818-Pad1)") (class "Default")
      (node (ref "JP818") (pin "1") (pinfunction "1_1") (pintype "passive"))
      (node (ref "JP819") (pin "1") (pinfunction "1_1") (pintype "passive"))
      (node (ref "MC1") (pin "13") (pinfunction "13_13") (pintype "passive"))
    )
    (net (code "63") (name "Net-(JP820-Pad1)") (class "Default")
      (node (ref "JP820") (pin "1") (pinfunction "1_1") (pintype "passive"))
      (node (ref "JP821") (pin "1") (pinfunction "1_1") (pintype "passive"))
      (node (ref "MC1") (pin "14") (pinfunction "14_14") (pintype "passive"))
    )
    (net (code "64") (name "Net-(JP822-Pad1)") (class "Default")
      (node (ref "JP822") (pin "1") (pinfunction "1_1") (pintype "passive"))
      (node (ref "JP823") (pin "1") (pinfunction "1_1") (pintype "passive"))
      (node (ref "MC1") (pin "15") (pinfunction "15_15") (pintype "passive"))
    )
    (net (code "65") (name "Net-(JP824-Pad1)") (class "Default")
      (node (ref "JP824") (pin "1") (pinfunction "1_1") (pintype "passive"))
      (node (ref "JP825") (pin "1") (pinfunction "1_1") (pintype "passive"))
      (node (ref "MC1") (pin "16") (pinfunction "16_16") (pintype "passive"))
    )
    (net (code "66") (name "Net-(JP826-Pad1)") (class "Default")
      (node (ref "JP826") (pin "1") (pinfunction "1_1") (pintype "passive"))
      (node (ref "JP827") (pin "1") (pinfunction "1_1") (pintype "passive"))
      (node (ref "MC1") (pin "17") (pinfunction "17_17") (pintype "passive"))
    )
    (net (code "67") (name "Net-(JP834-Pad1)") (class "Default")
      (node (ref "JP834") (pin "1") (pinfunction "1_1") (pintype "passive"))
      (node (ref "JP835") (pin "1") (pinfunction "1_1") (pintype "passive"))
      (node (ref "MC1") (pin "34") (pinfunction "34_34") (pintype "passive"))
    )
    (net (code "68") (name "Net-(JP836-Pad1)") (class "Default")
      (node (ref "JP836") (pin "1") (pinfunction "1_1") (pintype "passive"))
      (node (ref "JP837") (pin "1") (pinfunction "1_1") (pintype "passive"))
      (node (ref "MC1") (pin "33") (pinfunction "33_33") (pintype "passive"))
    )
    (net (code "69") (name "Net-(JP838-Pad1)") (class "Default")
      (node (ref "JP838") (pin "1") (pinfunction "1_1") (pintype "passive"))
      (node (ref "JP839") (pin "1") (pinfunction "1_1") (pintype "passive"))
      (node (ref "MC1") (pin "32") (pinfunction "32_32") (pintype "passive"))
    )
    (net (code "70") (name "Net-(JP840-Pad1)") (class "Default")
      (node (ref "JP840") (pin "1") (pinfunction "1_1") (pintype "passive"))
      (node (ref "JP841") (pin "1") (pinfunction "1_1") (pintype "passive"))
      (node (ref "MC1") (pin "31") (pinfunction "31_31") (pintype "passive"))
    )
    (net (code "71") (name "Net-(JP842-Pad1)") (class "Default")
      (node (ref "JP842") (pin "1") (pinfunction "1_1") (pintype "passive"))
      (node (ref "JP843") (pin "1") (pinfunction "1_1") (pintype "passive"))
      (node (ref "MC1") (pin "30") (pinfunction "30_30") (pintype "passive"))
    )
    (net (code "72") (name "Net-(JP844-Pad1)") (class "Default")
      (node (ref "JP844") (pin "1") (pinfunction "1_1") (pintype "passive"))
      (node (ref "JP845") (pin "1") (pinfunction "1_1") (pintype "passive"))
      (node (ref "MC1") (pin "29") (pinfunction "29_29") (pintype "passive"))
    )
    (net (code "73") (name "Net-(JP846-Pad1)") (class "Default")
      (node (ref "JP846") (pin "1") (pinfunction "1_1") (pintype "passive"))
      (node (ref "JP847") (pin "1") (pinfunction "1_1") (pintype "passive"))
      (node (ref "MC1") (pin "28") (pinfunction "28_28") (pintype "passive"))
    )
    (net (code "74") (name "Net-(JP848-Pad1)") (class "Default")
      (node (ref "JP848") (pin "1") (pinfunction "1_1") (pintype "passive"))
      (node (ref "JP849") (pin "1") (pinfunction "1_1") (pintype "passive"))
      (node (ref "MC1") (pin "27") (pinfunction "27_27") (pintype "passive"))
    )
    (net (code "75") (name "Net-(JP850-Pad1)") (class "Default")
      (node (ref "JP850") (pin "1") (pinfunction "1_1") (pintype "passive"))
      (node (ref "JP851") (pin "1") (pinfunction "1_1") (pintype "passive"))
      (node (ref "MC1") (pin "26") (pinfunction "26_26") (pintype "passive"))
    )
    (net (code "76") (name "Net-(JP852-Pad1)") (class "Default")
      (node (ref "JP852") (pin "1") (pinfunction "1_1") (pintype "passive"))
      (node (ref "JP853") (pin "1") (pinfunction "1_1") (pintype "passive"))
      (node (ref "MC1") (pin "25") (pinfunction "25_25") (pintype "passive"))
    )
    (net (code "77") (name "Net-(JP854-Pad1)") (class "Default")
      (node (ref "JP854") (pin "1") (pinfunction "1_1") (pintype "passive"))
      (node (ref "JP855") (pin "1") (pinfunction "1_1") (pintype "passive"))
      (node (ref "MC1") (pin "24") (pinfunction "24_24") (pintype "passive"))
    )
    (net (code "78") (name "Net-(JP856-Pad1)") (class "Default")
      (node (ref "JP856") (pin "1") (pinfunction "1_1") (pintype "passive"))
      (node (ref "JP857") (pin "1") (pinfunction "1_1") (pintype "passive"))
      (node (ref "MC1") (pin "23") (pinfunction "23_23") (pintype "passive"))
    )
    (net (code "79") (name "Net-(JP858-Pad1)") (class "Default")
      (node (ref "JP858") (pin "1") (pinfunction "1_1") (pintype "passive"))
      (node (ref "JP859") (pin "1") (pinfunction "1_1") (pintype "passive"))
      (node (ref "MC1") (pin "22") (pinfunction "22_22") (pintype "passive"))
    )
    (net (code "80") (name "Net-(R1-A)") (class "Default")
      (node (ref "JP10") (pin "1") (pinfunction "1_1") (pintype "passive"))
      (node (ref "JP11") (pin "1") (pinfunction "1_1") (pintype "passive"))
      (node (ref "JP49") (pin "1") (pinfunction "1_1") (pintype "passive"))
      (node (ref "JP9") (pin "1") (pinfunction "1_1") (pintype "passive"))
      (node (ref "R1") (pin "1") (pinfunction "A_1") (pintype "passive"))
    )
    (net (code "81") (name "Net-(R1-E)") (class "Default")
      (node (ref "JP2") (pin "1") (pinfunction "1_1") (pintype "passive"))
      (node (ref "JP3") (pin "1") (pinfunction "1_1") (pintype "passive"))
      (node (ref "JP45") (pin "1") (pinfunction "1_1") (pintype "passive"))
      (node (ref "JP5") (pin "1") (pinfunction "1_1") (pintype "passive"))
      (node (ref "R1") (pin "3") (pinfunction "E_3") (pintype "passive"))
    )
    (net (code "82") (name "Net-(R1-S)") (class "Default")
      (node (ref "JP47") (pin "1") (pinfunction "1_1") (pintype "passive"))
      (node (ref "JP6") (pin "1") (pinfunction "1_1") (pintype "passive"))
      (node (ref "JP7") (pin "1") (pinfunction "1_1") (pintype "passive"))
      (node (ref "JP8") (pin "1") (pinfunction "1_1") (pintype "passive"))
      (node (ref "R1") (pin "2") (pinfunction "S_2") (pintype "passive"))
    )
    (net (code "83") (name "Net-(R2-A)") (class "Default")
      (node (ref "JP20") (pin "1") (pinfunction "1_1") (pintype "passive"))
      (node (ref "JP21") (pin "1") (pinfunction "1_1") (pintype "passive"))
      (node (ref "JP22") (pin "1") (pinfunction "1_1") (pintype "passive"))
      (node (ref "JP55") (pin "1") (pinfunction "1_1") (pintype "passive"))
      (node (ref "R2") (pin "1") (pinfunction "A_1") (pintype "passive"))
    )
    (net (code "84") (name "Net-(R2-E)") (class "Default")
      (node (ref "JP14") (pin "1") (pinfunction "1_1") (pintype "passive"))
      (node (ref "JP15") (pin "1") (pinfunction "1_1") (pintype "passive"))
      (node (ref "JP16") (pin "1") (pinfunction "1_1") (pintype "passive"))
      (node (ref "JP51") (pin "1") (pinfunction "1_1") (pintype "passive"))
      (node (ref "R2") (pin "3") (pinfunction "E_3") (pintype "passive"))
    )
    (net (code "85") (name "Net-(R2-S)") (class "Default")
      (node (ref "JP17") (pin "1") (pinfunction "1_1") (pintype "passive"))
      (node (ref "JP18") (pin "1") (pinfunction "1_1") (pintype "passive"))
      (node (ref "JP19") (pin "1") (pinfunction "1_1") (pintype "passive"))
      (node (ref "JP53") (pin "1") (pinfunction "1_1") (pintype "passive"))
      (node (ref "R2") (pin "2") (pinfunction "S_2") (pintype "passive"))
    )
    (net (code "86") (name "Net-(R3-A)") (class "Default")
      (node (ref "JP29") (pin "1") (pinfunction "1_1") (pintype "passive"))
      (node (ref "JP30") (pin "1") (pinfunction "1_1") (pintype "passive"))
      (node (ref "JP31") (pin "1") (pinfunction "1_1") (pintype "passive"))
      (node (ref "JP61") (pin "1") (pinfunction "1_1") (pintype "passive"))
      (node (ref "R3") (pin "1") (pinfunction "A_1") (pintype "passive"))
    )
    (net (code "87") (name "Net-(R3-E)") (class "Default")
      (node (ref "JP23") (pin "1") (pinfunction "1_1") (pintype "passive"))
      (node (ref "JP24") (pin "1") (pinfunction "1_1") (pintype "passive"))
      (node (ref "JP25") (pin "1") (pinfunction "1_1") (pintype "passive"))
      (node (ref "JP57") (pin "1") (pinfunction "1_1") (pintype "passive"))
      (node (ref "R3") (pin "3") (pinfunction "E_3") (pintype "passive"))
    )
    (net (code "88") (name "Net-(R3-S)") (class "Default")
      (node (ref "JP26") (pin "1") (pinfunction "1_1") (pintype "passive"))
      (node (ref "JP27") (pin "1") (pinfunction "1_1") (pintype "passive"))
      (node (ref "JP28") (pin "1") (pinfunction "1_1") (pintype "passive"))
      (node (ref "JP59") (pin "1") (pinfunction "1_1") (pintype "passive"))
      (node (ref "R3") (pin "2") (pinfunction "S_2") (pintype "passive"))
    )
    (net (code "89") (name "Net-(R4-A)") (class "Default")
      (node (ref "JP40") (pin "1") (pinfunction "1_1") (pintype "passive"))
      (node (ref "JP41") (pin "1") (pinfunction "1_1") (pintype "passive"))
      (node (ref "JP42") (pin "1") (pinfunction "1_1") (pintype "passive"))
      (node (ref "JP67") (pin "1") (pinfunction "1_1") (pintype "passive"))
      (node (ref "R4") (pin "1") (pinfunction "A_1") (pintype "passive"))
    )
    (net (code "90") (name "Net-(R4-E)") (class "Default")
      (node (ref "JP34") (pin "1") (pinfunction "1_1") (pintype "passive"))
      (node (ref "JP35") (pin "1") (pinfunction "1_1") (pintype "passive"))
      (node (ref "JP36") (pin "1") (pinfunction "1_1") (pintype "passive"))
      (node (ref "JP63") (pin "1") (pinfunction "1_1") (pintype "passive"))
      (node (ref "R4") (pin "3") (pinfunction "E_3") (pintype "passive"))
    )
    (net (code "91") (name "Net-(R4-S)") (class "Default")
      (node (ref "JP37") (pin "1") (pinfunction "1_1") (pintype "passive"))
      (node (ref "JP38") (pin "1") (pinfunction "1_1") (pintype "passive"))
      (node (ref "JP39") (pin "1") (pinfunction "1_1") (pintype "passive"))
      (node (ref "JP65") (pin "1") (pinfunction "1_1") (pintype "passive"))
      (node (ref "R4") (pin "2") (pinfunction "S_2") (pintype "passive"))
    )
    (net (code "92") (name "unconnected-(JP1-Pad1)") (class "Default")
      (node (ref "JP1") (pin "1") (pinfunction "1_1") (pintype "passive"))
    )
    (net (code "93") (name "unconnected-(JP4-Pad1)") (class "Default")
      (node (ref "JP4") (pin "1") (pinfunction "1_1") (pintype "passive"))
    )
    (net (code "94") (name "unconnected-(JP12-Pad1)") (class "Default")
      (node (ref "JP12") (pin "1") (pinfunction "1_1") (pintype "passive"))
    )
    (net (code "95") (name "unconnected-(JP13-Pad1)") (class "Default")
      (node (ref "JP13") (pin "1") (pinfunction "1_1") (pintype "passive"))
    )
    (net (code "96") (name "unconnected-(JP32-Pad1)") (class "Default")
      (node (ref "JP32") (pin "1") (pinfunction "1_1") (pintype "passive"))
    )
    (net (code "97") (name "unconnected-(JP33-Pad1)") (class "Default")
      (node (ref "JP33") (pin "1") (pinfunction "1_1") (pintype "passive"))
    )
    (net (code "98") (name "unconnected-(JP43-Pad1)") (class "Default")
      (node (ref "JP43") (pin "1") (pinfunction "1_1") (pintype "passive"))
    )
    (net (code "99") (name "unconnected-(JP44-Pad1)") (class "Default")
      (node (ref "JP44") (pin "1") (pinfunction "1_1") (pintype "passive"))
    )
    (net (code "100") (name "unconnected-(JP153-Pad1)") (class "Default")
      (node (ref "JP153") (pin "1") (pinfunction "1_1") (pintype "passive"))
    )
    (net (code "101") (name "unconnected-(JP191-Pad1)") (class "Default")
      (node (ref "JP191") (pin "1") (pinfunction "1_1") (pintype "passive"))
    )
    (net (code "102") (name "unconnected-(JP192-Pad1)") (class "Default")
      (node (ref "JP192") (pin "1") (pinfunction "1_1") (pintype "passive"))
    )
    (net (code "103") (name "unconnected-(JP229-Pad1)") (class "Default")
      (node (ref "JP229") (pin "1") (pinfunction "1_1") (pintype "passive"))
    )
    (net (code "104") (name "unconnected-(JP231-Pad1)") (class "Default")
      (node (ref "JP231") (pin "1") (pinfunction "1_1") (pintype "passive"))
    )
    (net (code "105") (name "unconnected-(JP266-Pad1)") (class "Default")
      (node (ref "JP266") (pin "1") (pinfunction "1_1") (pintype "passive"))
    )
    (net (code "106") (name "unconnected-(JP346-Pad1)") (class "Default")
      (node (ref "JP346") (pin "1") (pinfunction "1_1") (pintype "passive"))
    )
    (net (code "107") (name "unconnected-(JP347-Pad1)") (class "Default")
      (node (ref "JP347") (pin "1") (pinfunction "1_1") (pintype "passive"))
    )
    (net (code "108") (name "unconnected-(JP348-Pad1)") (class "Default")
      (node (ref "JP348") (pin "1") (pinfunction "1_1") (pintype "passive"))
    )
    (net (code "109") (name "unconnected-(JP349-Pad1)") (class "Default")
      (node (ref "JP349") (pin "1") (pinfunction "1_1") (pintype "passive"))
    )
    (net (code "110") (name "unconnected-(JP350-Pad1)") (class "Default")
      (node (ref "JP350") (pin "1") (pinfunction "1_1") (pintype "passive"))
    )
    (net (code "111") (name "unconnected-(JP351-Pad1)") (class "Default")
      (node (ref "JP351") (pin "1") (pinfunction "1_1") (pintype "passive"))
    )
    (net (code "112") (name "unconnected-(JP352-Pad1)") (class "Default")
      (node (ref "JP352") (pin "1") (pinfunction "1_1") (pintype "passive"))
    )
    (net (code "113") (name "unconnected-(JP353-Pad1)") (class "Default")
      (node (ref "JP353") (pin "1") (pinfunction "1_1") (pintype "passive"))
    )
    (net (code "114") (name "unconnected-(JP354-Pad1)") (class "Default")
      (node (ref "JP354") (pin "1") (pinfunction "1_1") (pintype "passive"))
    )
    (net (code "115") (name "unconnected-(JP355-Pad1)") (class "Default")
      (node (ref "JP355") (pin "1") (pinfunction "1_1") (pintype "passive"))
    )
    (net (code "116") (name "unconnected-(JP356-Pad1)") (class "Default")
      (node (ref "JP356") (pin "1") (pinfunction "1_1") (pintype "passive"))
    )
    (net (code "117") (name "unconnected-(JP357-Pad1)") (class "Default")
      (node (ref "JP357") (pin "1") (pinfunction "1_1") (pintype "passive"))
    )
    (net (code "118") (name "unconnected-(JP358-Pad1)") (class "Default")
      (node (ref "JP358") (pin "1") (pinfunction "1_1") (pintype "passive"))
    )
    (net (code "119") (name "unconnected-(JP359-Pad1)") (class "Default")
      (node (ref "JP359") (pin "1") (pinfunction "1_1") (pintype "passive"))
    )
    (net (code "120") (name "unconnected-(JP360-Pad1)") (class "Default")
      (node (ref "JP360") (pin "1") (pinfunction "1_1") (pintype "passive"))
    )
    (net (code "121") (name "unconnected-(JP361-Pad1)") (class "Default")
      (node (ref "JP361") (pin "1") (pinfunction "1_1") (pintype "passive"))
    )
    (net (code "122") (name "unconnected-(JP362-Pad1)") (class "Default")
      (node (ref "JP362") (pin "1") (pinfunction "1_1") (pintype "passive"))
    )
    (net (code "123") (name "unconnected-(JP363-Pad1)") (class "Default")
      (node (ref "JP363") (pin "1") (pinfunction "1_1") (pintype "passive"))
    )
    (net (code "124") (name "unconnected-(JP364-Pad1)") (class "Default")
      (node (ref "JP364") (pin "1") (pinfunction "1_1") (pintype "passive"))
    )
    (net (code "125") (name "unconnected-(JP365-Pad1)") (class "Default")
      (node (ref "JP365") (pin "1") (pinfunction "1_1") (pintype "passive"))
    )
    (net (code "126") (name "unconnected-(JP366-Pad1)") (class "Default")
      (node (ref "JP366") (pin "1") (pinfunction "1_1") (pintype "passive"))
    )
    (net (code "127") (name "unconnected-(JP367-Pad1)") (class "Default")
      (node (ref "JP367") (pin "1") (pinfunction "1_1") (pintype "passive"))
    )
    (net (code "128") (name "unconnected-(JP368-Pad1)") (class "Default")
      (node (ref "JP368") (pin "1") (pinfunction "1_1") (pintype "passive"))
    )
    (net (code "129") (name "unconnected-(JP369-Pad1)") (class "Default")
      (node (ref "JP369") (pin "1") (pinfunction "1_1") (pintype "passive"))
    )
    (net (code "130") (name "unconnected-(JP370-Pad1)") (class "Default")
      (node (ref "JP370") (pin "1") (pinfunction "1_1") (pintype "passive"))
    )
    (net (code "131") (name "unconnected-(JP371-Pad1)") (class "Default")
      (node (ref "JP371") (pin "1") (pinfunction "1_1") (pintype "passive"))
    )
    (net (code "132") (name "unconnected-(JP372-Pad1)") (class "Default")
      (node (ref "JP372") (pin "1") (pinfunction "1_1") (pintype "passive"))
    )
    (net (code "133") (name "unconnected-(JP373-Pad1)") (class "Default")
      (node (ref "JP373") (pin "1") (pinfunction "1_1") (pintype "passive"))
    )
    (net (code "134") (name "unconnected-(JP374-Pad1)") (class "Default")
      (node (ref "JP374") (pin "1") (pinfunction "1_1") (pintype "passive"))
    )
    (net (code "135") (name "unconnected-(JP375-Pad1)") (class "Default")
      (node (ref "JP375") (pin "1") (pinfunction "1_1") (pintype "passive"))
    )
    (net (code "136") (name "unconnected-(JP376-Pad1)") (class "Default")
      (node (ref "JP376") (pin "1") (pinfunction "1_1") (pintype "passive"))
    )
    (net (code "137") (name "unconnected-(JP377-Pad1)") (class "Default")
      (node (ref "JP377") (pin "1") (pinfunction "1_1") (pintype "passive"))
    )
    (net (code "138") (name "unconnected-(JP378-Pad1)") (class "Default")
      (node (ref "JP378") (pin "1") (pinfunction "1_1") (pintype "passive"))
    )
    (net (code "139") (name "unconnected-(JP379-Pad1)") (class "Default")
      (node (ref "JP379") (pin "1") (pinfunction "1_1") (pintype "passive"))
    )
    (net (code "140") (name "unconnected-(JP380-Pad1)") (class "Default")
      (node (ref "JP380") (pin "1") (pinfunction "1_1") (pintype "passive"))
    )
    (net (code "141") (name "unconnected-(JP381-Pad1)") (class "Default")
      (node (ref "JP381") (pin "1") (pinfunction "1_1") (pintype "passive"))
    )
    (net (code "142") (name "unconnected-(JP382-Pad1)") (class "Default")
      (node (ref "JP382") (pin "1") (pinfunction "1_1") (pintype "passive"))
    )
    (net (code "143") (name "unconnected-(JP383-Pad1)") (class "Default")
      (node (ref "JP383") (pin "1") (pinfunction "1_1") (pintype "passive"))
    )
    (net (code "144") (name "unconnected-(JP384-Pad1)") (class "Default")
      (node (ref "JP384") (pin "1") (pinfunction "1_1") (pintype "passive"))
    )
    (net (code "145") (name "unconnected-(JP385-Pad1)") (class "Default")
      (node (ref "JP385") (pin "1") (pinfunction "1_1") (pintype "passive"))
    )
    (net (code "146") (name "unconnected-(JP386-Pad1)") (class "Default")
      (node (ref "JP386") (pin "1") (pinfunction "1_1") (pintype "passive"))
    )
    (net (code "147") (name "unconnected-(JP387-Pad1)") (class "Default")
      (node (ref "JP387") (pin "1") (pinfunction "1_1") (pintype "passive"))
    )
    (net (code "148") (name "unconnected-(JP388-Pad1)") (class "Default")
      (node (ref "JP388") (pin "1") (pinfunction "1_1") (pintype "passive"))
    )
    (net (code "149") (name "unconnected-(JP389-Pad1)") (class "Default")
      (node (ref "JP389") (pin "1") (pinfunction "1_1") (pintype "passive"))
    )
    (net (code "150") (name "unconnected-(JP390-Pad1)") (class "Default")
      (node (ref "JP390") (pin "1") (pinfunction "1_1") (pintype "passive"))
    )
    (net (code "151") (name "unconnected-(JP391-Pad1)") (class "Default")
      (node (ref "JP391") (pin "1") (pinfunction "1_1") (pintype "passive"))
    )
    (net (code "152") (name "unconnected-(JP392-Pad1)") (class "Default")
      (node (ref "JP392") (pin "1") (pinfunction "1_1") (pintype "passive"))
    )
    (net (code "153") (name "unconnected-(JP393-Pad1)") (class "Default")
      (node (ref "JP393") (pin "1") (pinfunction "1_1") (pintype "passive"))
    )
    (net (code "154") (name "unconnected-(JP394-Pad1)") (class "Default")
      (node (ref "JP394") (pin "1") (pinfunction "1_1") (pintype "passive"))
    )
    (net (code "155") (name "unconnected-(JP395-Pad1)") (class "Default")
      (node (ref "JP395") (pin "1") (pinfunction "1_1") (pintype "passive"))
    )
    (net (code "156") (name "unconnected-(JP396-Pad1)") (class "Default")
      (node (ref "JP396") (pin "1") (pinfunction "1_1") (pintype "passive"))
    )
    (net (code "157") (name "unconnected-(JP397-Pad1)") (class "Default")
      (node (ref "JP397") (pin "1") (pinfunction "1_1") (pintype "passive"))
    )
    (net (code "158") (name "unconnected-(JP398-Pad1)") (class "Default")
      (node (ref "JP398") (pin "1") (pinfunction "1_1") (pintype "passive"))
    )
    (net (code "159") (name "unconnected-(JP399-Pad1)") (class "Default")
      (node (ref "JP399") (pin "1") (pinfunction "1_1") (pintype "passive"))
    )
    (net (code "160") (name "unconnected-(JP400-Pad1)") (class "Default")
      (node (ref "JP400") (pin "1") (pinfunction "1_1") (pintype "passive"))
    )
    (net (code "161") (name "unconnected-(JP401-Pad1)") (class "Default")
      (node (ref "JP401") (pin "1") (pinfunction "1_1") (pintype "passive"))
    )
    (net (code "162") (name "unconnected-(JP402-Pad1)") (class "Default")
      (node (ref "JP402") (pin "1") (pinfunction "1_1") (pintype "passive"))
    )
    (net (code "163") (name "unconnected-(JP403-Pad1)") (class "Default")
      (node (ref "JP403") (pin "1") (pinfunction "1_1") (pintype "passive"))
    )
    (net (code "164") (name "unconnected-(JP404-Pad1)") (class "Default")
      (node (ref "JP404") (pin "1") (pinfunction "1_1") (pintype "passive"))
    )
    (net (code "165") (name "unconnected-(JP405-Pad1)") (class "Default")
      (node (ref "JP405") (pin "1") (pinfunction "1_1") (pintype "passive"))
    )
    (net (code "166") (name "unconnected-(JP406-Pad1)") (class "Default")
      (node (ref "JP406") (pin "1") (pinfunction "1_1") (pintype "passive"))
    )
    (net (code "167") (name "unconnected-(JP407-Pad1)") (class "Default")
      (node (ref "JP407") (pin "1") (pinfunction "1_1") (pintype "passive"))
    )
    (net (code "168") (name "unconnected-(JP408-Pad1)") (class "Default")
      (node (ref "JP408") (pin "1") (pinfunction "1_1") (pintype "passive"))
    )
    (net (code "169") (name "unconnected-(JP409-Pad1)") (class "Default")
      (node (ref "JP409") (pin "1") (pinfunction "1_1") (pintype "passive"))
    )
    (net (code "170") (name "unconnected-(JP410-Pad1)") (class "Default")
      (node (ref "JP410") (pin "1") (pinfunction "1_1") (pintype "passive"))
    )
    (net (code "171") (name "unconnected-(JP411-Pad1)") (class "Default")
      (node (ref "JP411") (pin "1") (pinfunction "1_1") (pintype "passive"))
    )
    (net (code "172") (name "unconnected-(JP412-Pad1)") (class "Default")
      (node (ref "JP412") (pin "1") (pinfunction "1_1") (pintype "passive"))
    )
    (net (code "173") (name "unconnected-(JP413-Pad1)") (class "Default")
      (node (ref "JP413") (pin "1") (pinfunction "1_1") (pintype "passive"))
    )
    (net (code "174") (name "unconnected-(JP414-Pad1)") (class "Default")
      (node (ref "JP414") (pin "1") (pinfunction "1_1") (pintype "passive"))
    )
    (net (code "175") (name "unconnected-(JP415-Pad1)") (class "Default")
      (node (ref "JP415") (pin "1") (pinfunction "1_1") (pintype "passive"))
    )
    (net (code "176") (name "unconnected-(JP416-Pad1)") (class "Default")
      (node (ref "JP416") (pin "1") (pinfunction "1_1") (pintype "passive"))
    )
    (net (code "177") (name "unconnected-(JP417-Pad1)") (class "Default")
      (node (ref "JP417") (pin "1") (pinfunction "1_1") (pintype "passive"))
    )
    (net (code "178") (name "unconnected-(JP418-Pad1)") (class "Default")
      (node (ref "JP418") (pin "1") (pinfunction "1_1") (pintype "passive"))
    )
    (net (code "179") (name "unconnected-(JP419-Pad1)") (class "Default")
      (node (ref "JP419") (pin "1") (pinfunction "1_1") (pintype "passive"))
    )
    (net (code "180") (name "unconnected-(JP420-Pad1)") (class "Default")
      (node (ref "JP420") (pin "1") (pinfunction "1_1") (pintype "passive"))
    )
    (net (code "181") (name "unconnected-(JP421-Pad1)") (class "Default")
      (node (ref "JP421") (pin "1") (pinfunction "1_1") (pintype "passive"))
    )
    (net (code "182") (name "unconnected-(JP422-Pad1)") (class "Default")
      (node (ref "JP422") (pin "1") (pinfunction "1_1") (pintype "passive"))
    )
    (net (code "183") (name "unconnected-(JP423-Pad1)") (class "Default")
      (node (ref "JP423") (pin "1") (pinfunction "1_1") (pintype "passive"))
    )
    (net (code "184") (name "unconnected-(JP424-Pad1)") (class "Default")
      (node (ref "JP424") (pin "1") (pinfunction "1_1") (pintype "passive"))
    )
    (net (code "185") (name "unconnected-(JP425-Pad1)") (class "Default")
      (node (ref "JP425") (pin "1") (pinfunction "1_1") (pintype "passive"))
    )
    (net (code "186") (name "unconnected-(JP426-Pad1)") (class "Default")
      (node (ref "JP426") (pin "1") (pinfunction "1_1") (pintype "passive"))
    )
    (net (code "187") (name "unconnected-(JP427-Pad1)") (class "Default")
      (node (ref "JP427") (pin "1") (pinfunction "1_1") (pintype "passive"))
    )
    (net (code "188") (name "unconnected-(JP428-Pad1)") (class "Default")
      (node (ref "JP428") (pin "1") (pinfunction "1_1") (pintype "passive"))
    )
    (net (code "189") (name "unconnected-(JP429-Pad1)") (class "Default")
      (node (ref "JP429") (pin "1") (pinfunction "1_1") (pintype "passive"))
    )
    (net (code "190") (name "unconnected-(JP430-Pad1)") (class "Default")
      (node (ref "JP430") (pin "1") (pinfunction "1_1") (pintype "passive"))
    )
    (net (code "191") (name "unconnected-(JP431-Pad1)") (class "Default")
      (node (ref "JP431") (pin "1") (pinfunction "1_1") (pintype "passive"))
    )
    (net (code "192") (name "unconnected-(JP432-Pad1)") (class "Default")
      (node (ref "JP432") (pin "1") (pinfunction "1_1") (pintype "passive"))
    )
    (net (code "193") (name "unconnected-(JP433-Pad1)") (class "Default")
      (node (ref "JP433") (pin "1") (pinfunction "1_1") (pintype "passive"))
    )
    (net (code "194") (name "unconnected-(JP434-Pad1)") (class "Default")
      (node (ref "JP434") (pin "1") (pinfunction "1_1") (pintype "passive"))
    )
    (net (code "195") (name "unconnected-(JP435-Pad1)") (class "Default")
      (node (ref "JP435") (pin "1") (pinfunction "1_1") (pintype "passive"))
    )
    (net (code "196") (name "unconnected-(JP436-Pad1)") (class "Default")
      (node (ref "JP436") (pin "1") (pinfunction "1_1") (pintype "passive"))
    )
    (net (code "197") (name "unconnected-(JP437-Pad1)") (class "Default")
      (node (ref "JP437") (pin "1") (pinfunction "1_1") (pintype "passive"))
    )
    (net (code "198") (name "unconnected-(JP438-Pad1)") (class "Default")
      (node (ref "JP438") (pin "1") (pinfunction "1_1") (pintype "passive"))
    )
    (net (code "199") (name "unconnected-(JP439-Pad1)") (class "Default")
      (node (ref "JP439") (pin "1") (pinfunction "1_1") (pintype "passive"))
    )
    (net (code "200") (name "unconnected-(JP440-Pad1)") (class "Default")
      (node (ref "JP440") (pin "1") (pinfunction "1_1") (pintype "passive"))
    )
    (net (code "201") (name "unconnected-(JP441-Pad1)") (class "Default")
      (node (ref "JP441") (pin "1") (pinfunction "1_1") (pintype "passive"))
    )
    (net (code "202") (name "unconnected-(JP442-Pad1)") (class "Default")
      (node (ref "JP442") (pin "1") (pinfunction "1_1") (pintype "passive"))
    )
    (net (code "203") (name "unconnected-(JP443-Pad1)") (class "Default")
      (node (ref "JP443") (pin "1") (pinfunction "1_1") (pintype "passive"))
    )
    (net (code "204") (name "unconnected-(JP444-Pad1)") (class "Default")
      (node (ref "JP444") (pin "1") (pinfunction "1_1") (pintype "passive"))
    )
    (net (code "205") (name "unconnected-(JP445-Pad1)") (class "Default")
      (node (ref "JP445") (pin "1") (pinfunction "1_1") (pintype "passive"))
    )
    (net (code "206") (name "unconnected-(JP446-Pad1)") (class "Default")
      (node (ref "JP446") (pin "1") (pinfunction "1_1") (pintype "passive"))
    )
    (net (code "207") (name "unconnected-(JP447-Pad1)") (class "Default")
      (node (ref "JP447") (pin "1") (pinfunction "1_1") (pintype "passive"))
    )
    (net (code "208") (name "unconnected-(JP448-Pad1)") (class "Default")
      (node (ref "JP448") (pin "1") (pinfunction "1_1") (pintype "passive"))
    )
    (net (code "209") (name "unconnected-(JP449-Pad1)") (class "Default")
      (node (ref "JP449") (pin "1") (pinfunction "1_1") (pintype "passive"))
    )
    (net (code "210") (name "unconnected-(JP450-Pad1)") (class "Default")
      (node (ref "JP450") (pin "1") (pinfunction "1_1") (pintype "passive"))
    )
    (net (code "211") (name "unconnected-(JP451-Pad1)") (class "Default")
      (node (ref "JP451") (pin "1") (pinfunction "1_1") (pintype "passive"))
    )
    (net (code "212") (name "unconnected-(JP452-Pad1)") (class "Default")
      (node (ref "JP452") (pin "1") (pinfunction "1_1") (pintype "passive"))
    )
    (net (code "213") (name "unconnected-(JP453-Pad1)") (class "Default")
      (node (ref "JP453") (pin "1") (pinfunction "1_1") (pintype "passive"))
    )
    (net (code "214") (name "unconnected-(JP454-Pad1)") (class "Default")
      (node (ref "JP454") (pin "1") (pinfunction "1_1") (pintype "passive"))
    )
    (net (code "215") (name "unconnected-(JP455-Pad1)") (class "Default")
      (node (ref "JP455") (pin "1") (pinfunction "1_1") (pintype "passive"))
    )
    (net (code "216") (name "unconnected-(JP456-Pad1)") (class "Default")
      (node (ref "JP456") (pin "1") (pinfunction "1_1") (pintype "passive"))
    )
    (net (code "217") (name "unconnected-(JP457-Pad1)") (class "Default")
      (node (ref "JP457") (pin "1") (pinfunction "1_1") (pintype "passive"))
    )
    (net (code "218") (name "unconnected-(JP458-Pad1)") (class "Default")
      (node (ref "JP458") (pin "1") (pinfunction "1_1") (pintype "passive"))
    )
    (net (code "219") (name "unconnected-(JP459-Pad1)") (class "Default")
      (node (ref "JP459") (pin "1") (pinfunction "1_1") (pintype "passive"))
    )
    (net (code "220") (name "unconnected-(JP460-Pad1)") (class "Default")
      (node (ref "JP460") (pin "1") (pinfunction "1_1") (pintype "passive"))
    )
    (net (code "221") (name "unconnected-(JP461-Pad1)") (class "Default")
      (node (ref "JP461") (pin "1") (pinfunction "1_1") (pintype "passive"))
    )
    (net (code "222") (name "unconnected-(JP462-Pad1)") (class "Default")
      (node (ref "JP462") (pin "1") (pinfunction "1_1") (pintype "passive"))
    )
    (net (code "223") (name "unconnected-(JP463-Pad1)") (class "Default")
      (node (ref "JP463") (pin "1") (pinfunction "1_1") (pintype "passive"))
    )
    (net (code "224") (name "unconnected-(JP464-Pad1)") (class "Default")
      (node (ref "JP464") (pin "1") (pinfunction "1_1") (pintype "passive"))
    )
    (net (code "225") (name "unconnected-(JP465-Pad1)") (class "Default")
      (node (ref "JP465") (pin "1") (pinfunction "1_1") (pintype "passive"))
    )
    (net (code "226") (name "unconnected-(JP466-Pad1)") (class "Default")
      (node (ref "JP466") (pin "1") (pinfunction "1_1") (pintype "passive"))
    )
    (net (code "227") (name "unconnected-(JP467-Pad1)") (class "Default")
      (node (ref "JP467") (pin "1") (pinfunction "1_1") (pintype "passive"))
    )
    (net (code "228") (name "unconnected-(JP468-Pad1)") (class "Default")
      (node (ref "JP468") (pin "1") (pinfunction "1_1") (pintype "passive"))
    )
    (net (code "229") (name "unconnected-(JP469-Pad1)") (class "Default")
      (node (ref "JP469") (pin "1") (pinfunction "1_1") (pintype "passive"))
    )
    (net (code "230") (name "unconnected-(JP470-Pad1)") (class "Default")
      (node (ref "JP470") (pin "1") (pinfunction "1_1") (pintype "passive"))
    )
    (net (code "231") (name "unconnected-(JP471-Pad1)") (class "Default")
      (node (ref "JP471") (pin "1") (pinfunction "1_1") (pintype "passive"))
    )
    (net (code "232") (name "unconnected-(JP472-Pad1)") (class "Default")
      (node (ref "JP472") (pin "1") (pinfunction "1_1") (pintype "passive"))
    )
    (net (code "233") (name "unconnected-(JP473-Pad1)") (class "Default")
      (node (ref "JP473") (pin "1") (pinfunction "1_1") (pintype "passive"))
    )
    (net (code "234") (name "unconnected-(JP474-Pad1)") (class "Default")
      (node (ref "JP474") (pin "1") (pinfunction "1_1") (pintype "passive"))
    )
    (net (code "235") (name "unconnected-(JP475-Pad1)") (class "Default")
      (node (ref "JP475") (pin "1") (pinfunction "1_1") (pintype "passive"))
    )
    (net (code "236") (name "unconnected-(JP476-Pad1)") (class "Default")
      (node (ref "JP476") (pin "1") (pinfunction "1_1") (pintype "passive"))
    )
    (net (code "237") (name "unconnected-(JP477-Pad1)") (class "Default")
      (node (ref "JP477") (pin "1") (pinfunction "1_1") (pintype "passive"))
    )
    (net (code "238") (name "unconnected-(JP478-Pad1)") (class "Default")
      (node (ref "JP478") (pin "1") (pinfunction "1_1") (pintype "passive"))
    )
    (net (code "239") (name "unconnected-(JP479-Pad1)") (class "Default")
      (node (ref "JP479") (pin "1") (pinfunction "1_1") (pintype "passive"))
    )
    (net (code "240") (name "unconnected-(JP480-Pad1)") (class "Default")
      (node (ref "JP480") (pin "1") (pinfunction "1_1") (pintype "passive"))
    )
    (net (code "241") (name "unconnected-(JP481-Pad1)") (class "Default")
      (node (ref "JP481") (pin "1") (pinfunction "1_1") (pintype "passive"))
    )
    (net (code "242") (name "unconnected-(JP482-Pad1)") (class "Default")
      (node (ref "JP482") (pin "1") (pinfunction "1_1") (pintype "passive"))
    )
    (net (code "243") (name "unconnected-(JP483-Pad1)") (class "Default")
      (node (ref "JP483") (pin "1") (pinfunction "1_1") (pintype "passive"))
    )
    (net (code "244") (name "unconnected-(JP484-Pad1)") (class "Default")
      (node (ref "JP484") (pin "1") (pinfunction "1_1") (pintype "passive"))
    )
    (net (code "245") (name "unconnected-(JP485-Pad1)") (class "Default")
      (node (ref "JP485") (pin "1") (pinfunction "1_1") (pintype "passive"))
    )
    (net (code "246") (name "unconnected-(JP486-Pad1)") (class "Default")
      (node (ref "JP486") (pin "1") (pinfunction "1_1") (pintype "passive"))
    )
    (net (code "247") (name "unconnected-(JP487-Pad1)") (class "Default")
      (node (ref "JP487") (pin "1") (pinfunction "1_1") (pintype "passive"))
    )
    (net (code "248") (name "unconnected-(JP488-Pad1)") (class "Default")
      (node (ref "JP488") (pin "1") (pinfunction "1_1") (pintype "passive"))
    )
    (net (code "249") (name "unconnected-(JP489-Pad1)") (class "Default")
      (node (ref "JP489") (pin "1") (pinfunction "1_1") (pintype "passive"))
    )
    (net (code "250") (name "unconnected-(JP490-Pad1)") (class "Default")
      (node (ref "JP490") (pin "1") (pinfunction "1_1") (pintype "passive"))
    )
    (net (code "251") (name "unconnected-(JP491-Pad1)") (class "Default")
      (node (ref "JP491") (pin "1") (pinfunction "1_1") (pintype "passive"))
    )
    (net (code "252") (name "unconnected-(JP492-Pad1)") (class "Default")
      (node (ref "JP492") (pin "1") (pinfunction "1_1") (pintype "passive"))
    )
    (net (code "253") (name "unconnected-(JP493-Pad1)") (class "Default")
      (node (ref "JP493") (pin "1") (pinfunction "1_1") (pintype "passive"))
    )
    (net (code "254") (name "unconnected-(JP494-Pad1)") (class "Default")
      (node (ref "JP494") (pin "1") (pinfunction "1_1") (pintype "passive"))
    )
    (net (code "255") (name "unconnected-(JP495-Pad1)") (class "Default")
      (node (ref "JP495") (pin "1") (pinfunction "1_1") (pintype "passive"))
    )
    (net (code "256") (name "unconnected-(JP496-Pad1)") (class "Default")
      (node (ref "JP496") (pin "1") (pinfunction "1_1") (pintype "passive"))
    )
    (net (code "257") (name "unconnected-(JP497-Pad1)") (class "Default")
      (node (ref "JP497") (pin "1") (pinfunction "1_1") (pintype "passive"))
    )
    (net (code "258") (name "unconnected-(JP498-Pad1)") (class "Default")
      (node (ref "JP498") (pin "1") (pinfunction "1_1") (pintype "passive"))
    )
    (net (code "259") (name "unconnected-(JP499-Pad1)") (class "Default")
      (node (ref "JP499") (pin "1") (pinfunction "1_1") (pintype "passive"))
    )
    (net (code "260") (name "unconnected-(JP500-Pad1)") (class "Default")
      (node (ref "JP500") (pin "1") (pinfunction "1_1") (pintype "passive"))
    )
    (net (code "261") (name "unconnected-(JP501-Pad1)") (class "Default")
      (node (ref "JP501") (pin "1") (pinfunction "1_1") (pintype "passive"))
    )
    (net (code "262") (name "unconnected-(JP502-Pad1)") (class "Default")
      (node (ref "JP502") (pin "1") (pinfunction "1_1") (pintype "passive"))
    )
    (net (code "263") (name "unconnected-(JP503-Pad1)") (class "Default")
      (node (ref "JP503") (pin "1") (pinfunction "1_1") (pintype "passive"))
    )
    (net (code "264") (name "unconnected-(JP504-Pad1)") (class "Default")
      (node (ref "JP504") (pin "1") (pinfunction "1_1") (pintype "passive"))
    )
    (net (code "265") (name "unconnected-(JP505-Pad1)") (class "Default")
      (node (ref "JP505") (pin "1") (pinfunction "1_1") (pintype "passive"))
    )
    (net (code "266") (name "unconnected-(JP506-Pad1)") (class "Default")
      (node (ref "JP506") (pin "1") (pinfunction "1_1") (pintype "passive"))
    )
    (net (code "267") (name "unconnected-(JP507-Pad1)") (class "Default")
      (node (ref "JP507") (pin "1") (pinfunction "1_1") (pintype "passive"))
    )
    (net (code "268") (name "unconnected-(JP508-Pad1)") (class "Default")
      (node (ref "JP508") (pin "1") (pinfunction "1_1") (pintype "passive"))
    )
    (net (code "269") (name "unconnected-(JP509-Pad1)") (class "Default")
      (node (ref "JP509") (pin "1") (pinfunction "1_1") (pintype "passive"))
    )
    (net (code "270") (name "unconnected-(JP510-Pad1)") (class "Default")
      (node (ref "JP510") (pin "1") (pinfunction "1_1") (pintype "passive"))
    )
    (net (code "271") (name "unconnected-(JP511-Pad1)") (class "Default")
      (node (ref "JP511") (pin "1") (pinfunction "1_1") (pintype "passive"))
    )
    (net (code "272") (name "unconnected-(JP512-Pad1)") (class "Default")
      (node (ref "JP512") (pin "1") (pinfunction "1_1") (pintype "passive"))
    )
    (net (code "273") (name "unconnected-(JP513-Pad1)") (class "Default")
      (node (ref "JP513") (pin "1") (pinfunction "1_1") (pintype "passive"))
    )
    (net (code "274") (name "unconnected-(JP514-Pad1)") (class "Default")
      (node (ref "JP514") (pin "1") (pinfunction "1_1") (pintype "passive"))
    )
    (net (code "275") (name "unconnected-(JP515-Pad1)") (class "Default")
      (node (ref "JP515") (pin "1") (pinfunction "1_1") (pintype "passive"))
    )
    (net (code "276") (name "unconnected-(JP516-Pad1)") (class "Default")
      (node (ref "JP516") (pin "1") (pinfunction "1_1") (pintype "passive"))
    )
    (net (code "277") (name "unconnected-(JP517-Pad1)") (class "Default")
      (node (ref "JP517") (pin "1") (pinfunction "1_1") (pintype "passive"))
    )
    (net (code "278") (name "unconnected-(JP518-Pad1)") (class "Default")
      (node (ref "JP518") (pin "1") (pinfunction "1_1") (pintype "passive"))
    )
    (net (code "279") (name "unconnected-(JP519-Pad1)") (class "Default")
      (node (ref "JP519") (pin "1") (pinfunction "1_1") (pintype "passive"))
    )
    (net (code "280") (name "unconnected-(JP520-Pad1)") (class "Default")
      (node (ref "JP520") (pin "1") (pinfunction "1_1") (pintype "passive"))
    )
    (net (code "281") (name "unconnected-(JP521-Pad1)") (class "Default")
      (node (ref "JP521") (pin "1") (pinfunction "1_1") (pintype "passive"))
    )
    (net (code "282") (name "unconnected-(JP522-Pad1)") (class "Default")
      (node (ref "JP522") (pin "1") (pinfunction "1_1") (pintype "passive"))
    )
    (net (code "283") (name "unconnected-(JP523-Pad1)") (class "Default")
      (node (ref "JP523") (pin "1") (pinfunction "1_1") (pintype "passive"))
    )
    (net (code "284") (name "unconnected-(JP524-Pad1)") (class "Default")
      (node (ref "JP524") (pin "1") (pinfunction "1_1") (pintype "passive"))
    )
    (net (code "285") (name "unconnected-(JP525-Pad1)") (class "Default")
      (node (ref "JP525") (pin "1") (pinfunction "1_1") (pintype "passive"))
    )
    (net (code "286") (name "unconnected-(JP526-Pad1)") (class "Default")
      (node (ref "JP526") (pin "1") (pinfunction "1_1") (pintype "passive"))
    )
    (net (code "287") (name "unconnected-(JP527-Pad1)") (class "Default")
      (node (ref "JP527") (pin "1") (pinfunction "1_1") (pintype "passive"))
    )
    (net (code "288") (name "unconnected-(JP528-Pad1)") (class "Default")
      (node (ref "JP528") (pin "1") (pinfunction "1_1") (pintype "passive"))
    )
    (net (code "289") (name "unconnected-(JP529-Pad1)") (class "Default")
      (node (ref "JP529") (pin "1") (pinfunction "1_1") (pintype "passive"))
    )
    (net (code "290") (name "unconnected-(JP530-Pad1)") (class "Default")
      (node (ref "JP530") (pin "1") (pinfunction "1_1") (pintype "passive"))
    )
    (net (code "291") (name "unconnected-(JP531-Pad1)") (class "Default")
      (node (ref "JP531") (pin "1") (pinfunction "1_1") (pintype "passive"))
    )
    (net (code "292") (name "unconnected-(JP532-Pad1)") (class "Default")
      (node (ref "JP532") (pin "1") (pinfunction "1_1") (pintype "passive"))
    )
    (net (code "293") (name "unconnected-(JP533-Pad1)") (class "Default")
      (node (ref "JP533") (pin "1") (pinfunction "1_1") (pintype "passive"))
    )
    (net (code "294") (name "unconnected-(JP534-Pad1)") (class "Default")
      (node (ref "JP534") (pin "1") (pinfunction "1_1") (pintype "passive"))
    )
    (net (code "295") (name "unconnected-(JP535-Pad1)") (class "Default")
      (node (ref "JP535") (pin "1") (pinfunction "1_1") (pintype "passive"))
    )
    (net (code "296") (name "unconnected-(JP536-Pad1)") (class "Default")
      (node (ref "JP536") (pin "1") (pinfunction "1_1") (pintype "passive"))
    )
    (net (code "297") (name "unconnected-(JP537-Pad1)") (class "Default")
      (node (ref "JP537") (pin "1") (pinfunction "1_1") (pintype "passive"))
    )
    (net (code "298") (name "unconnected-(JP538-Pad1)") (class "Default")
      (node (ref "JP538") (pin "1") (pinfunction "1_1") (pintype "passive"))
    )
    (net (code "299") (name "unconnected-(JP539-Pad1)") (class "Default")
      (node (ref "JP539") (pin "1") (pinfunction "1_1") (pintype "passive"))
    )
    (net (code "300") (name "unconnected-(JP540-Pad1)") (class "Default")
      (node (ref "JP540") (pin "1") (pinfunction "1_1") (pintype "passive"))
    )
    (net (code "301") (name "unconnected-(JP541-Pad1)") (class "Default")
      (node (ref "JP541") (pin "1") (pinfunction "1_1") (pintype "passive"))
    )
    (net (code "302") (name "unconnected-(JP542-Pad1)") (class "Default")
      (node (ref "JP542") (pin "1") (pinfunction "1_1") (pintype "passive"))
    )
    (net (code "303") (name "unconnected-(JP543-Pad1)") (class "Default")
      (node (ref "JP543") (pin "1") (pinfunction "1_1") (pintype "passive"))
    )
    (net (code "304") (name "unconnected-(JP544-Pad1)") (class "Default")
      (node (ref "JP544") (pin "1") (pinfunction "1_1") (pintype "passive"))
    )
    (net (code "305") (name "unconnected-(JP545-Pad1)") (class "Default")
      (node (ref "JP545") (pin "1") (pinfunction "1_1") (pintype "passive"))
    )
    (net (code "306") (name "unconnected-(JP546-Pad1)") (class "Default")
      (node (ref "JP546") (pin "1") (pinfunction "1_1") (pintype "passive"))
    )
    (net (code "307") (name "unconnected-(JP547-Pad1)") (class "Default")
      (node (ref "JP547") (pin "1") (pinfunction "1_1") (pintype "passive"))
    )
    (net (code "308") (name "unconnected-(JP548-Pad1)") (class "Default")
      (node (ref "JP548") (pin "1") (pinfunction "1_1") (pintype "passive"))
    )
    (net (code "309") (name "unconnected-(JP549-Pad1)") (class "Default")
      (node (ref "JP549") (pin "1") (pinfunction "1_1") (pintype "passive"))
    )
    (net (code "310") (name "unconnected-(JP550-Pad1)") (class "Default")
      (node (ref "JP550") (pin "1") (pinfunction "1_1") (pintype "passive"))
    )
    (net (code "311") (name "unconnected-(JP551-Pad1)") (class "Default")
      (node (ref "JP551") (pin "1") (pinfunction "1_1") (pintype "passive"))
    )
    (net (code "312") (name "unconnected-(JP552-Pad1)") (class "Default")
      (node (ref "JP552") (pin "1") (pinfunction "1_1") (pintype "passive"))
    )
    (net (code "313") (name "unconnected-(JP553-Pad1)") (class "Default")
      (node (ref "JP553") (pin "1") (pinfunction "1_1") (pintype "passive"))
    )
    (net (code "314") (name "unconnected-(JP554-Pad1)") (class "Default")
      (node (ref "JP554") (pin "1") (pinfunction "1_1") (pintype "passive"))
    )
    (net (code "315") (name "unconnected-(JP555-Pad1)") (class "Default")
      (node (ref "JP555") (pin "1") (pinfunction "1_1") (pintype "passive"))
    )
    (net (code "316") (name "unconnected-(JP556-Pad1)") (class "Default")
      (node (ref "JP556") (pin "1") (pinfunction "1_1") (pintype "passive"))
    )
    (net (code "317") (name "unconnected-(JP557-Pad1)") (class "Default")
      (node (ref "JP557") (pin "1") (pinfunction "1_1") (pintype "passive"))
    )
    (net (code "318") (name "unconnected-(JP558-Pad1)") (class "Default")
      (node (ref "JP558") (pin "1") (pinfunction "1_1") (pintype "passive"))
    )
    (net (code "319") (name "unconnected-(JP559-Pad1)") (class "Default")
      (node (ref "JP559") (pin "1") (pinfunction "1_1") (pintype "passive"))
    )
    (net (code "320") (name "unconnected-(JP560-Pad1)") (class "Default")
      (node (ref "JP560") (pin "1") (pinfunction "1_1") (pintype "passive"))
    )
    (net (code "321") (name "unconnected-(JP561-Pad1)") (class "Default")
      (node (ref "JP561") (pin "1") (pinfunction "1_1") (pintype "passive"))
    )
    (net (code "322") (name "unconnected-(JP562-Pad1)") (class "Default")
      (node (ref "JP562") (pin "1") (pinfunction "1_1") (pintype "passive"))
    )
    (net (code "323") (name "unconnected-(JP563-Pad1)") (class "Default")
      (node (ref "JP563") (pin "1") (pinfunction "1_1") (pintype "passive"))
    )
    (net (code "324") (name "unconnected-(JP564-Pad1)") (class "Default")
      (node (ref "JP564") (pin "1") (pinfunction "1_1") (pintype "passive"))
    )
    (net (code "325") (name "unconnected-(JP565-Pad1)") (class "Default")
      (node (ref "JP565") (pin "1") (pinfunction "1_1") (pintype "passive"))
    )
    (net (code "326") (name "unconnected-(JP566-Pad1)") (class "Default")
      (node (ref "JP566") (pin "1") (pinfunction "1_1") (pintype "passive"))
    )
    (net (code "327") (name "unconnected-(JP567-Pad1)") (class "Default")
      (node (ref "JP567") (pin "1") (pinfunction "1_1") (pintype "passive"))
    )
    (net (code "328") (name "unconnected-(JP568-Pad1)") (class "Default")
      (node (ref "JP568") (pin "1") (pinfunction "1_1") (pintype "passive"))
    )
    (net (code "329") (name "unconnected-(JP569-Pad1)") (class "Default")
      (node (ref "JP569") (pin "1") (pinfunction "1_1") (pintype "passive"))
    )
    (net (code "330") (name "unconnected-(JP570-Pad1)") (class "Default")
      (node (ref "JP570") (pin "1") (pinfunction "1_1") (pintype "passive"))
    )
    (net (code "331") (name "unconnected-(JP571-Pad1)") (class "Default")
      (node (ref "JP571") (pin "1") (pinfunction "1_1") (pintype "passive"))
    )
    (net (code "332") (name "unconnected-(JP572-Pad1)") (class "Default")
      (node (ref "JP572") (pin "1") (pinfunction "1_1") (pintype "passive"))
    )
    (net (code "333") (name "unconnected-(JP573-Pad1)") (class "Default")
      (node (ref "JP573") (pin "1") (pinfunction "1_1") (pintype "passive"))
    )
    (net (code "334") (name "unconnected-(JP574-Pad1)") (class "Default")
      (node (ref "JP574") (pin "1") (pinfunction "1_1") (pintype "passive"))
    )
    (net (code "335") (name "unconnected-(JP575-Pad1)") (class "Default")
      (node (ref "JP575") (pin "1") (pinfunction "1_1") (pintype "passive"))
    )
    (net (code "336") (name "unconnected-(JP576-Pad1)") (class "Default")
      (node (ref "JP576") (pin "1") (pinfunction "1_1") (pintype "passive"))
    )
    (net (code "337") (name "unconnected-(JP577-Pad1)") (class "Default")
      (node (ref "JP577") (pin "1") (pinfunction "1_1") (pintype "passive"))
    )
    (net (code "338") (name "unconnected-(JP578-Pad1)") (class "Default")
      (node (ref "JP578") (pin "1") (pinfunction "1_1") (pintype "passive"))
    )
    (net (code "339") (name "unconnected-(JP579-Pad1)") (class "Default")
      (node (ref "JP579") (pin "1") (pinfunction "1_1") (pintype "passive"))
    )
    (net (code "340") (name "unconnected-(JP580-Pad1)") (class "Default")
      (node (ref "JP580") (pin "1") (pinfunction "1_1") (pintype "passive"))
    )
    (net (code "341") (name "unconnected-(JP581-Pad1)") (class "Default")
      (node (ref "JP581") (pin "1") (pinfunction "1_1") (pintype "passive"))
    )
    (net (code "342") (name "unconnected-(JP582-Pad1)") (class "Default")
      (node (ref "JP582") (pin "1") (pinfunction "1_1") (pintype "passive"))
    )
    (net (code "343") (name "unconnected-(JP583-Pad1)") (class "Default")
      (node (ref "JP583") (pin "1") (pinfunction "1_1") (pintype "passive"))
    )
    (net (code "344") (name "unconnected-(JP584-Pad1)") (class "Default")
      (node (ref "JP584") (pin "1") (pinfunction "1_1") (pintype "passive"))
    )
    (net (code "345") (name "unconnected-(JP585-Pad1)") (class "Default")
      (node (ref "JP585") (pin "1") (pinfunction "1_1") (pintype "passive"))
    )
    (net (code "346") (name "unconnected-(JP586-Pad1)") (class "Default")
      (node (ref "JP586") (pin "1") (pinfunction "1_1") (pintype "passive"))
    )
    (net (code "347") (name "unconnected-(JP587-Pad1)") (class "Default")
      (node (ref "JP587") (pin "1") (pinfunction "1_1") (pintype "passive"))
    )
    (net (code "348") (name "unconnected-(JP588-Pad1)") (class "Default")
      (node (ref "JP588") (pin "1") (pinfunction "1_1") (pintype "passive"))
    )
    (net (code "349") (name "unconnected-(JP589-Pad1)") (class "Default")
      (node (ref "JP589") (pin "1") (pinfunction "1_1") (pintype "passive"))
    )
    (net (code "350") (name "unconnected-(JP590-Pad1)") (class "Default")
      (node (ref "JP590") (pin "1") (pinfunction "1_1") (pintype "passive"))
    )
    (net (code "351") (name "unconnected-(JP591-Pad1)") (class "Default")
      (node (ref "JP591") (pin "1") (pinfunction "1_1") (pintype "passive"))
    )
    (net (code "352") (name "unconnected-(JP592-Pad1)") (class "Default")
      (node (ref "JP592") (pin "1") (pinfunction "1_1") (pintype "passive"))
    )
    (net (code "353") (name "unconnected-(JP593-Pad1)") (class "Default")
      (node (ref "JP593") (pin "1") (pinfunction "1_1") (pintype "passive"))
    )
    (net (code "354") (name "unconnected-(JP594-Pad1)") (class "Default")
      (node (ref "JP594") (pin "1") (pinfunction "1_1") (pintype "passive"))
    )
    (net (code "355") (name "unconnected-(JP595-Pad1)") (class "Default")
      (node (ref "JP595") (pin "1") (pinfunction "1_1") (pintype "passive"))
    )
    (net (code "356") (name "unconnected-(JP596-Pad1)") (class "Default")
      (node (ref "JP596") (pin "1") (pinfunction "1_1") (pintype "passive"))
    )
    (net (code "357") (name "unconnected-(JP597-Pad1)") (class "Default")
      (node (ref "JP597") (pin "1") (pinfunction "1_1") (pintype "passive"))
    )
    (net (code "358") (name "unconnected-(JP598-Pad1)") (class "Default")
      (node (ref "JP598") (pin "1") (pinfunction "1_1") (pintype "passive"))
    )
    (net (code "359") (name "unconnected-(JP599-Pad1)") (class "Default")
      (node (ref "JP599") (pin "1") (pinfunction "1_1") (pintype "passive"))
    )
    (net (code "360") (name "unconnected-(JP600-Pad1)") (class "Default")
      (node (ref "JP600") (pin "1") (pinfunction "1_1") (pintype "passive"))
    )
    (net (code "361") (name "unconnected-(JP601-Pad1)") (class "Default")
      (node (ref "JP601") (pin "1") (pinfunction "1_1") (pintype "passive"))
    )
    (net (code "362") (name "unconnected-(JP602-Pad1)") (class "Default")
      (node (ref "JP602") (pin "1") (pinfunction "1_1") (pintype "passive"))
    )
    (net (code "363") (name "unconnected-(JP603-Pad1)") (class "Default")
      (node (ref "JP603") (pin "1") (pinfunction "1_1") (pintype "passive"))
    )
    (net (code "364") (name "unconnected-(JP604-Pad1)") (class "Default")
      (node (ref "JP604") (pin "1") (pinfunction "1_1") (pintype "passive"))
    )
    (net (code "365") (name "unconnected-(JP605-Pad1)") (class "Default")
      (node (ref "JP605") (pin "1") (pinfunction "1_1") (pintype "passive"))
    )
    (net (code "366") (name "unconnected-(JP606-Pad1)") (class "Default")
      (node (ref "JP606") (pin "1") (pinfunction "1_1") (pintype "passive"))
    )
    (net (code "367") (name "unconnected-(JP607-Pad1)") (class "Default")
      (node (ref "JP607") (pin "1") (pinfunction "1_1") (pintype "passive"))
    )
    (net (code "368") (name "unconnected-(JP608-Pad1)") (class "Default")
      (node (ref "JP608") (pin "1") (pinfunction "1_1") (pintype "passive"))
    )
    (net (code "369") (name "unconnected-(JP609-Pad1)") (class "Default")
      (node (ref "JP609") (pin "1") (pinfunction "1_1") (pintype "passive"))
    )
    (net (code "370") (name "unconnected-(JP610-Pad1)") (class "Default")
      (node (ref "JP610") (pin "1") (pinfunction "1_1") (pintype "passive"))
    )
    (net (code "371") (name "unconnected-(JP611-Pad1)") (class "Default")
      (node (ref "JP611") (pin "1") (pinfunction "1_1") (pintype "passive"))
    )
    (net (code "372") (name "unconnected-(JP612-Pad1)") (class "Default")
      (node (ref "JP612") (pin "1") (pinfunction "1_1") (pintype "passive"))
    )
    (net (code "373") (name "unconnected-(JP613-Pad1)") (class "Default")
      (node (ref "JP613") (pin "1") (pinfunction "1_1") (pintype "passive"))
    )
    (net (code "374") (name "unconnected-(JP614-Pad1)") (class "Default")
      (node (ref "JP614") (pin "1") (pinfunction "1_1") (pintype "passive"))
    )
    (net (code "375") (name "unconnected-(JP615-Pad1)") (class "Default")
      (node (ref "JP615") (pin "1") (pinfunction "1_1") (pintype "passive"))
    )
    (net (code "376") (name "unconnected-(JP616-Pad1)") (class "Default")
      (node (ref "JP616") (pin "1") (pinfunction "1_1") (pintype "passive"))
    )
    (net (code "377") (name "unconnected-(JP617-Pad1)") (class "Default")
      (node (ref "JP617") (pin "1") (pinfunction "1_1") (pintype "passive"))
    )
    (net (code "378") (name "unconnected-(JP618-Pad1)") (class "Default")
      (node (ref "JP618") (pin "1") (pinfunction "1_1") (pintype "passive"))
    )
    (net (code "379") (name "unconnected-(JP619-Pad1)") (class "Default")
      (node (ref "JP619") (pin "1") (pinfunction "1_1") (pintype "passive"))
    )
    (net (code "380") (name "unconnected-(JP620-Pad1)") (class "Default")
      (node (ref "JP620") (pin "1") (pinfunction "1_1") (pintype "passive"))
    )
    (net (code "381") (name "unconnected-(JP621-Pad1)") (class "Default")
      (node (ref "JP621") (pin "1") (pinfunction "1_1") (pintype "passive"))
    )
    (net (code "382") (name "unconnected-(JP622-Pad1)") (class "Default")
      (node (ref "JP622") (pin "1") (pinfunction "1_1") (pintype "passive"))
    )
    (net (code "383") (name "unconnected-(JP623-Pad1)") (class "Default")
      (node (ref "JP623") (pin "1") (pinfunction "1_1") (pintype "passive"))
    )
    (net (code "384") (name "unconnected-(JP624-Pad1)") (class "Default")
      (node (ref "JP624") (pin "1") (pinfunction "1_1") (pintype "passive"))
    )
    (net (code "385") (name "unconnected-(JP625-Pad1)") (class "Default")
      (node (ref "JP625") (pin "1") (pinfunction "1_1") (pintype "passive"))
    )
    (net (code "386") (name "unconnected-(JP626-Pad1)") (class "Default")
      (node (ref "JP626") (pin "1") (pinfunction "1_1") (pintype "passive"))
    )
    (net (code "387") (name "unconnected-(JP627-Pad1)") (class "Default")
      (node (ref "JP627") (pin "1") (pinfunction "1_1") (pintype "passive"))
    )
    (net (code "388") (name "unconnected-(JP628-Pad1)") (class "Default")
      (node (ref "JP628") (pin "1") (pinfunction "1_1") (pintype "passive"))
    )
    (net (code "389") (name "unconnected-(JP629-Pad1)") (class "Default")
      (node (ref "JP629") (pin "1") (pinfunction "1_1") (pintype "passive"))
    )
    (net (code "390") (name "unconnected-(JP630-Pad1)") (class "Default")
      (node (ref "JP630") (pin "1") (pinfunction "1_1") (pintype "passive"))
    )
    (net (code "391") (name "unconnected-(JP631-Pad1)") (class "Default")
      (node (ref "JP631") (pin "1") (pinfunction "1_1") (pintype "passive"))
    )
    (net (code "392") (name "unconnected-(JP632-Pad1)") (class "Default")
      (node (ref "JP632") (pin "1") (pinfunction "1_1") (pintype "passive"))
    )
    (net (code "393") (name "unconnected-(JP633-Pad1)") (class "Default")
      (node (ref "JP633") (pin "1") (pinfunction "1_1") (pintype "passive"))
    )
    (net (code "394") (name "unconnected-(JP634-Pad1)") (class "Default")
      (node (ref "JP634") (pin "1") (pinfunction "1_1") (pintype "passive"))
    )
    (net (code "395") (name "unconnected-(JP635-Pad1)") (class "Default")
      (node (ref "JP635") (pin "1") (pinfunction "1_1") (pintype "passive"))
    )
    (net (code "396") (name "unconnected-(JP636-Pad1)") (class "Default")
      (node (ref "JP636") (pin "1") (pinfunction "1_1") (pintype "passive"))
    )
    (net (code "397") (name "unconnected-(JP637-Pad1)") (class "Default")
      (node (ref "JP637") (pin "1") (pinfunction "1_1") (pintype "passive"))
    )
    (net (code "398") (name "unconnected-(JP638-Pad1)") (class "Default")
      (node (ref "JP638") (pin "1") (pinfunction "1_1") (pintype "passive"))
    )
    (net (code "399") (name "unconnected-(JP639-Pad1)") (class "Default")
      (node (ref "JP639") (pin "1") (pinfunction "1_1") (pintype "passive"))
    )
    (net (code "400") (name "unconnected-(JP640-Pad1)") (class "Default")
      (node (ref "JP640") (pin "1") (pinfunction "1_1") (pintype "passive"))
    )
    (net (code "401") (name "unconnected-(JP641-Pad1)") (class "Default")
      (node (ref "JP641") (pin "1") (pinfunction "1_1") (pintype "passive"))
    )
    (net (code "402") (name "unconnected-(JP642-Pad1)") (class "Default")
      (node (ref "JP642") (pin "1") (pinfunction "1_1") (pintype "passive"))
    )
    (net (code "403") (name "unconnected-(JP643-Pad1)") (class "Default")
      (node (ref "JP643") (pin "1") (pinfunction "1_1") (pintype "passive"))
    )
    (net (code "404") (name "unconnected-(JP644-Pad1)") (class "Default")
      (node (ref "JP644") (pin "1") (pinfunction "1_1") (pintype "passive"))
    )
    (net (code "405") (name "unconnected-(JP645-Pad1)") (class "Default")
      (node (ref "JP645") (pin "1") (pinfunction "1_1") (pintype "passive"))
    )
    (net (code "406") (name "unconnected-(JP646-Pad1)") (class "Default")
      (node (ref "JP646") (pin "1") (pinfunction "1_1") (pintype "passive"))
    )
    (net (code "407") (name "unconnected-(JP647-Pad1)") (class "Default")
      (node (ref "JP647") (pin "1") (pinfunction "1_1") (pintype "passive"))
    )
    (net (code "408") (name "unconnected-(JP648-Pad1)") (class "Default")
      (node (ref "JP648") (pin "1") (pinfunction "1_1") (pintype "passive"))
    )
    (net (code "409") (name "unconnected-(JP649-Pad1)") (class "Default")
      (node (ref "JP649") (pin "1") (pinfunction "1_1") (pintype "passive"))
    )
    (net (code "410") (name "unconnected-(JP650-Pad1)") (class "Default")
      (node (ref "JP650") (pin "1") (pinfunction "1_1") (pintype "passive"))
    )
    (net (code "411") (name "unconnected-(JP651-Pad1)") (class "Default")
      (node (ref "JP651") (pin "1") (pinfunction "1_1") (pintype "passive"))
    )
    (net (code "412") (name "unconnected-(JP652-Pad1)") (class "Default")
      (node (ref "JP652") (pin "1") (pinfunction "1_1") (pintype "passive"))
    )
    (net (code "413") (name "unconnected-(JP653-Pad1)") (class "Default")
      (node (ref "JP653") (pin "1") (pinfunction "1_1") (pintype "passive"))
    )
    (net (code "414") (name "unconnected-(JP654-Pad1)") (class "Default")
      (node (ref "JP654") (pin "1") (pinfunction "1_1") (pintype "passive"))
    )
    (net (code "415") (name "unconnected-(JP655-Pad1)") (class "Default")
      (node (ref "JP655") (pin "1") (pinfunction "1_1") (pintype "passive"))
    )
    (net (code "416") (name "unconnected-(JP656-Pad1)") (class "Default")
      (node (ref "JP656") (pin "1") (pinfunction "1_1") (pintype "passive"))
    )
    (net (code "417") (name "unconnected-(JP657-Pad1)") (class "Default")
      (node (ref "JP657") (pin "1") (pinfunction "1_1") (pintype "passive"))
    )
    (net (code "418") (name "unconnected-(JP658-Pad1)") (class "Default")
      (node (ref "JP658") (pin "1") (pinfunction "1_1") (pintype "passive"))
    )
    (net (code "419") (name "unconnected-(JP659-Pad1)") (class "Default")
      (node (ref "JP659") (pin "1") (pinfunction "1_1") (pintype "passive"))
    )
    (net (code "420") (name "unconnected-(JP660-Pad1)") (class "Default")
      (node (ref "JP660") (pin "1") (pinfunction "1_1") (pintype "passive"))
    )
    (net (code "421") (name "unconnected-(JP661-Pad1)") (class "Default")
      (node (ref "JP661") (pin "1") (pinfunction "1_1") (pintype "passive"))
    )
    (net (code "422") (name "unconnected-(JP662-Pad1)") (class "Default")
      (node (ref "JP662") (pin "1") (pinfunction "1_1") (pintype "passive"))
    )
    (net (code "423") (name "unconnected-(JP663-Pad1)") (class "Default")
      (node (ref "JP663") (pin "1") (pinfunction "1_1") (pintype "passive"))
    )
    (net (code "424") (name "unconnected-(JP664-Pad1)") (class "Default")
      (node (ref "JP664") (pin "1") (pinfunction "1_1") (pintype "passive"))
    )
    (net (code "425") (name "unconnected-(JP665-Pad1)") (class "Default")
      (node (ref "JP665") (pin "1") (pinfunction "1_1") (pintype "passive"))
    )
    (net (code "426") (name "unconnected-(JP666-Pad1)") (class "Default")
      (node (ref "JP666") (pin "1") (pinfunction "1_1") (pintype "passive"))
    )
    (net (code "427") (name "unconnected-(JP667-Pad1)") (class "Default")
      (node (ref "JP667") (pin "1") (pinfunction "1_1") (pintype "passive"))
    )
    (net (code "428") (name "unconnected-(JP668-Pad1)") (class "Default")
      (node (ref "JP668") (pin "1") (pinfunction "1_1") (pintype "passive"))
    )
    (net (code "429") (name "unconnected-(JP669-Pad1)") (class "Default")
      (node (ref "JP669") (pin "1") (pinfunction "1_1") (pintype "passive"))
    )
    (net (code "430") (name "unconnected-(JP670-Pad1)") (class "Default")
      (node (ref "JP670") (pin "1") (pinfunction "1_1") (pintype "passive"))
    )
    (net (code "431") (name "unconnected-(JP671-Pad1)") (class "Default")
      (node (ref "JP671") (pin "1") (pinfunction "1_1") (pintype "passive"))
    )
    (net (code "432") (name "unconnected-(JP672-Pad1)") (class "Default")
      (node (ref "JP672") (pin "1") (pinfunction "1_1") (pintype "passive"))
    )
    (net (code "433") (name "unconnected-(JP673-Pad1)") (class "Default")
      (node (ref "JP673") (pin "1") (pinfunction "1_1") (pintype "passive"))
    )
    (net (code "434") (name "unconnected-(JP674-Pad1)") (class "Default")
      (node (ref "JP674") (pin "1") (pinfunction "1_1") (pintype "passive"))
    )
    (net (code "435") (name "unconnected-(JP675-Pad1)") (class "Default")
      (node (ref "JP675") (pin "1") (pinfunction "1_1") (pintype "passive"))
    )
    (net (code "436") (name "unconnected-(JP676-Pad1)") (class "Default")
      (node (ref "JP676") (pin "1") (pinfunction "1_1") (pintype "passive"))
    )
    (net (code "437") (name "unconnected-(JP677-Pad1)") (class "Default")
      (node (ref "JP677") (pin "1") (pinfunction "1_1") (pintype "passive"))
    )
    (net (code "438") (name "unconnected-(JP678-Pad1)") (class "Default")
      (node (ref "JP678") (pin "1") (pinfunction "1_1") (pintype "passive"))
    )
    (net (code "439") (name "unconnected-(JP679-Pad1)") (class "Default")
      (node (ref "JP679") (pin "1") (pinfunction "1_1") (pintype "passive"))
    )
    (net (code "440") (name "unconnected-(JP680-Pad1)") (class "Default")
      (node (ref "JP680") (pin "1") (pinfunction "1_1") (pintype "passive"))
    )
    (net (code "441") (name "unconnected-(JP681-Pad1)") (class "Default")
      (node (ref "JP681") (pin "1") (pinfunction "1_1") (pintype "passive"))
    )
    (net (code "442") (name "unconnected-(JP682-Pad1)") (class "Default")
      (node (ref "JP682") (pin "1") (pinfunction "1_1") (pintype "passive"))
    )
    (net (code "443") (name "unconnected-(JP683-Pad1)") (class "Default")
      (node (ref "JP683") (pin "1") (pinfunction "1_1") (pintype "passive"))
    )
    (net (code "444") (name "unconnected-(JP684-Pad1)") (class "Default")
      (node (ref "JP684") (pin "1") (pinfunction "1_1") (pintype "passive"))
    )
    (net (code "445") (name "unconnected-(JP685-Pad1)") (class "Default")
      (node (ref "JP685") (pin "1") (pinfunction "1_1") (pintype "passive"))
    )
    (net (code "446") (name "unconnected-(JP686-Pad1)") (class "Default")
      (node (ref "JP686") (pin "1") (pinfunction "1_1") (pintype "passive"))
    )
    (net (code "447") (name "unconnected-(JP687-Pad1)") (class "Default")
      (node (ref "JP687") (pin "1") (pinfunction "1_1") (pintype "passive"))
    )
    (net (code "448") (name "unconnected-(JP688-Pad1)") (class "Default")
      (node (ref "JP688") (pin "1") (pinfunction "1_1") (pintype "passive"))
    )
    (net (code "449") (name "unconnected-(JP689-Pad1)") (class "Default")
      (node (ref "JP689") (pin "1") (pinfunction "1_1") (pintype "passive"))
    )
    (net (code "450") (name "unconnected-(JP690-Pad1)") (class "Default")
      (node (ref "JP690") (pin "1") (pinfunction "1_1") (pintype "passive"))
    )
    (net (code "451") (name "unconnected-(JP691-Pad1)") (class "Default")
      (node (ref "JP691") (pin "1") (pinfunction "1_1") (pintype "passive"))
    )
    (net (code "452") (name "unconnected-(JP692-Pad1)") (class "Default")
      (node (ref "JP692") (pin "1") (pinfunction "1_1") (pintype "passive"))
    )
    (net (code "453") (name "unconnected-(JP693-Pad1)") (class "Default")
      (node (ref "JP693") (pin "1") (pinfunction "1_1") (pintype "passive"))
    )
    (net (code "454") (name "unconnected-(JP694-Pad1)") (class "Default")
      (node (ref "JP694") (pin "1") (pinfunction "1_1") (pintype "passive"))
    )
    (net (code "455") (name "unconnected-(JP695-Pad1)") (class "Default")
      (node (ref "JP695") (pin "1") (pinfunction "1_1") (pintype "passive"))
    )
    (net (code "456") (name "unconnected-(JP696-Pad1)") (class "Default")
      (node (ref "JP696") (pin "1") (pinfunction "1_1") (pintype "passive"))
    )
    (net (code "457") (name "unconnected-(JP697-Pad1)") (class "Default")
      (node (ref "JP697") (pin "1") (pinfunction "1_1") (pintype "passive"))
    )
    (net (code "458") (name "unconnected-(JP698-Pad1)") (class "Default")
      (node (ref "JP698") (pin "1") (pinfunction "1_1") (pintype "passive"))
    )
    (net (code "459") (name "unconnected-(JP699-Pad1)") (class "Default")
      (node (ref "JP699") (pin "1") (pinfunction "1_1") (pintype "passive"))
    )
    (net (code "460") (name "unconnected-(JP700-Pad1)") (class "Default")
      (node (ref "JP700") (pin "1") (pinfunction "1_1") (pintype "passive"))
    )
    (net (code "461") (name "unconnected-(JP701-Pad1)") (class "Default")
      (node (ref "JP701") (pin "1") (pinfunction "1_1") (pintype "passive"))
    )
    (net (code "462") (name "unconnected-(JP702-Pad1)") (class "Default")
      (node (ref "JP702") (pin "1") (pinfunction "1_1") (pintype "passive"))
    )
    (net (code "463") (name "unconnected-(JP703-Pad1)") (class "Default")
      (node (ref "JP703") (pin "1") (pinfunction "1_1") (pintype "passive"))
    )
    (net (code "464") (name "unconnected-(JP704-Pad1)") (class "Default")
      (node (ref "JP704") (pin "1") (pinfunction "1_1") (pintype "passive"))
    )
    (net (code "465") (name "unconnected-(JP705-Pad1)") (class "Default")
      (node (ref "JP705") (pin "1") (pinfunction "1_1") (pintype "passive"))
    )
    (net (code "466") (name "unconnected-(JP706-Pad1)") (class "Default")
      (node (ref "JP706") (pin "1") (pinfunction "1_1") (pintype "passive"))
    )
    (net (code "467") (name "unconnected-(JP707-Pad1)") (class "Default")
      (node (ref "JP707") (pin "1") (pinfunction "1_1") (pintype "passive"))
    )
    (net (code "468") (name "unconnected-(JP708-Pad1)") (class "Default")
      (node (ref "JP708") (pin "1") (pinfunction "1_1") (pintype "passive"))
    )
    (net (code "469") (name "unconnected-(JP709-Pad1)") (class "Default")
      (node (ref "JP709") (pin "1") (pinfunction "1_1") (pintype "passive"))
    )
    (net (code "470") (name "unconnected-(JP710-Pad1)") (class "Default")
      (node (ref "JP710") (pin "1") (pinfunction "1_1") (pintype "passive"))
    )
    (net (code "471") (name "unconnected-(JP711-Pad1)") (class "Default")
      (node (ref "JP711") (pin "1") (pinfunction "1_1") (pintype "passive"))
    )
    (net (code "472") (name "unconnected-(JP712-Pad1)") (class "Default")
      (node (ref "JP712") (pin "1") (pinfunction "1_1") (pintype "passive"))
    )
    (net (code "473") (name "unconnected-(JP713-Pad1)") (class "Default")
      (node (ref "JP713") (pin "1") (pinfunction "1_1") (pintype "passive"))
    )
    (net (code "474") (name "unconnected-(JP714-Pad1)") (class "Default")
      (node (ref "JP714") (pin "1") (pinfunction "1_1") (pintype "passive"))
    )
    (net (code "475") (name "unconnected-(JP715-Pad1)") (class "Default")
      (node (ref "JP715") (pin "1") (pinfunction "1_1") (pintype "passive"))
    )
    (net (code "476") (name "unconnected-(JP716-Pad1)") (class "Default")
      (node (ref "JP716") (pin "1") (pinfunction "1_1") (pintype "passive"))
    )
    (net (code "477") (name "unconnected-(JP717-Pad1)") (class "Default")
      (node (ref "JP717") (pin "1") (pinfunction "1_1") (pintype "passive"))
    )
    (net (code "478") (name "unconnected-(JP718-Pad1)") (class "Default")
      (node (ref "JP718") (pin "1") (pinfunction "1_1") (pintype "passive"))
    )
    (net (code "479") (name "unconnected-(JP719-Pad1)") (class "Default")
      (node (ref "JP719") (pin "1") (pinfunction "1_1") (pintype "passive"))
    )
    (net (code "480") (name "unconnected-(JP720-Pad1)") (class "Default")
      (node (ref "JP720") (pin "1") (pinfunction "1_1") (pintype "passive"))
    )
    (net (code "481") (name "unconnected-(JP721-Pad1)") (class "Default")
      (node (ref "JP721") (pin "1") (pinfunction "1_1") (pintype "passive"))
    )
    (net (code "482") (name "unconnected-(JP722-Pad1)") (class "Default")
      (node (ref "JP722") (pin "1") (pinfunction "1_1") (pintype "passive"))
    )
    (net (code "483") (name "unconnected-(JP741-Pad1)") (class "Default")
      (node (ref "JP741") (pin "1") (pinfunction "1_1") (pintype "passive"))
    )
    (net (code "484") (name "unconnected-(JP785-Pad1)") (class "Default")
      (node (ref "JP785") (pin "1") (pinfunction "1_1") (pintype "passive"))
    )
    (net (code "485") (name "unconnected-(JP786-Pad1)") (class "Default")
      (node (ref "JP786") (pin "1") (pinfunction "1_1") (pintype "passive"))
    )
    (net (code "486") (name "unconnected-(JP787-Pad1)") (class "Default")
      (node (ref "JP787") (pin "1") (pinfunction "1_1") (pintype "passive"))
    )
    (net (code "487") (name "unconnected-(JP791-Pad1)") (class "Default")
      (node (ref "JP791") (pin "1") (pinfunction "1_1") (pintype "passive"))
    )
    (net (code "488") (name "unconnected-(JP792-Pad1)") (class "Default")
      (node (ref "JP792") (pin "1") (pinfunction "1_1") (pintype "passive"))
    )
    (net (code "489") (name "unconnected-(JP793-Pad1)") (class "Default")
      (node (ref "JP793") (pin "1") (pinfunction "1_1") (pintype "passive"))
    )
    (net (code "490") (name "unconnected-(JP794-Pad1)") (class "Default")
      (node (ref "JP794") (pin "1") (pinfunction "1_1") (pintype "passive"))
    )
    (net (code "491") (name "unconnected-(MC1-Pad18)") (class "Default")
      (node (ref "MC1") (pin "18") (pinfunction "18_18") (pintype "passive"))
    )
    (net (code "492") (name "unconnected-(MC1-Pad21)") (class "Default")
      (node (ref "MC1") (pin "21") (pinfunction "21_21") (pintype "passive"))
    )
    (net (code "493") (name "unconnected-(MC1-Pad38)") (class "Default")
      (node (ref "MC1") (pin "38") (pinfunction "38_38") (pintype "passive"))
    )
    (net (code "494") (name "unconnected-(U$1A-1-PadP$1)") (class "Default")
      (node (ref "U$1") (pin "P$1") (pinfunction "1_P$1") (pintype "passive"))
    )
    (net (code "495") (name "unconnected-(U$1B-1-PadP$2)") (class "Default")
      (node (ref "U$1") (pin "P$2") (pinfunction "1_P$2") (pintype "passive"))
    )
    (net (code "496") (name "unconnected-(U$1C-1-PadP$3)") (class "Default")
      (node (ref "U$1") (pin "P$3") (pinfunction "1_P$3") (pintype "passive"))
    )
    (net (code "497") (name "unconnected-(U$1D-1-PadP$4)") (class "Default")
      (node (ref "U$1") (pin "P$4") (pinfunction "1_P$4") (pintype "passive"))
    )
    (net (code "498") (name "unconnected-(U$2A-1-PadP$1)") (class "Default")
      (node (ref "U$2") (pin "P$1") (pinfunction "1_P$1") (pintype "passive"))
    )
    (net (code "499") (name "unconnected-(U$2D-1-PadP$4)") (class "Default")
      (node (ref "U$2") (pin "P$4") (pinfunction "1_P$4") (pintype "passive"))
    )
  )
)
